# OSH_2018.net
KiCad netlist of a schematic drawn in EAGLE
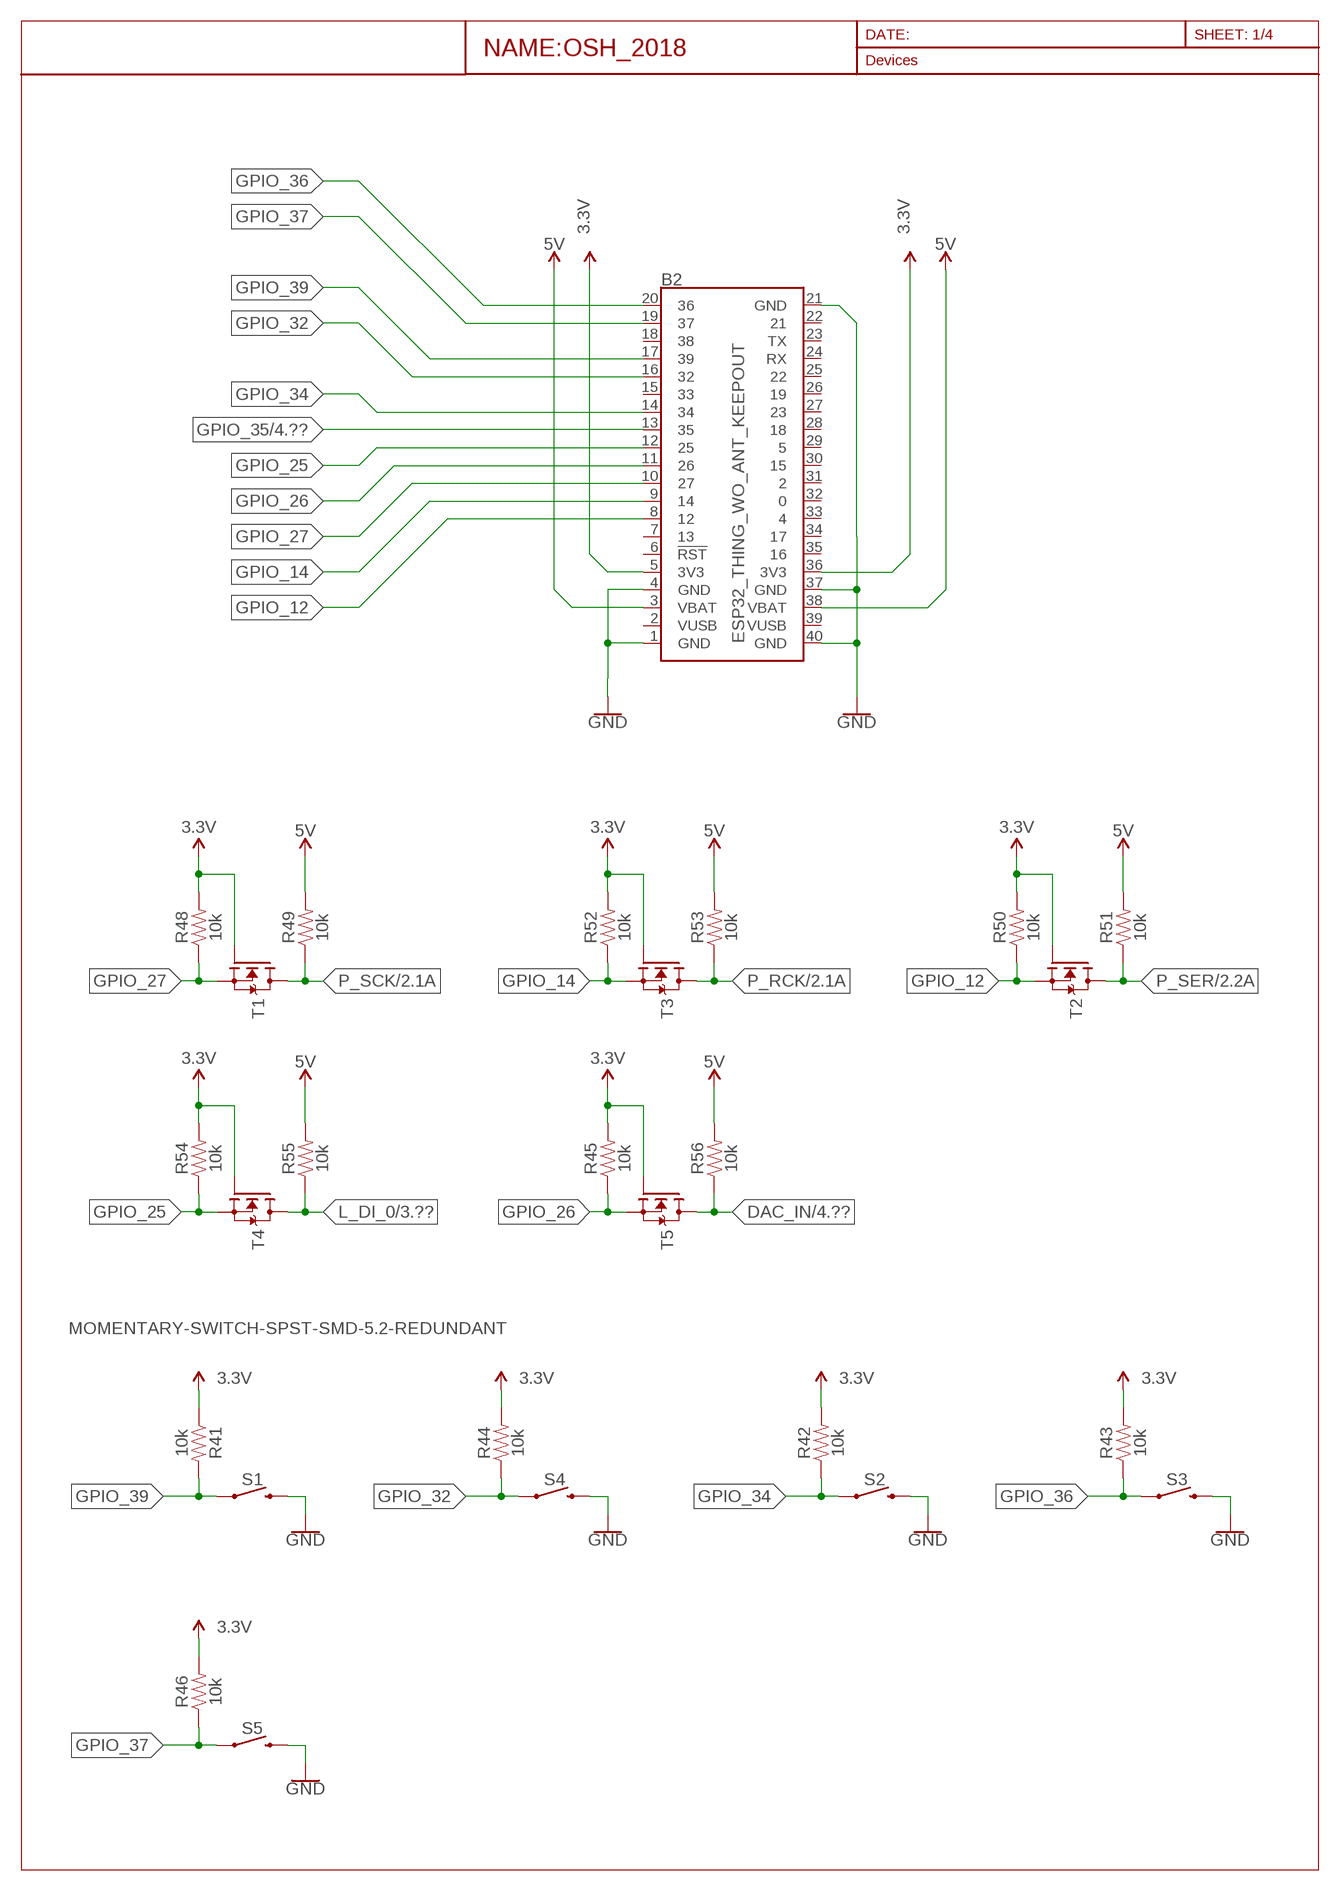
[diagram p0: schematic, sheet 1]
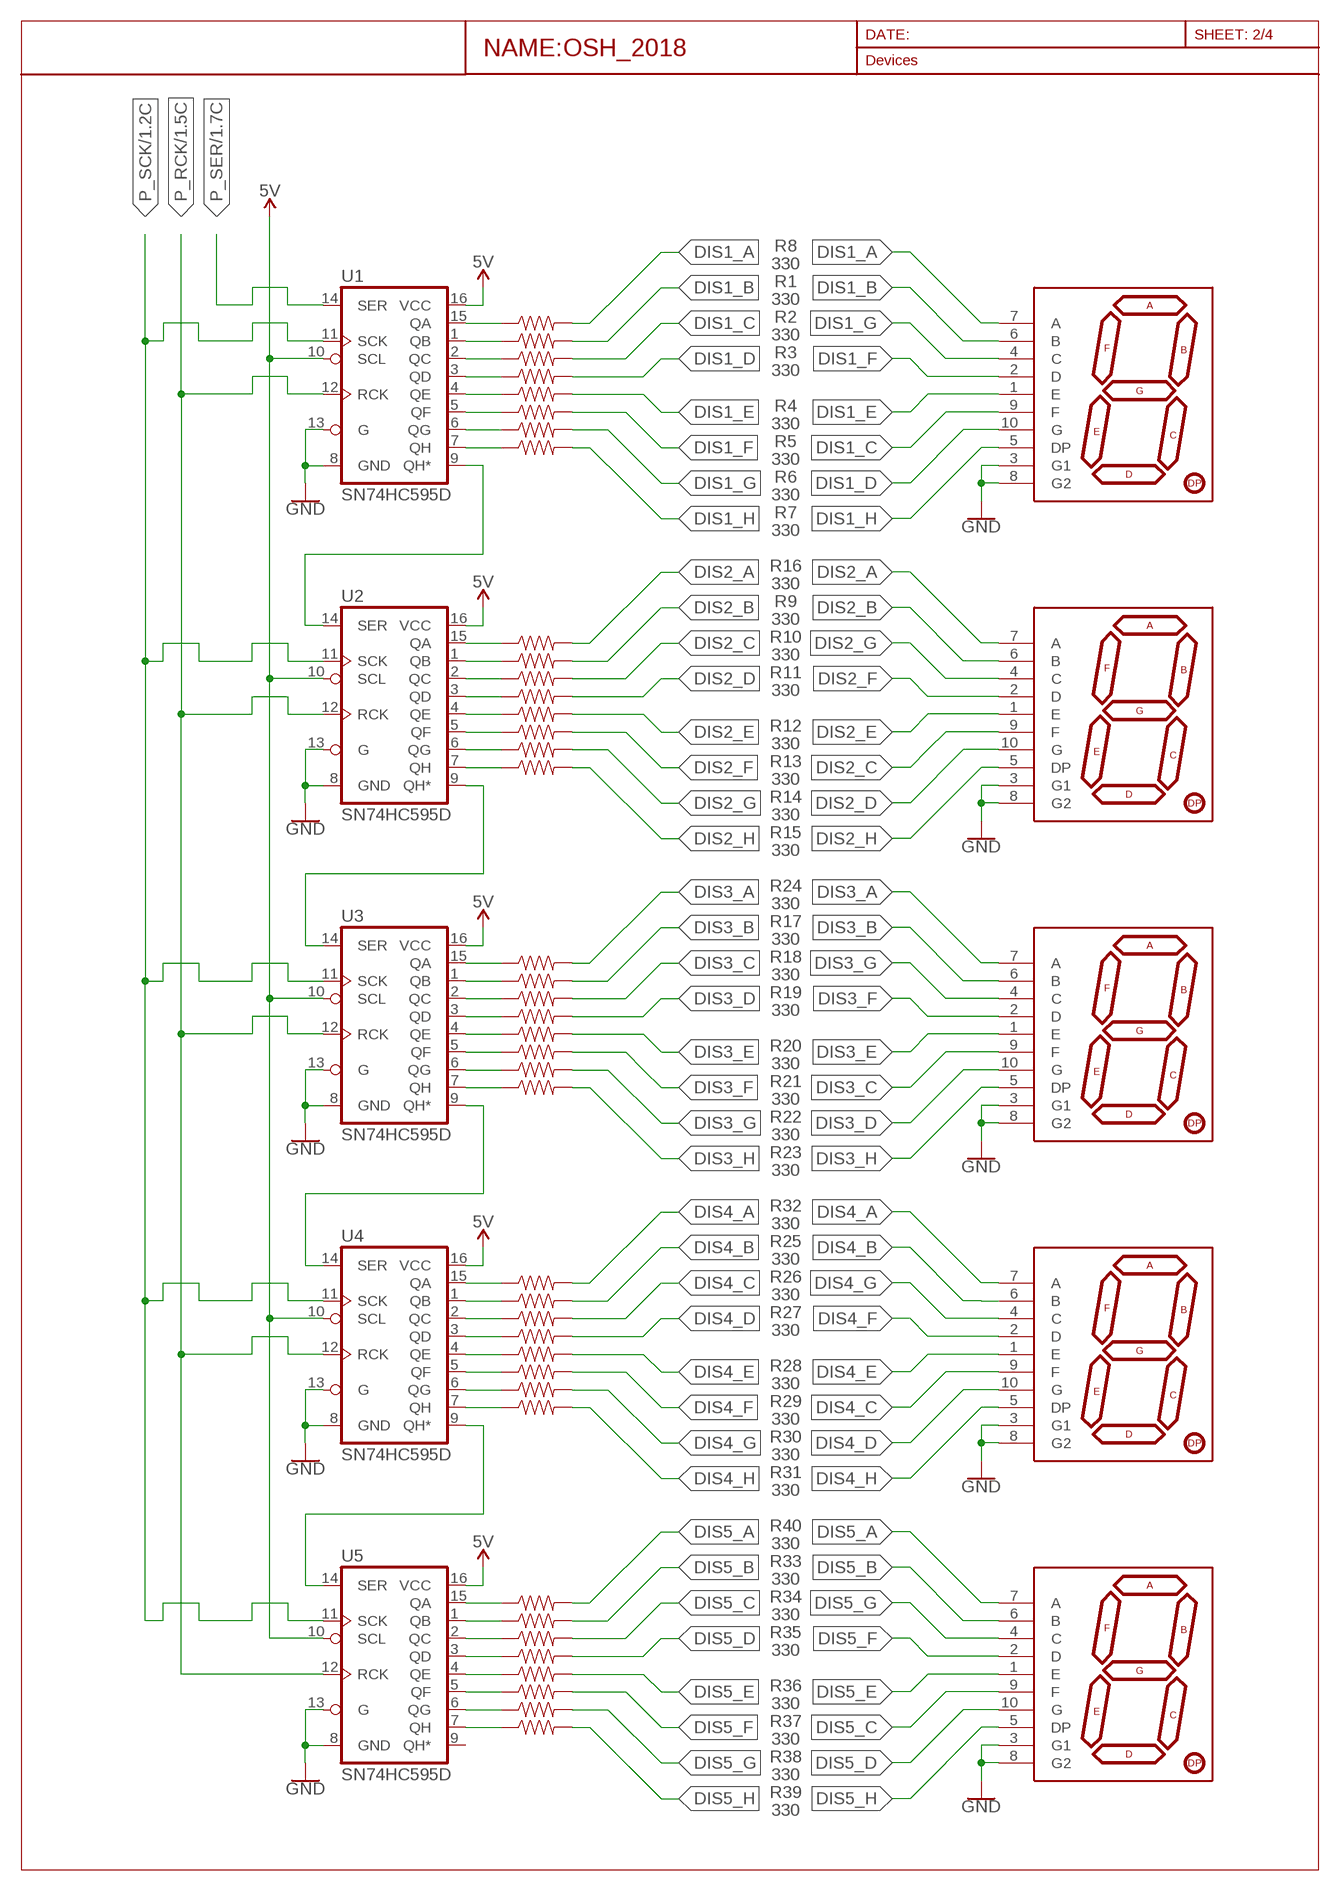
[diagram p1: schematic, sheet 2]
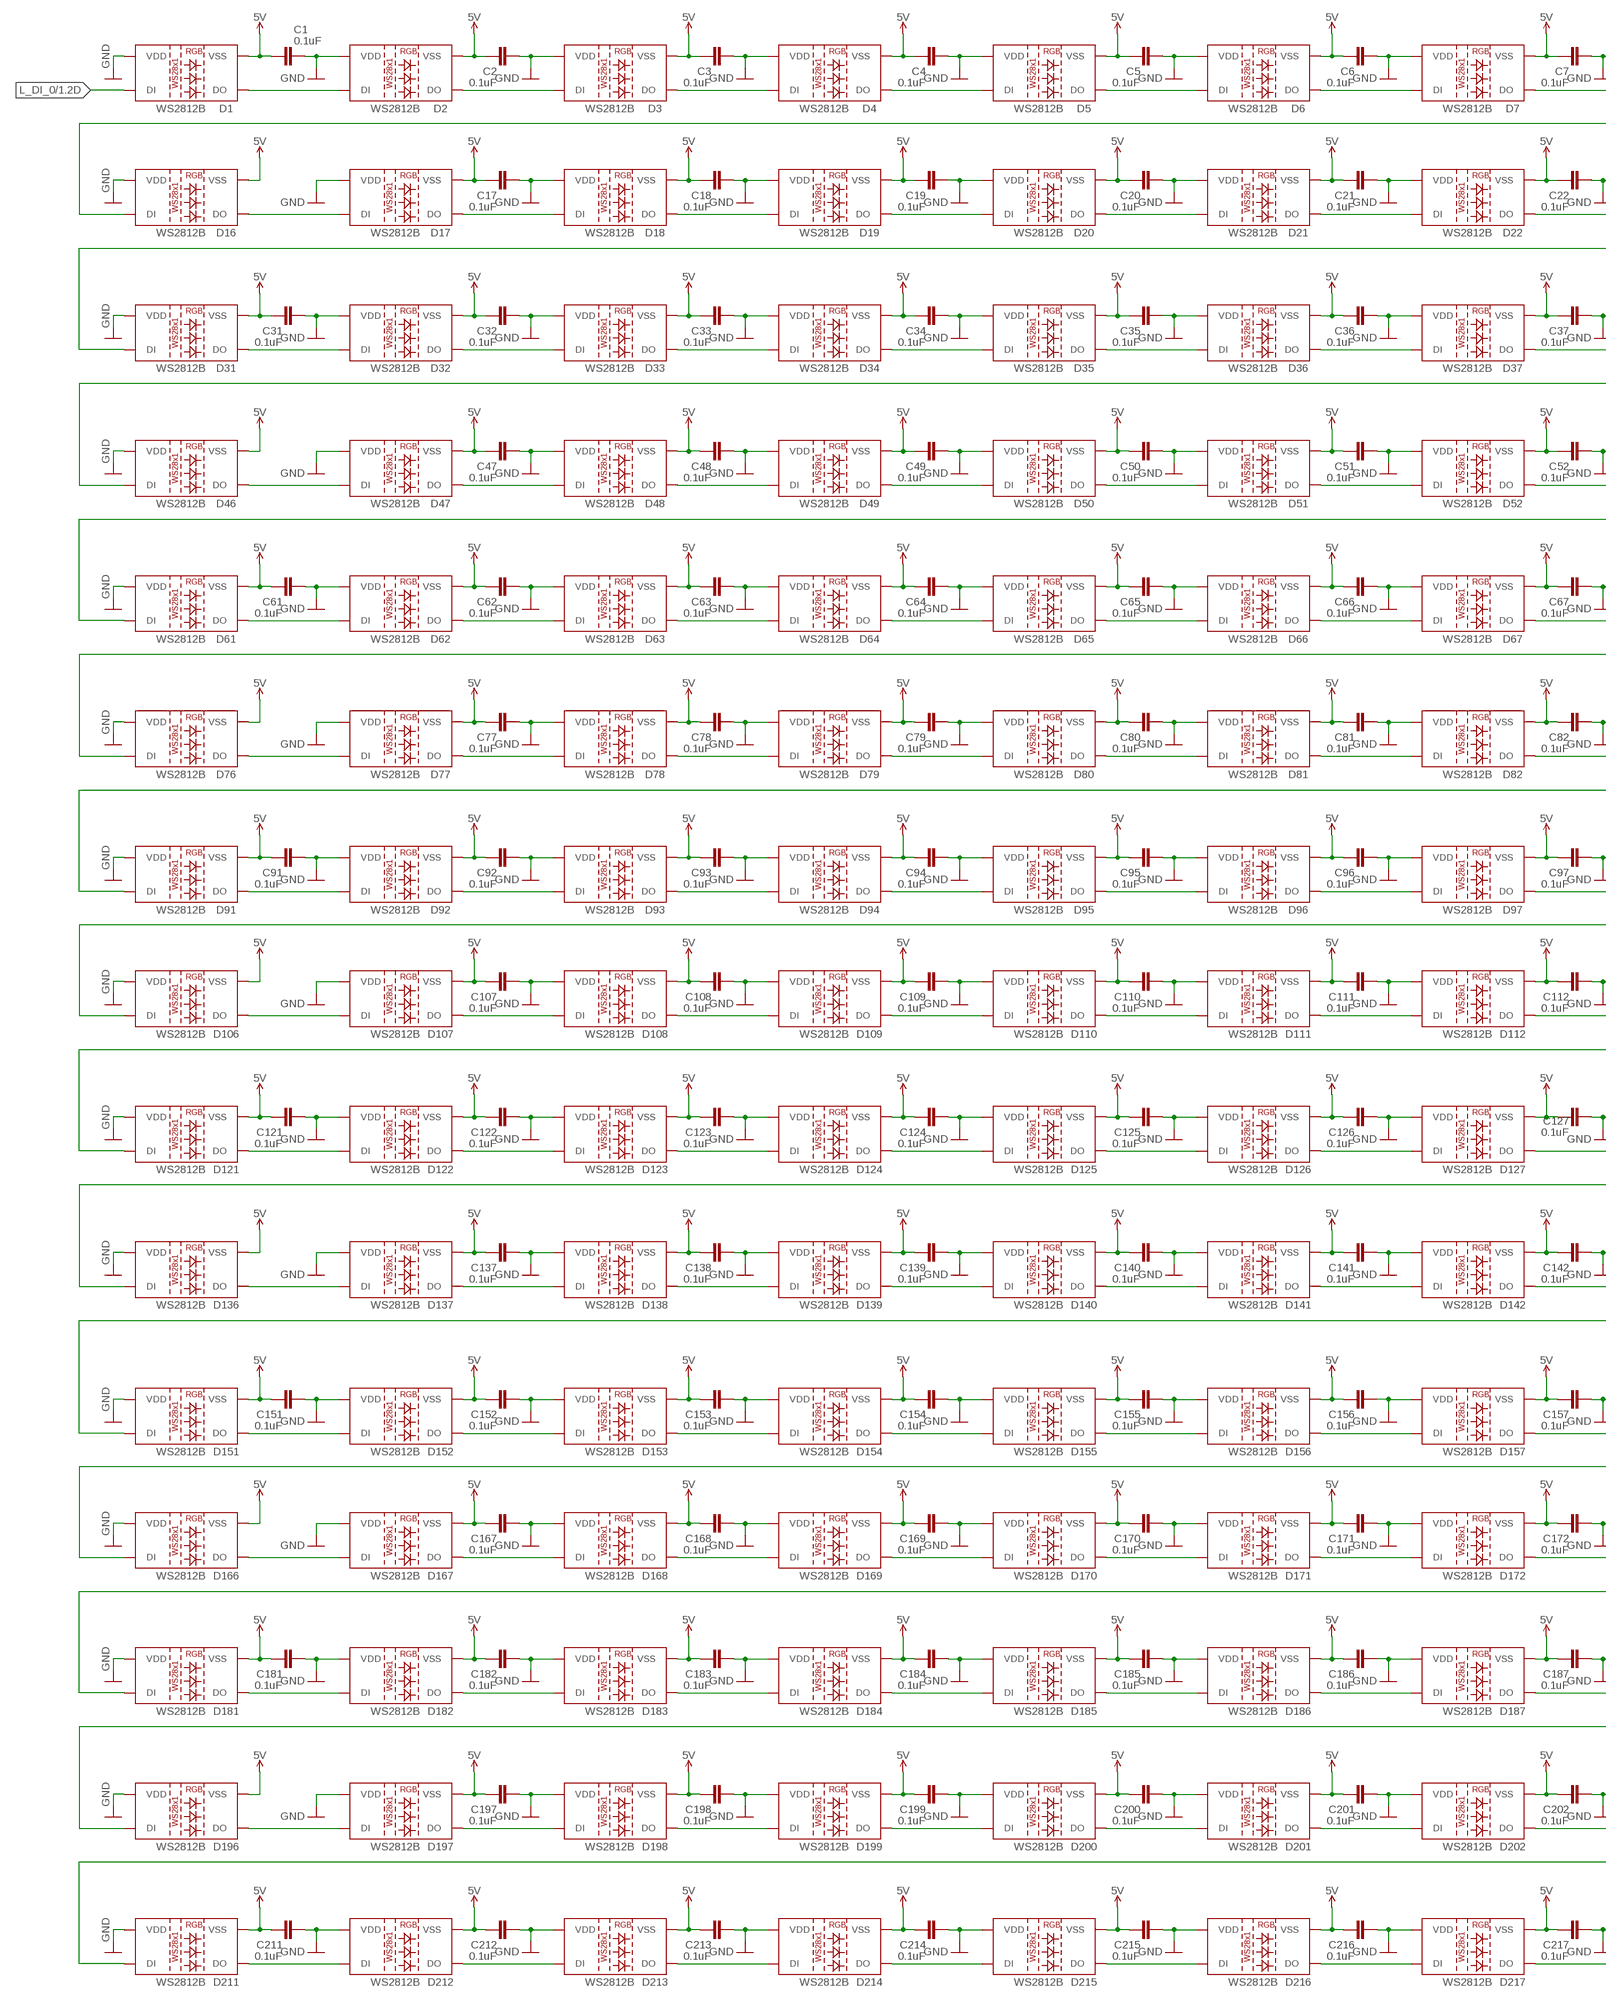
[diagram p2: schematic, sheet 3, part 1 of 2]
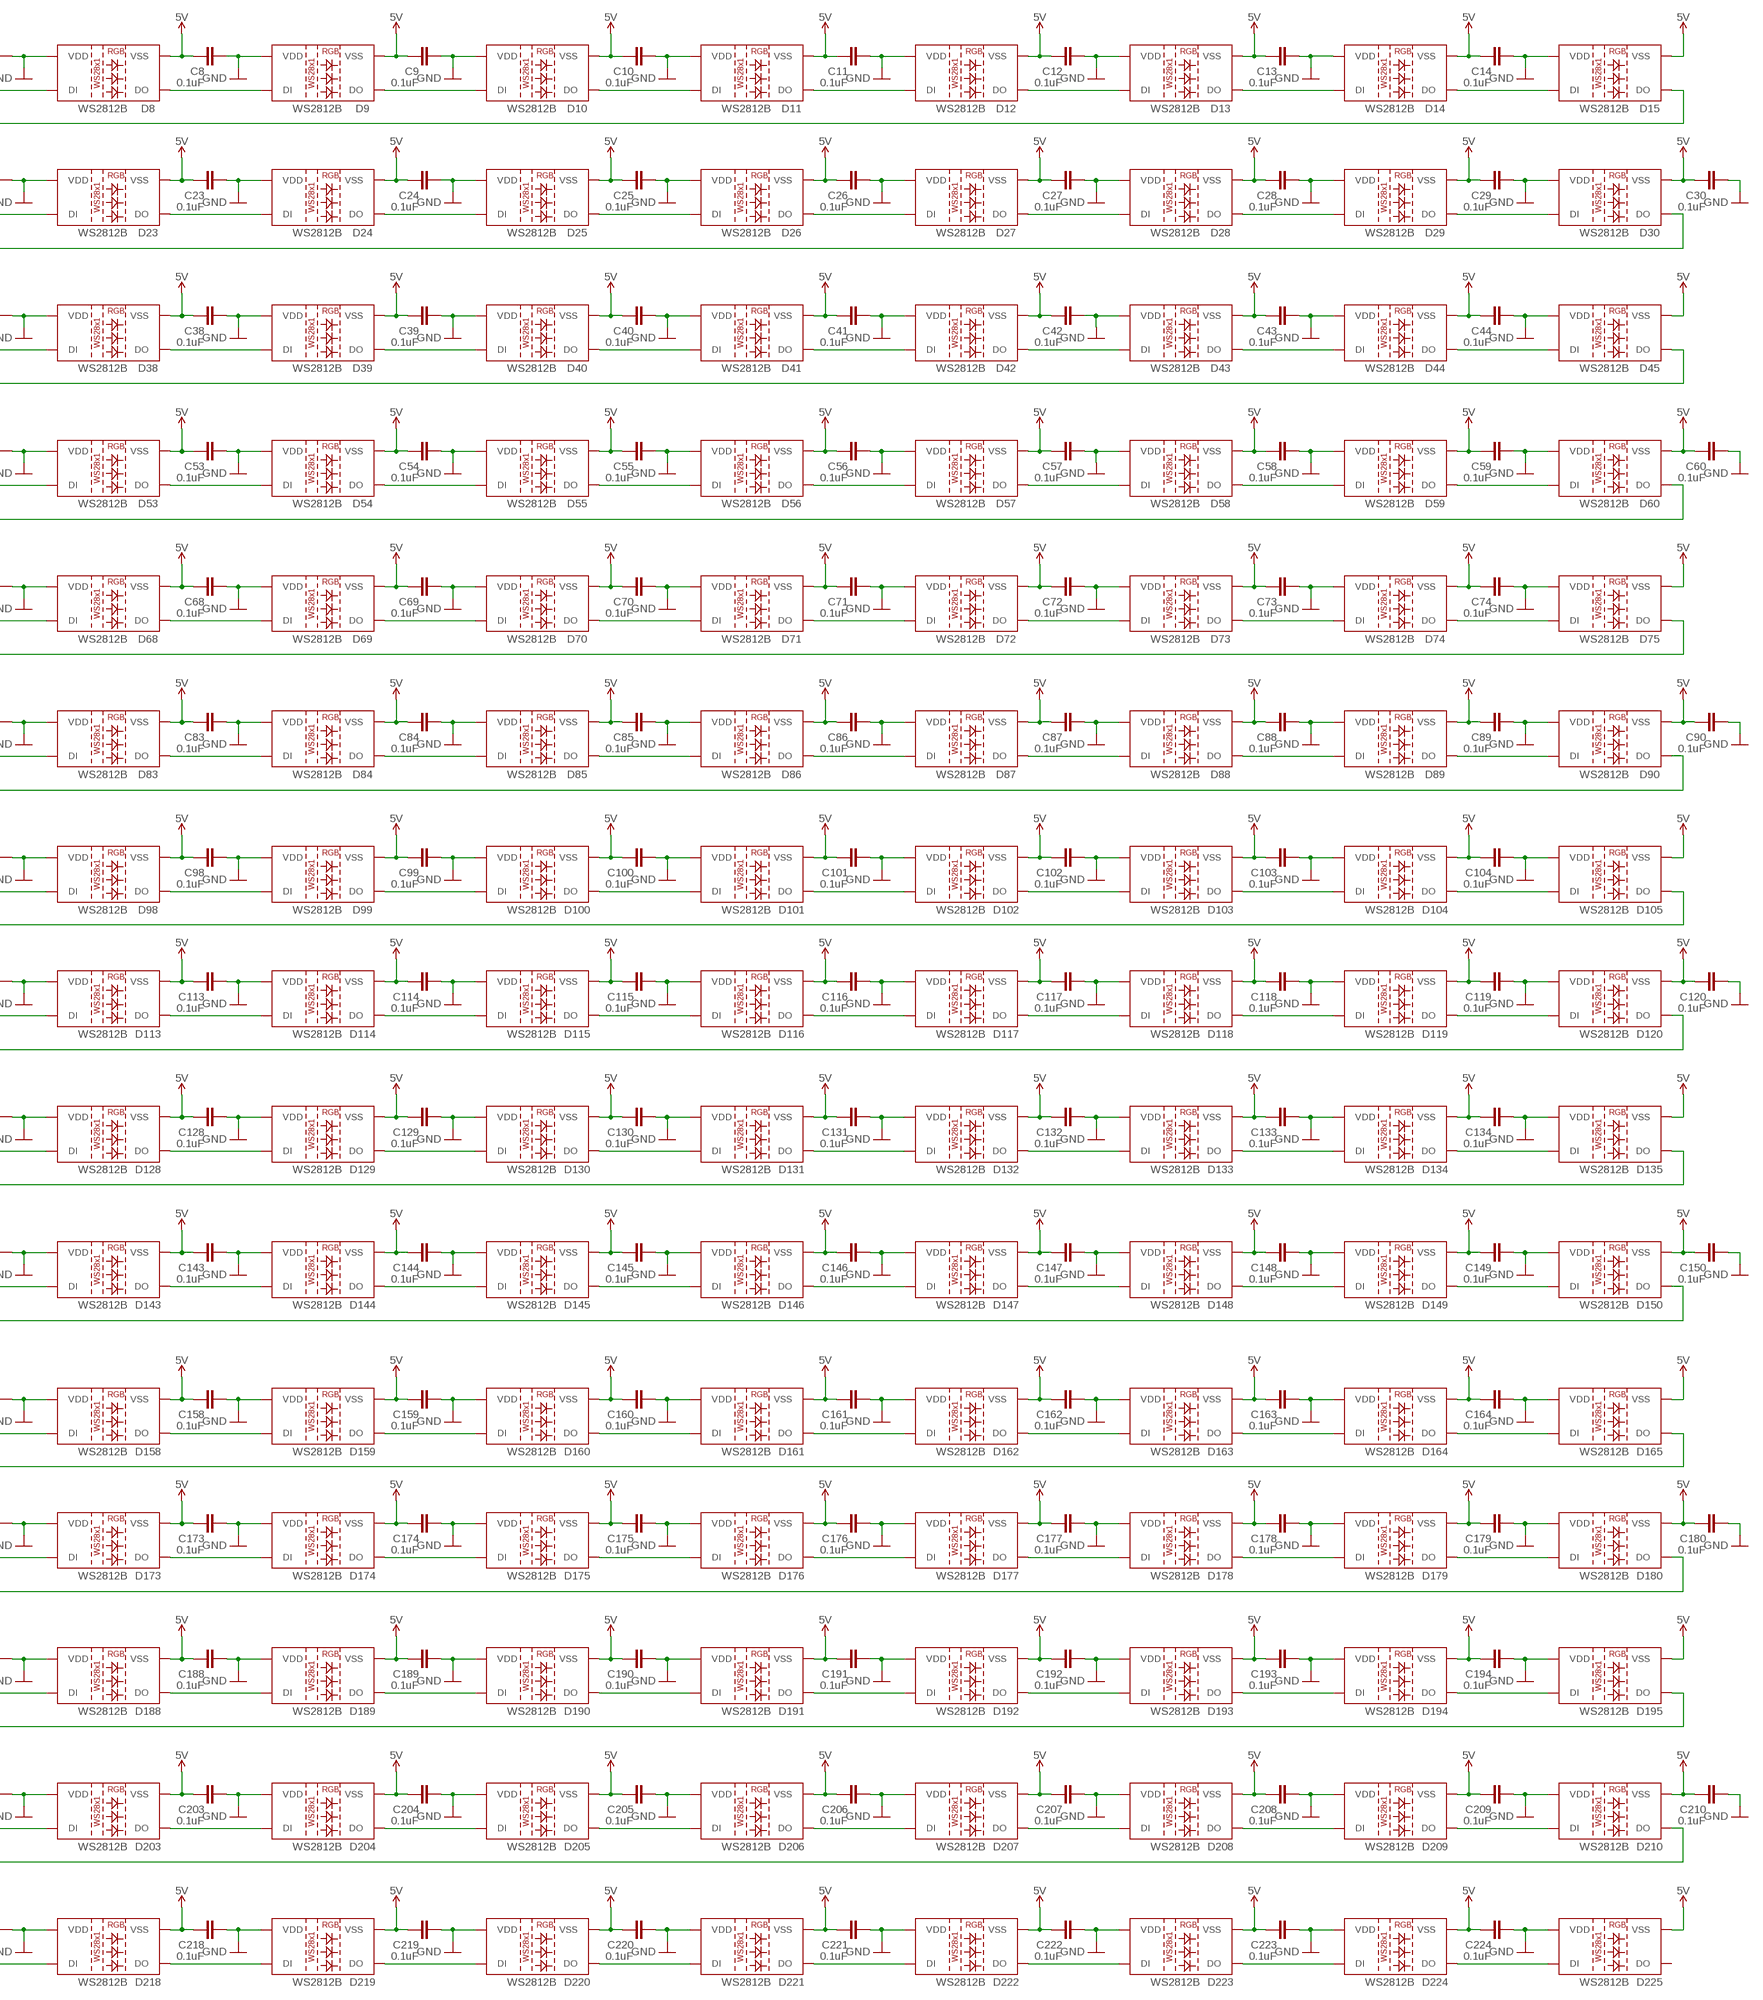
[diagram p3: schematic, sheet 3, part 2 of 2]
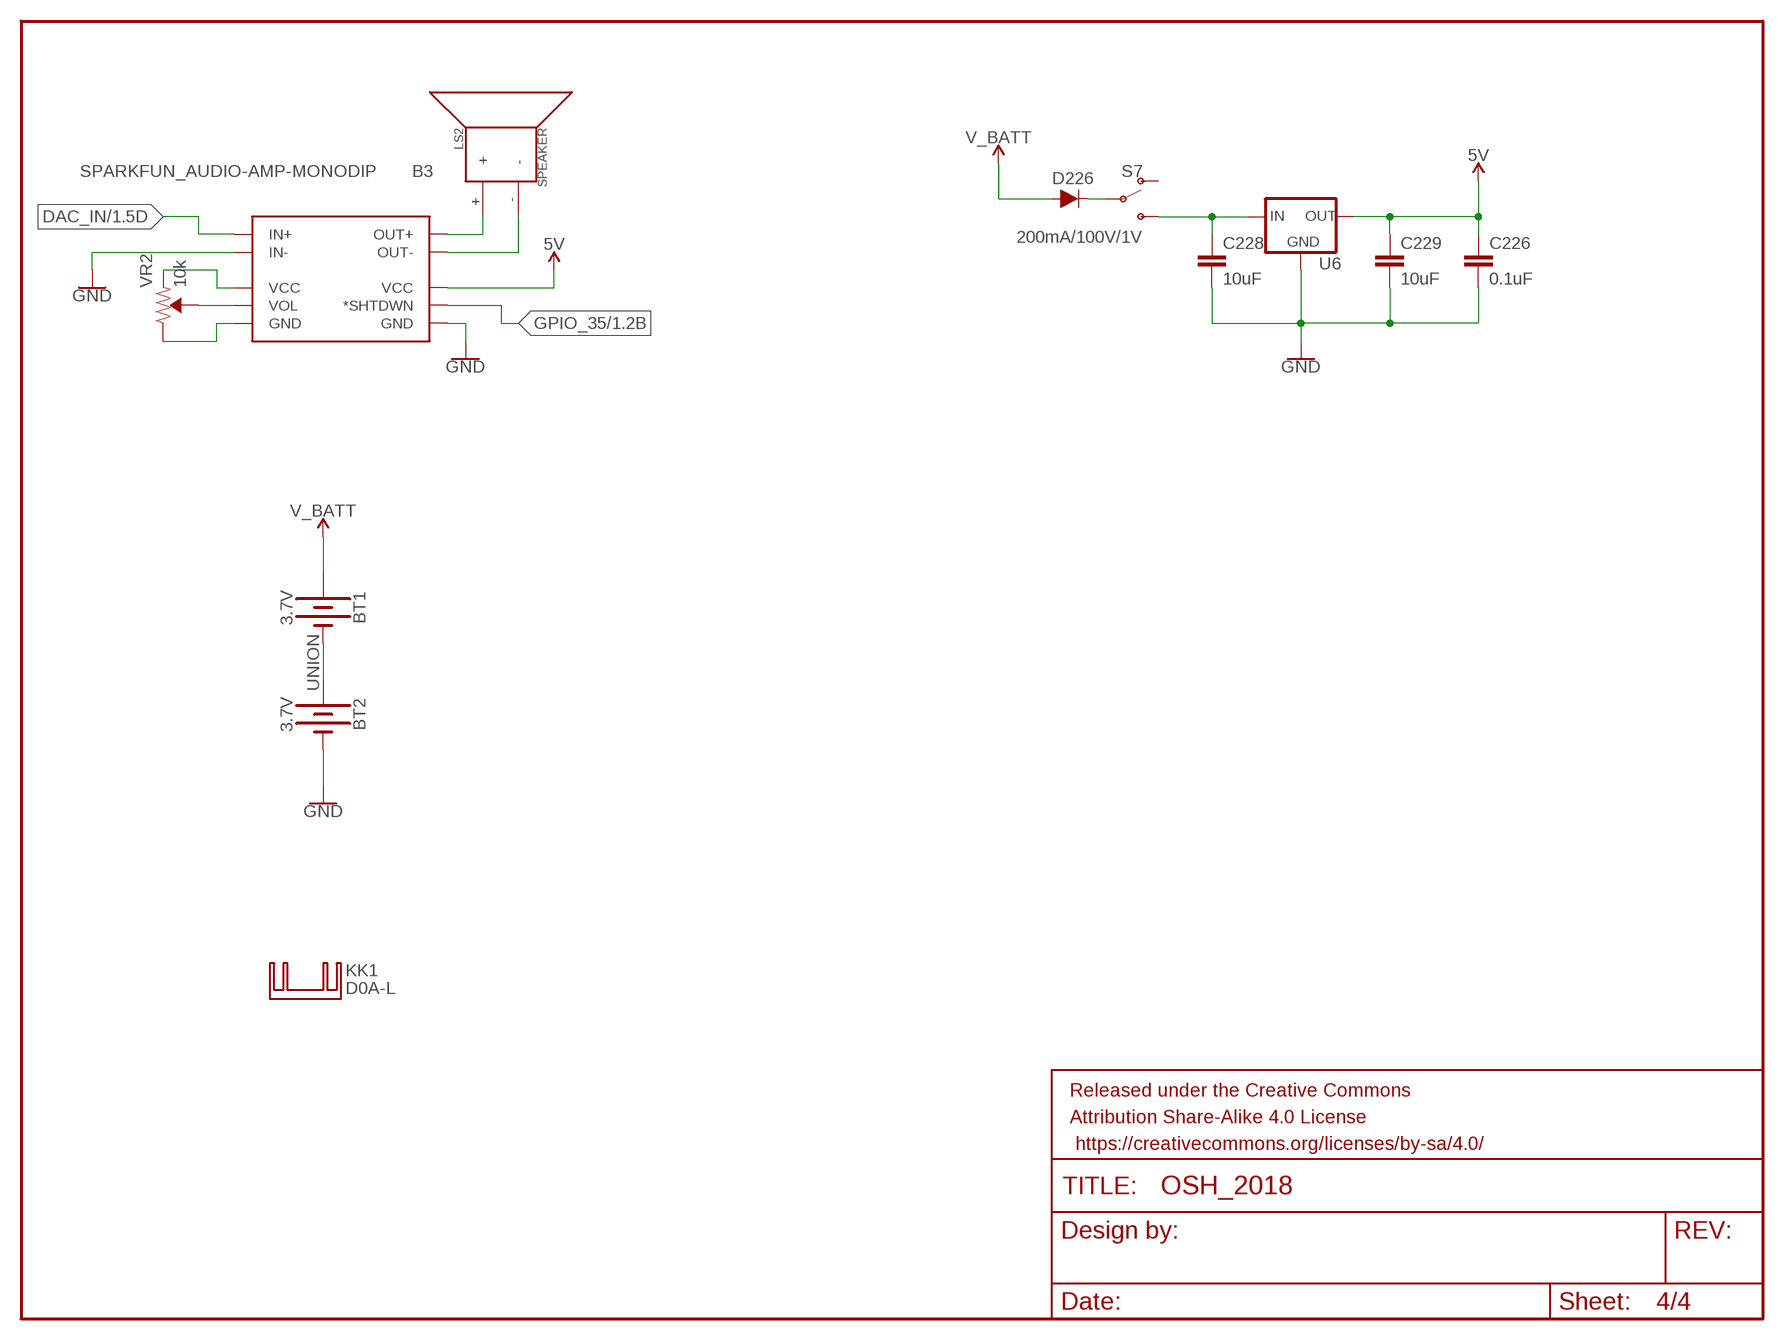
[diagram p4: schematic, sheet 4]

(export (version "E")
  (design (tool "Eeschema 10.0.6"))
  (components
    (comp (ref "B3")
      (value "SPARKFUN_AUDIO-AMP-MONODIP")
      (footprint "eagle-import:AUDIO-AMP-MONO")
      (libsource (lib "eagle-import") (part "SPARKFUN_AUDIO-AMP-MONODIP"))
    )
    (comp (ref "BT1")
      (value "3.7V")
      (footprint "eagle-import:BATTERY_18650-HOLDER")
      (libsource (lib "eagle-import") (part "BATTERY-18650"))
    )
    (comp (ref "BT2")
      (value "3.7V")
      (footprint "eagle-import:BATTERY_18650-HOLDER")
      (libsource (lib "eagle-import") (part "BATTERY-18650"))
    )
    (comp (ref "C226")
      (value "0.1uF")
      (footprint "eagle-import:0603")
      (libsource (lib "eagle-import") (part "SparkFun-Capacitors_510_0.1UF-0603-25V-(+80/-20%)"))
    )
    (comp (ref "C228")
      (value "10uF")
      (footprint "eagle-import:0603")
      (libsource (lib "eagle-import") (part "10UF-0603-6.3V-20%"))
    )
    (comp (ref "C229")
      (value "10uF")
      (footprint "eagle-import:0603")
      (libsource (lib "eagle-import") (part "10UF-0603-6.3V-20%"))
    )
    (comp (ref "D226")
      (value "200mA/100V/1V")
      (footprint "eagle-import:DIODE-1N4148")
      (libsource (lib "eagle-import") (part "DIODE-1N4148"))
    )
    (comp (ref "FRAME3")
      (value "FRAME-LETTERNO_PACKAGE")
      (footprint "eagle-import:DUMMY")
      (fields (field (name "DESIGNER") "Nobody"))
      (libsource (lib "eagle-import") (part "FRAME-LETTERNO_PACKAGE"))
    )
    (comp (ref "KK1")
      (value "D0A-L")
      (footprint "eagle-import:D02A-L")
      (libsource (lib "eagle-import") (part "D0A-L"))
    )
    (comp (ref "LS2")
      (value "SPEAKER")
      (footprint "eagle-import:PCB_MOUNT_SPEAKER")
      (libsource (lib "eagle-import") (part "SPEAKER"))
    )
    (comp (ref "S7")
      (value "SWITCH-SPDT-SMD-RIGHT-ANGLE")
      (footprint "eagle-import:SWITCH_SPST_SMD_A")
      (libsource (lib "eagle-import") (part "SWITCH-SPDT-SMD-RIGHT-ANGLE"))
    )
    (comp (ref "U6")
      (value "V_REG_78XX-TO-220")
      (footprint "eagle-import:TO-220-ALT")
      (libsource (lib "eagle-import") (part "V_REG_78XX-TO-220"))
    )
    (comp (ref "VR2")
      (value "10k")
      (footprint "eagle-import:TRIMPOT-PTH-3386U")
      (libsource (lib "eagle-import") (part "TRIMPOT-PTH-10MM-KNOB-1/2W-10%"))
    )
    (comp (ref "B2")
      (value "ESP32_THING_WO_ANT_KEEPOUT")
      (footprint "eagle-import:ESP32_THING_NO_ANT")
      (libsource (lib "eagle-import") (part "ESP32_THING_WO_ANT_KEEPOUT"))
    )
    (comp (ref "R41")
      (value "10k")
      (footprint "eagle-import:0603")
      (libsource (lib "eagle-import") (part "10KOHM-0603-1/10W-1%"))
    )
    (comp (ref "R42")
      (value "10k")
      (footprint "eagle-import:0603")
      (libsource (lib "eagle-import") (part "10KOHM-0603-1/10W-1%"))
    )
    (comp (ref "R43")
      (value "10k")
      (footprint "eagle-import:0603")
      (libsource (lib "eagle-import") (part "10KOHM-0603-1/10W-1%"))
    )
    (comp (ref "R44")
      (value "10k")
      (footprint "eagle-import:0603")
      (libsource (lib "eagle-import") (part "10KOHM-0603-1/10W-1%"))
    )
    (comp (ref "R45")
      (value "10k")
      (footprint "eagle-import:0603")
      (libsource (lib "eagle-import") (part "10KOHM-0603-1/10W-1%"))
    )
    (comp (ref "R46")
      (value "10k")
      (footprint "eagle-import:0603")
      (libsource (lib "eagle-import") (part "10KOHM-0603-1/10W-1%"))
    )
    (comp (ref "R48")
      (value "10k")
      (footprint "eagle-import:0603")
      (libsource (lib "eagle-import") (part "10KOHM-0603-1/10W-1%"))
    )
    (comp (ref "R49")
      (value "10k")
      (footprint "eagle-import:0603")
      (libsource (lib "eagle-import") (part "10KOHM-0603-1/10W-1%"))
    )
    (comp (ref "R50")
      (value "10k")
      (footprint "eagle-import:0603")
      (libsource (lib "eagle-import") (part "10KOHM-0603-1/10W-1%"))
    )
    (comp (ref "R51")
      (value "10k")
      (footprint "eagle-import:0603")
      (libsource (lib "eagle-import") (part "10KOHM-0603-1/10W-1%"))
    )
    (comp (ref "R52")
      (value "10k")
      (footprint "eagle-import:0603")
      (libsource (lib "eagle-import") (part "10KOHM-0603-1/10W-1%"))
    )
    (comp (ref "R53")
      (value "10k")
      (footprint "eagle-import:0603")
      (libsource (lib "eagle-import") (part "10KOHM-0603-1/10W-1%"))
    )
    (comp (ref "R54")
      (value "10k")
      (footprint "eagle-import:0603")
      (libsource (lib "eagle-import") (part "10KOHM-0603-1/10W-1%"))
    )
    (comp (ref "R55")
      (value "10k")
      (footprint "eagle-import:0603")
      (libsource (lib "eagle-import") (part "10KOHM-0603-1/10W-1%"))
    )
    (comp (ref "R56")
      (value "10k")
      (footprint "eagle-import:0603")
      (libsource (lib "eagle-import") (part "10KOHM-0603-1/10W-1%"))
    )
    (comp (ref "S1")
      (value "MOMENTARY-SWITCH-SPST-SMD-5.2-REDUNDANT")
      (footprint "eagle-import:TACTILE_SWITCH_SMD_5.2MM")
      (libsource (lib "eagle-import") (part "MOMENTARY-SWITCH-SPST-SMD-5.2-REDUNDANT"))
    )
    (comp (ref "S2")
      (value "MOMENTARY-SWITCH-SPST-SMD-5.2-REDUNDANT")
      (footprint "eagle-import:TACTILE_SWITCH_SMD_5.2MM")
      (libsource (lib "eagle-import") (part "MOMENTARY-SWITCH-SPST-SMD-5.2-REDUNDANT"))
    )
    (comp (ref "S3")
      (value "MOMENTARY-SWITCH-SPST-SMD-5.2-REDUNDANT")
      (footprint "eagle-import:TACTILE_SWITCH_SMD_5.2MM")
      (libsource (lib "eagle-import") (part "MOMENTARY-SWITCH-SPST-SMD-5.2-REDUNDANT"))
    )
    (comp (ref "S4")
      (value "MOMENTARY-SWITCH-SPST-SMD-5.2-REDUNDANT")
      (footprint "eagle-import:TACTILE_SWITCH_SMD_5.2MM")
      (libsource (lib "eagle-import") (part "MOMENTARY-SWITCH-SPST-SMD-5.2-REDUNDANT"))
    )
    (comp (ref "S5")
      (value "MOMENTARY-SWITCH-SPST-SMD-5.2-REDUNDANT")
      (footprint "eagle-import:TACTILE_SWITCH_SMD_5.2MM")
      (libsource (lib "eagle-import") (part "MOMENTARY-SWITCH-SPST-SMD-5.2-REDUNDANT"))
    )
    (comp (ref "T1")
      (value "MOSFET-N-SOT23")
      (footprint "eagle-import:SOT23")
      (libsource (lib "eagle-import") (part "MOSFET-N-SOT23"))
    )
    (comp (ref "T2")
      (value "MOSFET-N-SOT23")
      (footprint "eagle-import:SOT23")
      (libsource (lib "eagle-import") (part "MOSFET-N-SOT23"))
    )
    (comp (ref "T3")
      (value "MOSFET-N-SOT23")
      (footprint "eagle-import:SOT23")
      (libsource (lib "eagle-import") (part "MOSFET-N-SOT23"))
    )
    (comp (ref "T4")
      (value "MOSFET-N-SOT23")
      (footprint "eagle-import:SOT23")
      (libsource (lib "eagle-import") (part "MOSFET-N-SOT23"))
    )
    (comp (ref "T5")
      (value "MOSFET-N-SOT23")
      (footprint "eagle-import:SOT23")
      (libsource (lib "eagle-import") (part "MOSFET-N-SOT23"))
    )
    (comp (ref "DISPLAY_1")
      (value "YSD-160AB3C-8")
      (footprint "eagle-import:7-SEGMENT-1_PTH")
      (libsource (lib "eagle-import") (part "7-SEGMENT-1DIGIT-1INCH-BLUE"))
    )
    (comp (ref "DISPLAY_2")
      (value "YSD-160AB3C-8")
      (footprint "eagle-import:7-SEGMENT-1_PTH")
      (libsource (lib "eagle-import") (part "7-SEGMENT-1DIGIT-1INCH-BLUE"))
    )
    (comp (ref "DISPLAY_3")
      (value "YSD-160AB3C-8")
      (footprint "eagle-import:7-SEGMENT-1_PTH")
      (libsource (lib "eagle-import") (part "7-SEGMENT-1DIGIT-1INCH-BLUE"))
    )
    (comp (ref "DISPLAY_4")
      (value "YSD-160AB3C-8")
      (footprint "eagle-import:7-SEGMENT-1_PTH")
      (libsource (lib "eagle-import") (part "7-SEGMENT-1DIGIT-1INCH-BLUE"))
    )
    (comp (ref "DISPLAY_5")
      (value "YSD-160AB3C-8")
      (footprint "eagle-import:7-SEGMENT-1_PTH")
      (libsource (lib "eagle-import") (part "7-SEGMENT-1DIGIT-1INCH-BLUE"))
    )
    (comp (ref "R1")
      (value "330")
      (footprint "eagle-import:0603")
      (libsource (lib "eagle-import") (part "330OHM-0603-1/10W-1%"))
    )
    (comp (ref "R2")
      (value "330")
      (footprint "eagle-import:0603")
      (libsource (lib "eagle-import") (part "330OHM-0603-1/10W-1%"))
    )
    (comp (ref "R3")
      (value "330")
      (footprint "eagle-import:0603")
      (libsource (lib "eagle-import") (part "330OHM-0603-1/10W-1%"))
    )
    (comp (ref "R4")
      (value "330")
      (footprint "eagle-import:0603")
      (libsource (lib "eagle-import") (part "330OHM-0603-1/10W-1%"))
    )
    (comp (ref "R5")
      (value "330")
      (footprint "eagle-import:0603")
      (libsource (lib "eagle-import") (part "330OHM-0603-1/10W-1%"))
    )
    (comp (ref "R6")
      (value "330")
      (footprint "eagle-import:0603")
      (libsource (lib "eagle-import") (part "330OHM-0603-1/10W-1%"))
    )
    (comp (ref "R7")
      (value "330")
      (footprint "eagle-import:0603")
      (libsource (lib "eagle-import") (part "330OHM-0603-1/10W-1%"))
    )
    (comp (ref "R8")
      (value "330")
      (footprint "eagle-import:0603")
      (libsource (lib "eagle-import") (part "330OHM-0603-1/10W-1%"))
    )
    (comp (ref "R9")
      (value "330")
      (footprint "eagle-import:0603")
      (libsource (lib "eagle-import") (part "330OHM-0603-1/10W-1%"))
    )
    (comp (ref "R10")
      (value "330")
      (footprint "eagle-import:0603")
      (libsource (lib "eagle-import") (part "330OHM-0603-1/10W-1%"))
    )
    (comp (ref "R11")
      (value "330")
      (footprint "eagle-import:0603")
      (libsource (lib "eagle-import") (part "330OHM-0603-1/10W-1%"))
    )
    (comp (ref "R12")
      (value "330")
      (footprint "eagle-import:0603")
      (libsource (lib "eagle-import") (part "330OHM-0603-1/10W-1%"))
    )
    (comp (ref "R13")
      (value "330")
      (footprint "eagle-import:0603")
      (libsource (lib "eagle-import") (part "330OHM-0603-1/10W-1%"))
    )
    (comp (ref "R14")
      (value "330")
      (footprint "eagle-import:0603")
      (libsource (lib "eagle-import") (part "330OHM-0603-1/10W-1%"))
    )
    (comp (ref "R15")
      (value "330")
      (footprint "eagle-import:0603")
      (libsource (lib "eagle-import") (part "330OHM-0603-1/10W-1%"))
    )
    (comp (ref "R16")
      (value "330")
      (footprint "eagle-import:0603")
      (libsource (lib "eagle-import") (part "330OHM-0603-1/10W-1%"))
    )
    (comp (ref "R17")
      (value "330")
      (footprint "eagle-import:0603")
      (libsource (lib "eagle-import") (part "330OHM-0603-1/10W-1%"))
    )
    (comp (ref "R18")
      (value "330")
      (footprint "eagle-import:0603")
      (libsource (lib "eagle-import") (part "330OHM-0603-1/10W-1%"))
    )
    (comp (ref "R19")
      (value "330")
      (footprint "eagle-import:0603")
      (libsource (lib "eagle-import") (part "330OHM-0603-1/10W-1%"))
    )
    (comp (ref "R20")
      (value "330")
      (footprint "eagle-import:0603")
      (libsource (lib "eagle-import") (part "330OHM-0603-1/10W-1%"))
    )
    (comp (ref "R21")
      (value "330")
      (footprint "eagle-import:0603")
      (libsource (lib "eagle-import") (part "330OHM-0603-1/10W-1%"))
    )
    (comp (ref "R22")
      (value "330")
      (footprint "eagle-import:0603")
      (libsource (lib "eagle-import") (part "330OHM-0603-1/10W-1%"))
    )
    (comp (ref "R23")
      (value "330")
      (footprint "eagle-import:0603")
      (libsource (lib "eagle-import") (part "330OHM-0603-1/10W-1%"))
    )
    (comp (ref "R24")
      (value "330")
      (footprint "eagle-import:0603")
      (libsource (lib "eagle-import") (part "330OHM-0603-1/10W-1%"))
    )
    (comp (ref "R25")
      (value "330")
      (footprint "eagle-import:0603")
      (libsource (lib "eagle-import") (part "330OHM-0603-1/10W-1%"))
    )
    (comp (ref "R26")
      (value "330")
      (footprint "eagle-import:0603")
      (libsource (lib "eagle-import") (part "330OHM-0603-1/10W-1%"))
    )
    (comp (ref "R27")
      (value "330")
      (footprint "eagle-import:0603")
      (libsource (lib "eagle-import") (part "330OHM-0603-1/10W-1%"))
    )
    (comp (ref "R28")
      (value "330")
      (footprint "eagle-import:0603")
      (libsource (lib "eagle-import") (part "330OHM-0603-1/10W-1%"))
    )
    (comp (ref "R29")
      (value "330")
      (footprint "eagle-import:0603")
      (libsource (lib "eagle-import") (part "330OHM-0603-1/10W-1%"))
    )
    (comp (ref "R30")
      (value "330")
      (footprint "eagle-import:0603")
      (libsource (lib "eagle-import") (part "330OHM-0603-1/10W-1%"))
    )
    (comp (ref "R31")
      (value "330")
      (footprint "eagle-import:0603")
      (libsource (lib "eagle-import") (part "330OHM-0603-1/10W-1%"))
    )
    (comp (ref "R32")
      (value "330")
      (footprint "eagle-import:0603")
      (libsource (lib "eagle-import") (part "330OHM-0603-1/10W-1%"))
    )
    (comp (ref "R33")
      (value "330")
      (footprint "eagle-import:0603")
      (libsource (lib "eagle-import") (part "330OHM-0603-1/10W-1%"))
    )
    (comp (ref "R34")
      (value "330")
      (footprint "eagle-import:0603")
      (libsource (lib "eagle-import") (part "330OHM-0603-1/10W-1%"))
    )
    (comp (ref "R35")
      (value "330")
      (footprint "eagle-import:0603")
      (libsource (lib "eagle-import") (part "330OHM-0603-1/10W-1%"))
    )
    (comp (ref "R36")
      (value "330")
      (footprint "eagle-import:0603")
      (libsource (lib "eagle-import") (part "330OHM-0603-1/10W-1%"))
    )
    (comp (ref "R37")
      (value "330")
      (footprint "eagle-import:0603")
      (libsource (lib "eagle-import") (part "330OHM-0603-1/10W-1%"))
    )
    (comp (ref "R38")
      (value "330")
      (footprint "eagle-import:0603")
      (libsource (lib "eagle-import") (part "330OHM-0603-1/10W-1%"))
    )
    (comp (ref "R39")
      (value "330")
      (footprint "eagle-import:0603")
      (libsource (lib "eagle-import") (part "330OHM-0603-1/10W-1%"))
    )
    (comp (ref "R40")
      (value "330")
      (footprint "eagle-import:0603")
      (libsource (lib "eagle-import") (part "330OHM-0603-1/10W-1%"))
    )
    (comp (ref "U1")
      (value "SN74HC595D")
      (footprint "eagle-import:SO16")
      (libsource (lib "eagle-import") (part "74595DHC"))
    )
    (comp (ref "U2")
      (value "SN74HC595D")
      (footprint "eagle-import:SO16")
      (libsource (lib "eagle-import") (part "74595DHC"))
    )
    (comp (ref "U3")
      (value "SN74HC595D")
      (footprint "eagle-import:SO16")
      (libsource (lib "eagle-import") (part "74595DHC"))
    )
    (comp (ref "U4")
      (value "SN74HC595D")
      (footprint "eagle-import:SO16")
      (libsource (lib "eagle-import") (part "74595DHC"))
    )
    (comp (ref "U5")
      (value "SN74HC595D")
      (footprint "eagle-import:SO16")
      (libsource (lib "eagle-import") (part "74595DHC"))
    )
    (comp (ref "C1")
      (value "0.1uF")
      (footprint "eagle-import:0603")
      (libsource (lib "eagle-import") (part "0.1UF-0603-25V-5%"))
    )
    (comp (ref "C2")
      (value "0.1uF")
      (footprint "eagle-import:0603")
      (libsource (lib "eagle-import") (part "0.1UF-0603-25V-5%"))
    )
    (comp (ref "C3")
      (value "0.1uF")
      (footprint "eagle-import:0603")
      (libsource (lib "eagle-import") (part "0.1UF-0603-25V-5%"))
    )
    (comp (ref "C4")
      (value "0.1uF")
      (footprint "eagle-import:0603")
      (libsource (lib "eagle-import") (part "0.1UF-0603-25V-5%"))
    )
    (comp (ref "C5")
      (value "0.1uF")
      (footprint "eagle-import:0603")
      (libsource (lib "eagle-import") (part "0.1UF-0603-25V-5%"))
    )
    (comp (ref "C6")
      (value "0.1uF")
      (footprint "eagle-import:0603")
      (libsource (lib "eagle-import") (part "0.1UF-0603-25V-5%"))
    )
    (comp (ref "C7")
      (value "0.1uF")
      (footprint "eagle-import:0603")
      (libsource (lib "eagle-import") (part "0.1UF-0603-25V-5%"))
    )
    (comp (ref "C8")
      (value "0.1uF")
      (footprint "eagle-import:0603")
      (libsource (lib "eagle-import") (part "0.1UF-0603-25V-5%"))
    )
    (comp (ref "C9")
      (value "0.1uF")
      (footprint "eagle-import:0603")
      (libsource (lib "eagle-import") (part "0.1UF-0603-25V-5%"))
    )
    (comp (ref "C10")
      (value "0.1uF")
      (footprint "eagle-import:0603")
      (libsource (lib "eagle-import") (part "0.1UF-0603-25V-5%"))
    )
    (comp (ref "C11")
      (value "0.1uF")
      (footprint "eagle-import:0603")
      (libsource (lib "eagle-import") (part "0.1UF-0603-25V-5%"))
    )
    (comp (ref "C12")
      (value "0.1uF")
      (footprint "eagle-import:0603")
      (libsource (lib "eagle-import") (part "0.1UF-0603-25V-5%"))
    )
    (comp (ref "C13")
      (value "0.1uF")
      (footprint "eagle-import:0603")
      (libsource (lib "eagle-import") (part "0.1UF-0603-25V-5%"))
    )
    (comp (ref "C14")
      (value "0.1uF")
      (footprint "eagle-import:0603")
      (libsource (lib "eagle-import") (part "0.1UF-0603-25V-5%"))
    )
    (comp (ref "C17")
      (value "0.1uF")
      (footprint "eagle-import:0603")
      (libsource (lib "eagle-import") (part "0.1UF-0603-25V-5%"))
    )
    (comp (ref "C18")
      (value "0.1uF")
      (footprint "eagle-import:0603")
      (libsource (lib "eagle-import") (part "0.1UF-0603-25V-5%"))
    )
    (comp (ref "C19")
      (value "0.1uF")
      (footprint "eagle-import:0603")
      (libsource (lib "eagle-import") (part "0.1UF-0603-25V-5%"))
    )
    (comp (ref "C20")
      (value "0.1uF")
      (footprint "eagle-import:0603")
      (libsource (lib "eagle-import") (part "0.1UF-0603-25V-5%"))
    )
    (comp (ref "C21")
      (value "0.1uF")
      (footprint "eagle-import:0603")
      (libsource (lib "eagle-import") (part "0.1UF-0603-25V-5%"))
    )
    (comp (ref "C22")
      (value "0.1uF")
      (footprint "eagle-import:0603")
      (libsource (lib "eagle-import") (part "0.1UF-0603-25V-5%"))
    )
    (comp (ref "C23")
      (value "0.1uF")
      (footprint "eagle-import:0603")
      (libsource (lib "eagle-import") (part "0.1UF-0603-25V-5%"))
    )
    (comp (ref "C24")
      (value "0.1uF")
      (footprint "eagle-import:0603")
      (libsource (lib "eagle-import") (part "0.1UF-0603-25V-5%"))
    )
    (comp (ref "C25")
      (value "0.1uF")
      (footprint "eagle-import:0603")
      (libsource (lib "eagle-import") (part "0.1UF-0603-25V-5%"))
    )
    (comp (ref "C26")
      (value "0.1uF")
      (footprint "eagle-import:0603")
      (libsource (lib "eagle-import") (part "0.1UF-0603-25V-5%"))
    )
    (comp (ref "C27")
      (value "0.1uF")
      (footprint "eagle-import:0603")
      (libsource (lib "eagle-import") (part "0.1UF-0603-25V-5%"))
    )
    (comp (ref "C28")
      (value "0.1uF")
      (footprint "eagle-import:0603")
      (libsource (lib "eagle-import") (part "0.1UF-0603-25V-5%"))
    )
    (comp (ref "C29")
      (value "0.1uF")
      (footprint "eagle-import:0603")
      (libsource (lib "eagle-import") (part "0.1UF-0603-25V-5%"))
    )
    (comp (ref "C30")
      (value "0.1uF")
      (footprint "eagle-import:0603")
      (libsource (lib "eagle-import") (part "0.1UF-0603-25V-5%"))
    )
    (comp (ref "C31")
      (value "0.1uF")
      (footprint "eagle-import:0603")
      (libsource (lib "eagle-import") (part "0.1UF-0603-25V-5%"))
    )
    (comp (ref "C32")
      (value "0.1uF")
      (footprint "eagle-import:0603")
      (libsource (lib "eagle-import") (part "0.1UF-0603-25V-5%"))
    )
    (comp (ref "C33")
      (value "0.1uF")
      (footprint "eagle-import:0603")
      (libsource (lib "eagle-import") (part "0.1UF-0603-25V-5%"))
    )
    (comp (ref "C34")
      (value "0.1uF")
      (footprint "eagle-import:0603")
      (libsource (lib "eagle-import") (part "0.1UF-0603-25V-5%"))
    )
    (comp (ref "C35")
      (value "0.1uF")
      (footprint "eagle-import:0603")
      (libsource (lib "eagle-import") (part "0.1UF-0603-25V-5%"))
    )
    (comp (ref "C36")
      (value "0.1uF")
      (footprint "eagle-import:0603")
      (libsource (lib "eagle-import") (part "0.1UF-0603-25V-5%"))
    )
    (comp (ref "C37")
      (value "0.1uF")
      (footprint "eagle-import:0603")
      (libsource (lib "eagle-import") (part "0.1UF-0603-25V-5%"))
    )
    (comp (ref "C38")
      (value "0.1uF")
      (footprint "eagle-import:0603")
      (libsource (lib "eagle-import") (part "0.1UF-0603-25V-5%"))
    )
    (comp (ref "C39")
      (value "0.1uF")
      (footprint "eagle-import:0603")
      (libsource (lib "eagle-import") (part "0.1UF-0603-25V-5%"))
    )
    (comp (ref "C40")
      (value "0.1uF")
      (footprint "eagle-import:0603")
      (libsource (lib "eagle-import") (part "0.1UF-0603-25V-5%"))
    )
    (comp (ref "C41")
      (value "0.1uF")
      (footprint "eagle-import:0603")
      (libsource (lib "eagle-import") (part "0.1UF-0603-25V-5%"))
    )
    (comp (ref "C42")
      (value "0.1uF")
      (footprint "eagle-import:0603")
      (libsource (lib "eagle-import") (part "0.1UF-0603-25V-5%"))
    )
    (comp (ref "C43")
      (value "0.1uF")
      (footprint "eagle-import:0603")
      (libsource (lib "eagle-import") (part "0.1UF-0603-25V-5%"))
    )
    (comp (ref "C44")
      (value "0.1uF")
      (footprint "eagle-import:0603")
      (libsource (lib "eagle-import") (part "0.1UF-0603-25V-5%"))
    )
    (comp (ref "C47")
      (value "0.1uF")
      (footprint "eagle-import:0603")
      (libsource (lib "eagle-import") (part "0.1UF-0603-25V-5%"))
    )
    (comp (ref "C48")
      (value "0.1uF")
      (footprint "eagle-import:0603")
      (libsource (lib "eagle-import") (part "0.1UF-0603-25V-5%"))
    )
    (comp (ref "C49")
      (value "0.1uF")
      (footprint "eagle-import:0603")
      (libsource (lib "eagle-import") (part "0.1UF-0603-25V-5%"))
    )
    (comp (ref "C50")
      (value "0.1uF")
      (footprint "eagle-import:0603")
      (libsource (lib "eagle-import") (part "0.1UF-0603-25V-5%"))
    )
    (comp (ref "C51")
      (value "0.1uF")
      (footprint "eagle-import:0603")
      (libsource (lib "eagle-import") (part "0.1UF-0603-25V-5%"))
    )
    (comp (ref "C52")
      (value "0.1uF")
      (footprint "eagle-import:0603")
      (libsource (lib "eagle-import") (part "0.1UF-0603-25V-5%"))
    )
    (comp (ref "C53")
      (value "0.1uF")
      (footprint "eagle-import:0603")
      (libsource (lib "eagle-import") (part "0.1UF-0603-25V-5%"))
    )
    (comp (ref "C54")
      (value "0.1uF")
      (footprint "eagle-import:0603")
      (libsource (lib "eagle-import") (part "0.1UF-0603-25V-5%"))
    )
    (comp (ref "C55")
      (value "0.1uF")
      (footprint "eagle-import:0603")
      (libsource (lib "eagle-import") (part "0.1UF-0603-25V-5%"))
    )
    (comp (ref "C56")
      (value "0.1uF")
      (footprint "eagle-import:0603")
      (libsource (lib "eagle-import") (part "0.1UF-0603-25V-5%"))
    )
    (comp (ref "C57")
      (value "0.1uF")
      (footprint "eagle-import:0603")
      (libsource (lib "eagle-import") (part "0.1UF-0603-25V-5%"))
    )
    (comp (ref "C58")
      (value "0.1uF")
      (footprint "eagle-import:0603")
      (libsource (lib "eagle-import") (part "0.1UF-0603-25V-5%"))
    )
    (comp (ref "C59")
      (value "0.1uF")
      (footprint "eagle-import:0603")
      (libsource (lib "eagle-import") (part "0.1UF-0603-25V-5%"))
    )
    (comp (ref "C60")
      (value "0.1uF")
      (footprint "eagle-import:0603")
      (libsource (lib "eagle-import") (part "0.1UF-0603-25V-5%"))
    )
    (comp (ref "C61")
      (value "0.1uF")
      (footprint "eagle-import:0603")
      (libsource (lib "eagle-import") (part "0.1UF-0603-25V-5%"))
    )
    (comp (ref "C62")
      (value "0.1uF")
      (footprint "eagle-import:0603")
      (libsource (lib "eagle-import") (part "0.1UF-0603-25V-5%"))
    )
    (comp (ref "C63")
      (value "0.1uF")
      (footprint "eagle-import:0603")
      (libsource (lib "eagle-import") (part "0.1UF-0603-25V-5%"))
    )
    (comp (ref "C64")
      (value "0.1uF")
      (footprint "eagle-import:0603")
      (libsource (lib "eagle-import") (part "0.1UF-0603-25V-5%"))
    )
    (comp (ref "C65")
      (value "0.1uF")
      (footprint "eagle-import:0603")
      (libsource (lib "eagle-import") (part "0.1UF-0603-25V-5%"))
    )
    (comp (ref "C66")
      (value "0.1uF")
      (footprint "eagle-import:0603")
      (libsource (lib "eagle-import") (part "0.1UF-0603-25V-5%"))
    )
    (comp (ref "C67")
      (value "0.1uF")
      (footprint "eagle-import:0603")
      (libsource (lib "eagle-import") (part "0.1UF-0603-25V-5%"))
    )
    (comp (ref "C68")
      (value "0.1uF")
      (footprint "eagle-import:0603")
      (libsource (lib "eagle-import") (part "0.1UF-0603-25V-5%"))
    )
    (comp (ref "C69")
      (value "0.1uF")
      (footprint "eagle-import:0603")
      (libsource (lib "eagle-import") (part "0.1UF-0603-25V-5%"))
    )
    (comp (ref "C70")
      (value "0.1uF")
      (footprint "eagle-import:0603")
      (libsource (lib "eagle-import") (part "0.1UF-0603-25V-5%"))
    )
    (comp (ref "C71")
      (value "0.1uF")
      (footprint "eagle-import:0603")
      (libsource (lib "eagle-import") (part "0.1UF-0603-25V-5%"))
    )
    (comp (ref "C72")
      (value "0.1uF")
      (footprint "eagle-import:0603")
      (libsource (lib "eagle-import") (part "0.1UF-0603-25V-5%"))
    )
    (comp (ref "C73")
      (value "0.1uF")
      (footprint "eagle-import:0603")
      (libsource (lib "eagle-import") (part "0.1UF-0603-25V-5%"))
    )
    (comp (ref "C74")
      (value "0.1uF")
      (footprint "eagle-import:0603")
      (libsource (lib "eagle-import") (part "0.1UF-0603-25V-5%"))
    )
    (comp (ref "C77")
      (value "0.1uF")
      (footprint "eagle-import:0603")
      (libsource (lib "eagle-import") (part "0.1UF-0603-25V-5%"))
    )
    (comp (ref "C78")
      (value "0.1uF")
      (footprint "eagle-import:0603")
      (libsource (lib "eagle-import") (part "0.1UF-0603-25V-5%"))
    )
    (comp (ref "C79")
      (value "0.1uF")
      (footprint "eagle-import:0603")
      (libsource (lib "eagle-import") (part "0.1UF-0603-25V-5%"))
    )
    (comp (ref "C80")
      (value "0.1uF")
      (footprint "eagle-import:0603")
      (libsource (lib "eagle-import") (part "0.1UF-0603-25V-5%"))
    )
    (comp (ref "C81")
      (value "0.1uF")
      (footprint "eagle-import:0603")
      (libsource (lib "eagle-import") (part "0.1UF-0603-25V-5%"))
    )
    (comp (ref "C82")
      (value "0.1uF")
      (footprint "eagle-import:0603")
      (libsource (lib "eagle-import") (part "0.1UF-0603-25V-5%"))
    )
    (comp (ref "C83")
      (value "0.1uF")
      (footprint "eagle-import:0603")
      (libsource (lib "eagle-import") (part "0.1UF-0603-25V-5%"))
    )
    (comp (ref "C84")
      (value "0.1uF")
      (footprint "eagle-import:0603")
      (libsource (lib "eagle-import") (part "0.1UF-0603-25V-5%"))
    )
    (comp (ref "C85")
      (value "0.1uF")
      (footprint "eagle-import:0603")
      (libsource (lib "eagle-import") (part "0.1UF-0603-25V-5%"))
    )
    (comp (ref "C86")
      (value "0.1uF")
      (footprint "eagle-import:0603")
      (libsource (lib "eagle-import") (part "0.1UF-0603-25V-5%"))
    )
    (comp (ref "C87")
      (value "0.1uF")
      (footprint "eagle-import:0603")
      (libsource (lib "eagle-import") (part "0.1UF-0603-25V-5%"))
    )
    (comp (ref "C88")
      (value "0.1uF")
      (footprint "eagle-import:0603")
      (libsource (lib "eagle-import") (part "0.1UF-0603-25V-5%"))
    )
    (comp (ref "C89")
      (value "0.1uF")
      (footprint "eagle-import:0603")
      (libsource (lib "eagle-import") (part "0.1UF-0603-25V-5%"))
    )
    (comp (ref "C90")
      (value "0.1uF")
      (footprint "eagle-import:0603")
      (libsource (lib "eagle-import") (part "0.1UF-0603-25V-5%"))
    )
    (comp (ref "C91")
      (value "0.1uF")
      (footprint "eagle-import:0603")
      (libsource (lib "eagle-import") (part "0.1UF-0603-25V-5%"))
    )
    (comp (ref "C92")
      (value "0.1uF")
      (footprint "eagle-import:0603")
      (libsource (lib "eagle-import") (part "0.1UF-0603-25V-5%"))
    )
    (comp (ref "C93")
      (value "0.1uF")
      (footprint "eagle-import:0603")
      (libsource (lib "eagle-import") (part "0.1UF-0603-25V-5%"))
    )
    (comp (ref "C94")
      (value "0.1uF")
      (footprint "eagle-import:0603")
      (libsource (lib "eagle-import") (part "0.1UF-0603-25V-5%"))
    )
    (comp (ref "C95")
      (value "0.1uF")
      (footprint "eagle-import:0603")
      (libsource (lib "eagle-import") (part "0.1UF-0603-25V-5%"))
    )
    (comp (ref "C96")
      (value "0.1uF")
      (footprint "eagle-import:0603")
      (libsource (lib "eagle-import") (part "0.1UF-0603-25V-5%"))
    )
    (comp (ref "C97")
      (value "0.1uF")
      (footprint "eagle-import:0603")
      (libsource (lib "eagle-import") (part "0.1UF-0603-25V-5%"))
    )
    (comp (ref "C98")
      (value "0.1uF")
      (footprint "eagle-import:0603")
      (libsource (lib "eagle-import") (part "0.1UF-0603-25V-5%"))
    )
    (comp (ref "C99")
      (value "0.1uF")
      (footprint "eagle-import:0603")
      (libsource (lib "eagle-import") (part "0.1UF-0603-25V-5%"))
    )
    (comp (ref "C100")
      (value "0.1uF")
      (footprint "eagle-import:0603")
      (libsource (lib "eagle-import") (part "0.1UF-0603-25V-5%"))
    )
    (comp (ref "C101")
      (value "0.1uF")
      (footprint "eagle-import:0603")
      (libsource (lib "eagle-import") (part "0.1UF-0603-25V-5%"))
    )
    (comp (ref "C102")
      (value "0.1uF")
      (footprint "eagle-import:0603")
      (libsource (lib "eagle-import") (part "0.1UF-0603-25V-5%"))
    )
    (comp (ref "C103")
      (value "0.1uF")
      (footprint "eagle-import:0603")
      (libsource (lib "eagle-import") (part "0.1UF-0603-25V-5%"))
    )
    (comp (ref "C104")
      (value "0.1uF")
      (footprint "eagle-import:0603")
      (libsource (lib "eagle-import") (part "0.1UF-0603-25V-5%"))
    )
    (comp (ref "C107")
      (value "0.1uF")
      (footprint "eagle-import:0603")
      (libsource (lib "eagle-import") (part "0.1UF-0603-25V-5%"))
    )
    (comp (ref "C108")
      (value "0.1uF")
      (footprint "eagle-import:0603")
      (libsource (lib "eagle-import") (part "0.1UF-0603-25V-5%"))
    )
    (comp (ref "C109")
      (value "0.1uF")
      (footprint "eagle-import:0603")
      (libsource (lib "eagle-import") (part "0.1UF-0603-25V-5%"))
    )
    (comp (ref "C110")
      (value "0.1uF")
      (footprint "eagle-import:0603")
      (libsource (lib "eagle-import") (part "0.1UF-0603-25V-5%"))
    )
    (comp (ref "C111")
      (value "0.1uF")
      (footprint "eagle-import:0603")
      (libsource (lib "eagle-import") (part "0.1UF-0603-25V-5%"))
    )
    (comp (ref "C112")
      (value "0.1uF")
      (footprint "eagle-import:0603")
      (libsource (lib "eagle-import") (part "0.1UF-0603-25V-5%"))
    )
    (comp (ref "C113")
      (value "0.1uF")
      (footprint "eagle-import:0603")
      (libsource (lib "eagle-import") (part "0.1UF-0603-25V-5%"))
    )
    (comp (ref "C114")
      (value "0.1uF")
      (footprint "eagle-import:0603")
      (libsource (lib "eagle-import") (part "0.1UF-0603-25V-5%"))
    )
    (comp (ref "C115")
      (value "0.1uF")
      (footprint "eagle-import:0603")
      (libsource (lib "eagle-import") (part "0.1UF-0603-25V-5%"))
    )
    (comp (ref "C116")
      (value "0.1uF")
      (footprint "eagle-import:0603")
      (libsource (lib "eagle-import") (part "0.1UF-0603-25V-5%"))
    )
    (comp (ref "C117")
      (value "0.1uF")
      (footprint "eagle-import:0603")
      (libsource (lib "eagle-import") (part "0.1UF-0603-25V-5%"))
    )
    (comp (ref "C118")
      (value "0.1uF")
      (footprint "eagle-import:0603")
      (libsource (lib "eagle-import") (part "0.1UF-0603-25V-5%"))
    )
    (comp (ref "C119")
      (value "0.1uF")
      (footprint "eagle-import:0603")
      (libsource (lib "eagle-import") (part "0.1UF-0603-25V-5%"))
    )
    (comp (ref "C120")
      (value "0.1uF")
      (footprint "eagle-import:0603")
      (libsource (lib "eagle-import") (part "0.1UF-0603-25V-5%"))
    )
    (comp (ref "C121")
      (value "0.1uF")
      (footprint "eagle-import:0603")
      (libsource (lib "eagle-import") (part "0.1UF-0603-25V-5%"))
    )
    (comp (ref "C122")
      (value "0.1uF")
      (footprint "eagle-import:0603")
      (libsource (lib "eagle-import") (part "0.1UF-0603-25V-5%"))
    )
    (comp (ref "C123")
      (value "0.1uF")
      (footprint "eagle-import:0603")
      (libsource (lib "eagle-import") (part "0.1UF-0603-25V-5%"))
    )
    (comp (ref "C124")
      (value "0.1uF")
      (footprint "eagle-import:0603")
      (libsource (lib "eagle-import") (part "0.1UF-0603-25V-5%"))
    )
    (comp (ref "C125")
      (value "0.1uF")
      (footprint "eagle-import:0603")
      (libsource (lib "eagle-import") (part "0.1UF-0603-25V-5%"))
    )
    (comp (ref "C126")
      (value "0.1uF")
      (footprint "eagle-import:0603")
      (libsource (lib "eagle-import") (part "0.1UF-0603-25V-5%"))
    )
    (comp (ref "C127")
      (value "0.1uF")
      (footprint "eagle-import:0603")
      (libsource (lib "eagle-import") (part "0.1UF-0603-25V-5%"))
    )
    (comp (ref "C128")
      (value "0.1uF")
      (footprint "eagle-import:0603")
      (libsource (lib "eagle-import") (part "0.1UF-0603-25V-5%"))
    )
    (comp (ref "C129")
      (value "0.1uF")
      (footprint "eagle-import:0603")
      (libsource (lib "eagle-import") (part "0.1UF-0603-25V-5%"))
    )
    (comp (ref "C130")
      (value "0.1uF")
      (footprint "eagle-import:0603")
      (libsource (lib "eagle-import") (part "0.1UF-0603-25V-5%"))
    )
    (comp (ref "C131")
      (value "0.1uF")
      (footprint "eagle-import:0603")
      (libsource (lib "eagle-import") (part "0.1UF-0603-25V-5%"))
    )
    (comp (ref "C132")
      (value "0.1uF")
      (footprint "eagle-import:0603")
      (libsource (lib "eagle-import") (part "0.1UF-0603-25V-5%"))
    )
    (comp (ref "C133")
      (value "0.1uF")
      (footprint "eagle-import:0603")
      (libsource (lib "eagle-import") (part "0.1UF-0603-25V-5%"))
    )
    (comp (ref "C134")
      (value "0.1uF")
      (footprint "eagle-import:0603")
      (libsource (lib "eagle-import") (part "0.1UF-0603-25V-5%"))
    )
    (comp (ref "C137")
      (value "0.1uF")
      (footprint "eagle-import:0603")
      (libsource (lib "eagle-import") (part "0.1UF-0603-25V-5%"))
    )
    (comp (ref "C138")
      (value "0.1uF")
      (footprint "eagle-import:0603")
      (libsource (lib "eagle-import") (part "0.1UF-0603-25V-5%"))
    )
    (comp (ref "C139")
      (value "0.1uF")
      (footprint "eagle-import:0603")
      (libsource (lib "eagle-import") (part "0.1UF-0603-25V-5%"))
    )
    (comp (ref "C140")
      (value "0.1uF")
      (footprint "eagle-import:0603")
      (libsource (lib "eagle-import") (part "0.1UF-0603-25V-5%"))
    )
    (comp (ref "C141")
      (value "0.1uF")
      (footprint "eagle-import:0603")
      (libsource (lib "eagle-import") (part "0.1UF-0603-25V-5%"))
    )
    (comp (ref "C142")
      (value "0.1uF")
      (footprint "eagle-import:0603")
      (libsource (lib "eagle-import") (part "0.1UF-0603-25V-5%"))
    )
    (comp (ref "C143")
      (value "0.1uF")
      (footprint "eagle-import:0603")
      (libsource (lib "eagle-import") (part "0.1UF-0603-25V-5%"))
    )
    (comp (ref "C144")
      (value "0.1uF")
      (footprint "eagle-import:0603")
      (libsource (lib "eagle-import") (part "0.1UF-0603-25V-5%"))
    )
    (comp (ref "C145")
      (value "0.1uF")
      (footprint "eagle-import:0603")
      (libsource (lib "eagle-import") (part "0.1UF-0603-25V-5%"))
    )
    (comp (ref "C146")
      (value "0.1uF")
      (footprint "eagle-import:0603")
      (libsource (lib "eagle-import") (part "0.1UF-0603-25V-5%"))
    )
    (comp (ref "C147")
      (value "0.1uF")
      (footprint "eagle-import:0603")
      (libsource (lib "eagle-import") (part "0.1UF-0603-25V-5%"))
    )
    (comp (ref "C148")
      (value "0.1uF")
      (footprint "eagle-import:0603")
      (libsource (lib "eagle-import") (part "0.1UF-0603-25V-5%"))
    )
    (comp (ref "C149")
      (value "0.1uF")
      (footprint "eagle-import:0603")
      (libsource (lib "eagle-import") (part "0.1UF-0603-25V-5%"))
    )
    (comp (ref "C150")
      (value "0.1uF")
      (footprint "eagle-import:0603")
      (libsource (lib "eagle-import") (part "0.1UF-0603-25V-5%"))
    )
    (comp (ref "C151")
      (value "0.1uF")
      (footprint "eagle-import:0603")
      (libsource (lib "eagle-import") (part "0.1UF-0603-25V-5%"))
    )
    (comp (ref "C152")
      (value "0.1uF")
      (footprint "eagle-import:0603")
      (libsource (lib "eagle-import") (part "0.1UF-0603-25V-5%"))
    )
    (comp (ref "C153")
      (value "0.1uF")
      (footprint "eagle-import:0603")
      (libsource (lib "eagle-import") (part "0.1UF-0603-25V-5%"))
    )
    (comp (ref "C154")
      (value "0.1uF")
      (footprint "eagle-import:0603")
      (libsource (lib "eagle-import") (part "0.1UF-0603-25V-5%"))
    )
    (comp (ref "C155")
      (value "0.1uF")
      (footprint "eagle-import:0603")
      (libsource (lib "eagle-import") (part "0.1UF-0603-25V-5%"))
    )
    (comp (ref "C156")
      (value "0.1uF")
      (footprint "eagle-import:0603")
      (libsource (lib "eagle-import") (part "0.1UF-0603-25V-5%"))
    )
    (comp (ref "C157")
      (value "0.1uF")
      (footprint "eagle-import:0603")
      (libsource (lib "eagle-import") (part "0.1UF-0603-25V-5%"))
    )
    (comp (ref "C158")
      (value "0.1uF")
      (footprint "eagle-import:0603")
      (libsource (lib "eagle-import") (part "0.1UF-0603-25V-5%"))
    )
    (comp (ref "C159")
      (value "0.1uF")
      (footprint "eagle-import:0603")
      (libsource (lib "eagle-import") (part "0.1UF-0603-25V-5%"))
    )
    (comp (ref "C160")
      (value "0.1uF")
      (footprint "eagle-import:0603")
      (libsource (lib "eagle-import") (part "0.1UF-0603-25V-5%"))
    )
    (comp (ref "C161")
      (value "0.1uF")
      (footprint "eagle-import:0603")
      (libsource (lib "eagle-import") (part "0.1UF-0603-25V-5%"))
    )
    (comp (ref "C162")
      (value "0.1uF")
      (footprint "eagle-import:0603")
      (libsource (lib "eagle-import") (part "0.1UF-0603-25V-5%"))
    )
    (comp (ref "C163")
      (value "0.1uF")
      (footprint "eagle-import:0603")
      (libsource (lib "eagle-import") (part "0.1UF-0603-25V-5%"))
    )
    (comp (ref "C164")
      (value "0.1uF")
      (footprint "eagle-import:0603")
      (libsource (lib "eagle-import") (part "0.1UF-0603-25V-5%"))
    )
    (comp (ref "C167")
      (value "0.1uF")
      (footprint "eagle-import:0603")
      (libsource (lib "eagle-import") (part "0.1UF-0603-25V-5%"))
    )
    (comp (ref "C168")
      (value "0.1uF")
      (footprint "eagle-import:0603")
      (libsource (lib "eagle-import") (part "0.1UF-0603-25V-5%"))
    )
    (comp (ref "C169")
      (value "0.1uF")
      (footprint "eagle-import:0603")
      (libsource (lib "eagle-import") (part "0.1UF-0603-25V-5%"))
    )
    (comp (ref "C170")
      (value "0.1uF")
      (footprint "eagle-import:0603")
      (libsource (lib "eagle-import") (part "0.1UF-0603-25V-5%"))
    )
    (comp (ref "C171")
      (value "0.1uF")
      (footprint "eagle-import:0603")
      (libsource (lib "eagle-import") (part "0.1UF-0603-25V-5%"))
    )
    (comp (ref "C172")
      (value "0.1uF")
      (footprint "eagle-import:0603")
      (libsource (lib "eagle-import") (part "0.1UF-0603-25V-5%"))
    )
    (comp (ref "C173")
      (value "0.1uF")
      (footprint "eagle-import:0603")
      (libsource (lib "eagle-import") (part "0.1UF-0603-25V-5%"))
    )
    (comp (ref "C174")
      (value "0.1uF")
      (footprint "eagle-import:0603")
      (libsource (lib "eagle-import") (part "0.1UF-0603-25V-5%"))
    )
    (comp (ref "C175")
      (value "0.1uF")
      (footprint "eagle-import:0603")
      (libsource (lib "eagle-import") (part "0.1UF-0603-25V-5%"))
    )
    (comp (ref "C176")
      (value "0.1uF")
      (footprint "eagle-import:0603")
      (libsource (lib "eagle-import") (part "0.1UF-0603-25V-5%"))
    )
    (comp (ref "C177")
      (value "0.1uF")
      (footprint "eagle-import:0603")
      (libsource (lib "eagle-import") (part "0.1UF-0603-25V-5%"))
    )
    (comp (ref "C178")
      (value "0.1uF")
      (footprint "eagle-import:0603")
      (libsource (lib "eagle-import") (part "0.1UF-0603-25V-5%"))
    )
    (comp (ref "C179")
      (value "0.1uF")
      (footprint "eagle-import:0603")
      (libsource (lib "eagle-import") (part "0.1UF-0603-25V-5%"))
    )
    (comp (ref "C180")
      (value "0.1uF")
      (footprint "eagle-import:0603")
      (libsource (lib "eagle-import") (part "0.1UF-0603-25V-5%"))
    )
    (comp (ref "C181")
      (value "0.1uF")
      (footprint "eagle-import:0603")
      (libsource (lib "eagle-import") (part "0.1UF-0603-25V-5%"))
    )
    (comp (ref "C182")
      (value "0.1uF")
      (footprint "eagle-import:0603")
      (libsource (lib "eagle-import") (part "0.1UF-0603-100V-10%"))
    )
    (comp (ref "C183")
      (value "0.1uF")
      (footprint "eagle-import:0603")
      (libsource (lib "eagle-import") (part "0.1UF-0603-25V-5%"))
    )
    (comp (ref "C184")
      (value "0.1uF")
      (footprint "eagle-import:0603")
      (libsource (lib "eagle-import") (part "0.1UF-0603-25V-5%"))
    )
    (comp (ref "C185")
      (value "0.1uF")
      (footprint "eagle-import:0603")
      (libsource (lib "eagle-import") (part "0.1UF-0603-25V-5%"))
    )
    (comp (ref "C186")
      (value "0.1uF")
      (footprint "eagle-import:0603")
      (libsource (lib "eagle-import") (part "0.1UF-0603-25V-5%"))
    )
    (comp (ref "C187")
      (value "0.1uF")
      (footprint "eagle-import:0603")
      (libsource (lib "eagle-import") (part "0.1UF-0603-25V-5%"))
    )
    (comp (ref "C188")
      (value "0.1uF")
      (footprint "eagle-import:0603")
      (libsource (lib "eagle-import") (part "0.1UF-0603-25V-5%"))
    )
    (comp (ref "C189")
      (value "0.1uF")
      (footprint "eagle-import:0603")
      (libsource (lib "eagle-import") (part "0.1UF-0603-25V-5%"))
    )
    (comp (ref "C190")
      (value "0.1uF")
      (footprint "eagle-import:0603")
      (libsource (lib "eagle-import") (part "0.1UF-0603-25V-5%"))
    )
    (comp (ref "C191")
      (value "0.1uF")
      (footprint "eagle-import:0603")
      (libsource (lib "eagle-import") (part "0.1UF-0603-25V-5%"))
    )
    (comp (ref "C192")
      (value "0.1uF")
      (footprint "eagle-import:0603")
      (libsource (lib "eagle-import") (part "0.1UF-0603-25V-5%"))
    )
    (comp (ref "C193")
      (value "0.1uF")
      (footprint "eagle-import:0603")
      (libsource (lib "eagle-import") (part "0.1UF-0603-25V-5%"))
    )
    (comp (ref "C194")
      (value "0.1uF")
      (footprint "eagle-import:0603")
      (libsource (lib "eagle-import") (part "0.1UF-0603-25V-5%"))
    )
    (comp (ref "C197")
      (value "0.1uF")
      (footprint "eagle-import:0603")
      (libsource (lib "eagle-import") (part "0.1UF-0603-25V-5%"))
    )
    (comp (ref "C198")
      (value "0.1uF")
      (footprint "eagle-import:0603")
      (libsource (lib "eagle-import") (part "0.1UF-0603-25V-5%"))
    )
    (comp (ref "C199")
      (value "0.1uF")
      (footprint "eagle-import:0603")
      (libsource (lib "eagle-import") (part "0.1UF-0603-25V-5%"))
    )
    (comp (ref "C200")
      (value "0.1uF")
      (footprint "eagle-import:0603")
      (libsource (lib "eagle-import") (part "0.1UF-0603-25V-5%"))
    )
    (comp (ref "C201")
      (value "0.1uF")
      (footprint "eagle-import:0603")
      (libsource (lib "eagle-import") (part "0.1UF-0603-25V-5%"))
    )
    (comp (ref "C202")
      (value "0.1uF")
      (footprint "eagle-import:0603")
      (libsource (lib "eagle-import") (part "0.1UF-0603-25V-5%"))
    )
    (comp (ref "C203")
      (value "0.1uF")
      (footprint "eagle-import:0603")
      (libsource (lib "eagle-import") (part "0.1UF-0603-25V-5%"))
    )
    (comp (ref "C204")
      (value "0.1uF")
      (footprint "eagle-import:0603")
      (libsource (lib "eagle-import") (part "0.1UF-0603-25V-5%"))
    )
    (comp (ref "C205")
      (value "0.1uF")
      (footprint "eagle-import:0603")
      (libsource (lib "eagle-import") (part "0.1UF-0603-25V-5%"))
    )
    (comp (ref "C206")
      (value "0.1uF")
      (footprint "eagle-import:0603")
      (libsource (lib "eagle-import") (part "0.1UF-0603-25V-5%"))
    )
    (comp (ref "C207")
      (value "0.1uF")
      (footprint "eagle-import:0603")
      (libsource (lib "eagle-import") (part "0.1UF-0603-25V-5%"))
    )
    (comp (ref "C208")
      (value "0.1uF")
      (footprint "eagle-import:0603")
      (libsource (lib "eagle-import") (part "0.1UF-0603-25V-5%"))
    )
    (comp (ref "C209")
      (value "0.1uF")
      (footprint "eagle-import:0603")
      (libsource (lib "eagle-import") (part "0.1UF-0603-25V-5%"))
    )
    (comp (ref "C210")
      (value "0.1uF")
      (footprint "eagle-import:0603")
      (libsource (lib "eagle-import") (part "0.1UF-0603-25V-5%"))
    )
    (comp (ref "C211")
      (value "0.1uF")
      (footprint "eagle-import:0603")
      (libsource (lib "eagle-import") (part "0.1UF-0603-25V-5%"))
    )
    (comp (ref "C212")
      (value "0.1uF")
      (footprint "eagle-import:0603")
      (libsource (lib "eagle-import") (part "0.1UF-0603-25V-5%"))
    )
    (comp (ref "C213")
      (value "0.1uF")
      (footprint "eagle-import:0603")
      (libsource (lib "eagle-import") (part "0.1UF-0603-25V-5%"))
    )
    (comp (ref "C214")
      (value "0.1uF")
      (footprint "eagle-import:0603")
      (libsource (lib "eagle-import") (part "0.1UF-0603-25V-5%"))
    )
    (comp (ref "C215")
      (value "0.1uF")
      (footprint "eagle-import:0603")
      (libsource (lib "eagle-import") (part "0.1UF-0603-25V-5%"))
    )
    (comp (ref "C216")
      (value "0.1uF")
      (footprint "eagle-import:0603")
      (libsource (lib "eagle-import") (part "0.1UF-0603-25V-5%"))
    )
    (comp (ref "C217")
      (value "0.1uF")
      (footprint "eagle-import:0603")
      (libsource (lib "eagle-import") (part "0.1UF-0603-25V-5%"))
    )
    (comp (ref "C218")
      (value "0.1uF")
      (footprint "eagle-import:0603")
      (libsource (lib "eagle-import") (part "0.1UF-0603-25V-5%"))
    )
    (comp (ref "C219")
      (value "0.1uF")
      (footprint "eagle-import:0603")
      (libsource (lib "eagle-import") (part "0.1UF-0603-25V-5%"))
    )
    (comp (ref "C220")
      (value "0.1uF")
      (footprint "eagle-import:0603")
      (libsource (lib "eagle-import") (part "0.1UF-0603-25V-5%"))
    )
    (comp (ref "C221")
      (value "0.1uF")
      (footprint "eagle-import:0603")
      (libsource (lib "eagle-import") (part "0.1UF-0603-25V-5%"))
    )
    (comp (ref "C222")
      (value "0.1uF")
      (footprint "eagle-import:0603")
      (libsource (lib "eagle-import") (part "0.1UF-0603-25V-5%"))
    )
    (comp (ref "C223")
      (value "0.1uF")
      (footprint "eagle-import:0603")
      (libsource (lib "eagle-import") (part "0.1UF-0603-25V-5%"))
    )
    (comp (ref "C224")
      (value "0.1uF")
      (footprint "eagle-import:0603")
      (libsource (lib "eagle-import") (part "0.1UF-0603-25V-5%"))
    )
    (comp (ref "D1")
      (value "WS2812B")
      (footprint "eagle-import:WS2812B")
      (libsource (lib "eagle-import") (part "WS2812B"))
    )
    (comp (ref "D2")
      (value "WS2812B")
      (footprint "eagle-import:WS2812B")
      (libsource (lib "eagle-import") (part "WS2812B"))
    )
    (comp (ref "D3")
      (value "WS2812B")
      (footprint "eagle-import:WS2812B")
      (libsource (lib "eagle-import") (part "WS2812B"))
    )
    (comp (ref "D4")
      (value "WS2812B")
      (footprint "eagle-import:WS2812B")
      (libsource (lib "eagle-import") (part "WS2812B"))
    )
    (comp (ref "D5")
      (value "WS2812B")
      (footprint "eagle-import:WS2812B")
      (libsource (lib "eagle-import") (part "WS2812B"))
    )
    (comp (ref "D6")
      (value "WS2812B")
      (footprint "eagle-import:WS2812B")
      (libsource (lib "eagle-import") (part "WS2812B"))
    )
    (comp (ref "D7")
      (value "WS2812B")
      (footprint "eagle-import:WS2812B")
      (libsource (lib "eagle-import") (part "WS2812B"))
    )
    (comp (ref "D8")
      (value "WS2812B")
      (footprint "eagle-import:WS2812B")
      (libsource (lib "eagle-import") (part "WS2812B"))
    )
    (comp (ref "D9")
      (value "WS2812B")
      (footprint "eagle-import:WS2812B")
      (libsource (lib "eagle-import") (part "WS2812B"))
    )
    (comp (ref "D10")
      (value "WS2812B")
      (footprint "eagle-import:WS2812B")
      (libsource (lib "eagle-import") (part "WS2812B"))
    )
    (comp (ref "D11")
      (value "WS2812B")
      (footprint "eagle-import:WS2812B")
      (libsource (lib "eagle-import") (part "WS2812B"))
    )
    (comp (ref "D12")
      (value "WS2812B")
      (footprint "eagle-import:WS2812B")
      (libsource (lib "eagle-import") (part "WS2812B"))
    )
    (comp (ref "D13")
      (value "WS2812B")
      (footprint "eagle-import:WS2812B")
      (libsource (lib "eagle-import") (part "WS2812B"))
    )
    (comp (ref "D14")
      (value "WS2812B")
      (footprint "eagle-import:WS2812B")
      (libsource (lib "eagle-import") (part "WS2812B"))
    )
    (comp (ref "D15")
      (value "WS2812B")
      (footprint "eagle-import:WS2812B")
      (libsource (lib "eagle-import") (part "WS2812B"))
    )
    (comp (ref "D16")
      (value "WS2812B")
      (footprint "eagle-import:WS2812B")
      (libsource (lib "eagle-import") (part "WS2812B"))
    )
    (comp (ref "D17")
      (value "WS2812B")
      (footprint "eagle-import:WS2812B")
      (libsource (lib "eagle-import") (part "WS2812B"))
    )
    (comp (ref "D18")
      (value "WS2812B")
      (footprint "eagle-import:WS2812B")
      (libsource (lib "eagle-import") (part "WS2812B"))
    )
    (comp (ref "D19")
      (value "WS2812B")
      (footprint "eagle-import:WS2812B")
      (libsource (lib "eagle-import") (part "WS2812B"))
    )
    (comp (ref "D20")
      (value "WS2812B")
      (footprint "eagle-import:WS2812B")
      (libsource (lib "eagle-import") (part "WS2812B"))
    )
    (comp (ref "D21")
      (value "WS2812B")
      (footprint "eagle-import:WS2812B")
      (libsource (lib "eagle-import") (part "WS2812B"))
    )
    (comp (ref "D22")
      (value "WS2812B")
      (footprint "eagle-import:WS2812B")
      (libsource (lib "eagle-import") (part "WS2812B"))
    )
    (comp (ref "D23")
      (value "WS2812B")
      (footprint "eagle-import:WS2812B")
      (libsource (lib "eagle-import") (part "WS2812B"))
    )
    (comp (ref "D24")
      (value "WS2812B")
      (footprint "eagle-import:WS2812B")
      (libsource (lib "eagle-import") (part "WS2812B"))
    )
    (comp (ref "D25")
      (value "WS2812B")
      (footprint "eagle-import:WS2812B")
      (libsource (lib "eagle-import") (part "WS2812B"))
    )
    (comp (ref "D26")
      (value "WS2812B")
      (footprint "eagle-import:WS2812B")
      (libsource (lib "eagle-import") (part "WS2812B"))
    )
    (comp (ref "D27")
      (value "WS2812B")
      (footprint "eagle-import:WS2812B")
      (libsource (lib "eagle-import") (part "WS2812B"))
    )
    (comp (ref "D28")
      (value "WS2812B")
      (footprint "eagle-import:WS2812B")
      (libsource (lib "eagle-import") (part "WS2812B"))
    )
    (comp (ref "D29")
      (value "WS2812B")
      (footprint "eagle-import:WS2812B")
      (libsource (lib "eagle-import") (part "WS2812B"))
    )
    (comp (ref "D30")
      (value "WS2812B")
      (footprint "eagle-import:WS2812B")
      (libsource (lib "eagle-import") (part "WS2812B"))
    )
    (comp (ref "D31")
      (value "WS2812B")
      (footprint "eagle-import:WS2812B")
      (libsource (lib "eagle-import") (part "WS2812B"))
    )
    (comp (ref "D32")
      (value "WS2812B")
      (footprint "eagle-import:WS2812B")
      (libsource (lib "eagle-import") (part "WS2812B"))
    )
    (comp (ref "D33")
      (value "WS2812B")
      (footprint "eagle-import:WS2812B")
      (libsource (lib "eagle-import") (part "WS2812B"))
    )
    (comp (ref "D34")
      (value "WS2812B")
      (footprint "eagle-import:WS2812B")
      (libsource (lib "eagle-import") (part "WS2812B"))
    )
    (comp (ref "D35")
      (value "WS2812B")
      (footprint "eagle-import:WS2812B")
      (libsource (lib "eagle-import") (part "WS2812B"))
    )
    (comp (ref "D36")
      (value "WS2812B")
      (footprint "eagle-import:WS2812B")
      (libsource (lib "eagle-import") (part "WS2812B"))
    )
    (comp (ref "D37")
      (value "WS2812B")
      (footprint "eagle-import:WS2812B")
      (libsource (lib "eagle-import") (part "WS2812B"))
    )
    (comp (ref "D38")
      (value "WS2812B")
      (footprint "eagle-import:WS2812B")
      (libsource (lib "eagle-import") (part "WS2812B"))
    )
    (comp (ref "D39")
      (value "WS2812B")
      (footprint "eagle-import:WS2812B")
      (libsource (lib "eagle-import") (part "WS2812B"))
    )
    (comp (ref "D40")
      (value "WS2812B")
      (footprint "eagle-import:WS2812B")
      (libsource (lib "eagle-import") (part "WS2812B"))
    )
    (comp (ref "D41")
      (value "WS2812B")
      (footprint "eagle-import:WS2812B")
      (libsource (lib "eagle-import") (part "WS2812B"))
    )
    (comp (ref "D42")
      (value "WS2812B")
      (footprint "eagle-import:WS2812B")
      (libsource (lib "eagle-import") (part "WS2812B"))
    )
    (comp (ref "D43")
      (value "WS2812B")
      (footprint "eagle-import:WS2812B")
      (libsource (lib "eagle-import") (part "WS2812B"))
    )
    (comp (ref "D44")
      (value "WS2812B")
      (footprint "eagle-import:WS2812B")
      (libsource (lib "eagle-import") (part "WS2812B"))
    )
    (comp (ref "D45")
      (value "WS2812B")
      (footprint "eagle-import:WS2812B")
      (libsource (lib "eagle-import") (part "WS2812B"))
    )
    (comp (ref "D46")
      (value "WS2812B")
      (footprint "eagle-import:WS2812B")
      (libsource (lib "eagle-import") (part "WS2812B"))
    )
    (comp (ref "D47")
      (value "WS2812B")
      (footprint "eagle-import:WS2812B")
      (libsource (lib "eagle-import") (part "WS2812B"))
    )
    (comp (ref "D48")
      (value "WS2812B")
      (footprint "eagle-import:WS2812B")
      (libsource (lib "eagle-import") (part "WS2812B"))
    )
    (comp (ref "D49")
      (value "WS2812B")
      (footprint "eagle-import:WS2812B")
      (libsource (lib "eagle-import") (part "WS2812B"))
    )
    (comp (ref "D50")
      (value "WS2812B")
      (footprint "eagle-import:WS2812B")
      (libsource (lib "eagle-import") (part "WS2812B"))
    )
    (comp (ref "D51")
      (value "WS2812B")
      (footprint "eagle-import:WS2812B")
      (libsource (lib "eagle-import") (part "WS2812B"))
    )
    (comp (ref "D52")
      (value "WS2812B")
      (footprint "eagle-import:WS2812B")
      (libsource (lib "eagle-import") (part "WS2812B"))
    )
    (comp (ref "D53")
      (value "WS2812B")
      (footprint "eagle-import:WS2812B")
      (libsource (lib "eagle-import") (part "WS2812B"))
    )
    (comp (ref "D54")
      (value "WS2812B")
      (footprint "eagle-import:WS2812B")
      (libsource (lib "eagle-import") (part "WS2812B"))
    )
    (comp (ref "D55")
      (value "WS2812B")
      (footprint "eagle-import:WS2812B")
      (libsource (lib "eagle-import") (part "WS2812B"))
    )
    (comp (ref "D56")
      (value "WS2812B")
      (footprint "eagle-import:WS2812B")
      (libsource (lib "eagle-import") (part "WS2812B"))
    )
    (comp (ref "D57")
      (value "WS2812B")
      (footprint "eagle-import:WS2812B")
      (libsource (lib "eagle-import") (part "WS2812B"))
    )
    (comp (ref "D58")
      (value "WS2812B")
      (footprint "eagle-import:WS2812B")
      (libsource (lib "eagle-import") (part "WS2812B"))
    )
    (comp (ref "D59")
      (value "WS2812B")
      (footprint "eagle-import:WS2812B")
      (libsource (lib "eagle-import") (part "WS2812B"))
    )
    (comp (ref "D60")
      (value "WS2812B")
      (footprint "eagle-import:WS2812B")
      (libsource (lib "eagle-import") (part "WS2812B"))
    )
    (comp (ref "D61")
      (value "WS2812B")
      (footprint "eagle-import:WS2812B")
      (libsource (lib "eagle-import") (part "WS2812B"))
    )
    (comp (ref "D62")
      (value "WS2812B")
      (footprint "eagle-import:WS2812B")
      (libsource (lib "eagle-import") (part "WS2812B"))
    )
    (comp (ref "D63")
      (value "WS2812B")
      (footprint "eagle-import:WS2812B")
      (libsource (lib "eagle-import") (part "WS2812B"))
    )
    (comp (ref "D64")
      (value "WS2812B")
      (footprint "eagle-import:WS2812B")
      (libsource (lib "eagle-import") (part "WS2812B"))
    )
    (comp (ref "D65")
      (value "WS2812B")
      (footprint "eagle-import:WS2812B")
      (libsource (lib "eagle-import") (part "WS2812B"))
    )
    (comp (ref "D66")
      (value "WS2812B")
      (footprint "eagle-import:WS2812B")
      (libsource (lib "eagle-import") (part "WS2812B"))
    )
    (comp (ref "D67")
      (value "WS2812B")
      (footprint "eagle-import:WS2812B")
      (libsource (lib "eagle-import") (part "WS2812B"))
    )
    (comp (ref "D68")
      (value "WS2812B")
      (footprint "eagle-import:WS2812B")
      (libsource (lib "eagle-import") (part "WS2812B"))
    )
    (comp (ref "D69")
      (value "WS2812B")
      (footprint "eagle-import:WS2812B")
      (libsource (lib "eagle-import") (part "WS2812B"))
    )
    (comp (ref "D70")
      (value "WS2812B")
      (footprint "eagle-import:WS2812B")
      (libsource (lib "eagle-import") (part "WS2812B"))
    )
    (comp (ref "D71")
      (value "WS2812B")
      (footprint "eagle-import:WS2812B")
      (libsource (lib "eagle-import") (part "WS2812B"))
    )
    (comp (ref "D72")
      (value "WS2812B")
      (footprint "eagle-import:WS2812B")
      (libsource (lib "eagle-import") (part "WS2812B"))
    )
    (comp (ref "D73")
      (value "WS2812B")
      (footprint "eagle-import:WS2812B")
      (libsource (lib "eagle-import") (part "WS2812B"))
    )
    (comp (ref "D74")
      (value "WS2812B")
      (footprint "eagle-import:WS2812B")
      (libsource (lib "eagle-import") (part "WS2812B"))
    )
    (comp (ref "D75")
      (value "WS2812B")
      (footprint "eagle-import:WS2812B")
      (libsource (lib "eagle-import") (part "WS2812B"))
    )
    (comp (ref "D76")
      (value "WS2812B")
      (footprint "eagle-import:WS2812B")
      (libsource (lib "eagle-import") (part "WS2812B"))
    )
    (comp (ref "D77")
      (value "WS2812B")
      (footprint "eagle-import:WS2812B")
      (libsource (lib "eagle-import") (part "WS2812B"))
    )
    (comp (ref "D78")
      (value "WS2812B")
      (footprint "eagle-import:WS2812B")
      (libsource (lib "eagle-import") (part "WS2812B"))
    )
    (comp (ref "D79")
      (value "WS2812B")
      (footprint "eagle-import:WS2812B")
      (libsource (lib "eagle-import") (part "WS2812B"))
    )
    (comp (ref "D80")
      (value "WS2812B")
      (footprint "eagle-import:WS2812B")
      (libsource (lib "eagle-import") (part "WS2812B"))
    )
    (comp (ref "D81")
      (value "WS2812B")
      (footprint "eagle-import:WS2812B")
      (libsource (lib "eagle-import") (part "WS2812B"))
    )
    (comp (ref "D82")
      (value "WS2812B")
      (footprint "eagle-import:WS2812B")
      (libsource (lib "eagle-import") (part "WS2812B"))
    )
    (comp (ref "D83")
      (value "WS2812B")
      (footprint "eagle-import:WS2812B")
      (libsource (lib "eagle-import") (part "WS2812B"))
    )
    (comp (ref "D84")
      (value "WS2812B")
      (footprint "eagle-import:WS2812B")
      (libsource (lib "eagle-import") (part "WS2812B"))
    )
    (comp (ref "D85")
      (value "WS2812B")
      (footprint "eagle-import:WS2812B")
      (libsource (lib "eagle-import") (part "WS2812B"))
    )
    (comp (ref "D86")
      (value "WS2812B")
      (footprint "eagle-import:WS2812B")
      (libsource (lib "eagle-import") (part "WS2812B"))
    )
    (comp (ref "D87")
      (value "WS2812B")
      (footprint "eagle-import:WS2812B")
      (libsource (lib "eagle-import") (part "WS2812B"))
    )
    (comp (ref "D88")
      (value "WS2812B")
      (footprint "eagle-import:WS2812B")
      (libsource (lib "eagle-import") (part "WS2812B"))
    )
    (comp (ref "D89")
      (value "WS2812B")
      (footprint "eagle-import:WS2812B")
      (libsource (lib "eagle-import") (part "WS2812B"))
    )
    (comp (ref "D90")
      (value "WS2812B")
      (footprint "eagle-import:WS2812B")
      (libsource (lib "eagle-import") (part "WS2812B"))
    )
    (comp (ref "D91")
      (value "WS2812B")
      (footprint "eagle-import:WS2812B")
      (libsource (lib "eagle-import") (part "WS2812B"))
    )
    (comp (ref "D92")
      (value "WS2812B")
      (footprint "eagle-import:WS2812B")
      (libsource (lib "eagle-import") (part "WS2812B"))
    )
    (comp (ref "D93")
      (value "WS2812B")
      (footprint "eagle-import:WS2812B")
      (libsource (lib "eagle-import") (part "WS2812B"))
    )
    (comp (ref "D94")
      (value "WS2812B")
      (footprint "eagle-import:WS2812B")
      (libsource (lib "eagle-import") (part "WS2812B"))
    )
    (comp (ref "D95")
      (value "WS2812B")
      (footprint "eagle-import:WS2812B")
      (libsource (lib "eagle-import") (part "WS2812B"))
    )
    (comp (ref "D96")
      (value "WS2812B")
      (footprint "eagle-import:WS2812B")
      (libsource (lib "eagle-import") (part "WS2812B"))
    )
    (comp (ref "D97")
      (value "WS2812B")
      (footprint "eagle-import:WS2812B")
      (libsource (lib "eagle-import") (part "WS2812B"))
    )
    (comp (ref "D98")
      (value "WS2812B")
      (footprint "eagle-import:WS2812B")
      (libsource (lib "eagle-import") (part "WS2812B"))
    )
    (comp (ref "D99")
      (value "WS2812B")
      (footprint "eagle-import:WS2812B")
      (libsource (lib "eagle-import") (part "WS2812B"))
    )
    (comp (ref "D100")
      (value "WS2812B")
      (footprint "eagle-import:WS2812B")
      (libsource (lib "eagle-import") (part "WS2812B"))
    )
    (comp (ref "D101")
      (value "WS2812B")
      (footprint "eagle-import:WS2812B")
      (libsource (lib "eagle-import") (part "WS2812B"))
    )
    (comp (ref "D102")
      (value "WS2812B")
      (footprint "eagle-import:WS2812B")
      (libsource (lib "eagle-import") (part "WS2812B"))
    )
    (comp (ref "D103")
      (value "WS2812B")
      (footprint "eagle-import:WS2812B")
      (libsource (lib "eagle-import") (part "WS2812B"))
    )
    (comp (ref "D104")
      (value "WS2812B")
      (footprint "eagle-import:WS2812B")
      (libsource (lib "eagle-import") (part "WS2812B"))
    )
    (comp (ref "D105")
      (value "WS2812B")
      (footprint "eagle-import:WS2812B")
      (libsource (lib "eagle-import") (part "WS2812B"))
    )
    (comp (ref "D106")
      (value "WS2812B")
      (footprint "eagle-import:WS2812B")
      (libsource (lib "eagle-import") (part "WS2812B"))
    )
    (comp (ref "D107")
      (value "WS2812B")
      (footprint "eagle-import:WS2812B")
      (libsource (lib "eagle-import") (part "WS2812B"))
    )
    (comp (ref "D108")
      (value "WS2812B")
      (footprint "eagle-import:WS2812B")
      (libsource (lib "eagle-import") (part "WS2812B"))
    )
    (comp (ref "D109")
      (value "WS2812B")
      (footprint "eagle-import:WS2812B")
      (libsource (lib "eagle-import") (part "WS2812B"))
    )
    (comp (ref "D110")
      (value "WS2812B")
      (footprint "eagle-import:WS2812B")
      (libsource (lib "eagle-import") (part "WS2812B"))
    )
    (comp (ref "D111")
      (value "WS2812B")
      (footprint "eagle-import:WS2812B")
      (libsource (lib "eagle-import") (part "WS2812B"))
    )
    (comp (ref "D112")
      (value "WS2812B")
      (footprint "eagle-import:WS2812B")
      (libsource (lib "eagle-import") (part "WS2812B"))
    )
    (comp (ref "D113")
      (value "WS2812B")
      (footprint "eagle-import:WS2812B")
      (libsource (lib "eagle-import") (part "WS2812B"))
    )
    (comp (ref "D114")
      (value "WS2812B")
      (footprint "eagle-import:WS2812B")
      (libsource (lib "eagle-import") (part "WS2812B"))
    )
    (comp (ref "D115")
      (value "WS2812B")
      (footprint "eagle-import:WS2812B")
      (libsource (lib "eagle-import") (part "WS2812B"))
    )
    (comp (ref "D116")
      (value "WS2812B")
      (footprint "eagle-import:WS2812B")
      (libsource (lib "eagle-import") (part "WS2812B"))
    )
    (comp (ref "D117")
      (value "WS2812B")
      (footprint "eagle-import:WS2812B")
      (libsource (lib "eagle-import") (part "WS2812B"))
    )
    (comp (ref "D118")
      (value "WS2812B")
      (footprint "eagle-import:WS2812B")
      (libsource (lib "eagle-import") (part "WS2812B"))
    )
    (comp (ref "D119")
      (value "WS2812B")
      (footprint "eagle-import:WS2812B")
      (libsource (lib "eagle-import") (part "WS2812B"))
    )
    (comp (ref "D120")
      (value "WS2812B")
      (footprint "eagle-import:WS2812B")
      (libsource (lib "eagle-import") (part "WS2812B"))
    )
    (comp (ref "D121")
      (value "WS2812B")
      (footprint "eagle-import:WS2812B")
      (libsource (lib "eagle-import") (part "WS2812B"))
    )
    (comp (ref "D122")
      (value "WS2812B")
      (footprint "eagle-import:WS2812B")
      (libsource (lib "eagle-import") (part "WS2812B"))
    )
    (comp (ref "D123")
      (value "WS2812B")
      (footprint "eagle-import:WS2812B")
      (libsource (lib "eagle-import") (part "WS2812B"))
    )
    (comp (ref "D124")
      (value "WS2812B")
      (footprint "eagle-import:WS2812B")
      (libsource (lib "eagle-import") (part "WS2812B"))
    )
    (comp (ref "D125")
      (value "WS2812B")
      (footprint "eagle-import:WS2812B")
      (libsource (lib "eagle-import") (part "WS2812B"))
    )
    (comp (ref "D126")
      (value "WS2812B")
      (footprint "eagle-import:WS2812B")
      (libsource (lib "eagle-import") (part "WS2812B"))
    )
    (comp (ref "D127")
      (value "WS2812B")
      (footprint "eagle-import:WS2812B")
      (libsource (lib "eagle-import") (part "WS2812B"))
    )
    (comp (ref "D128")
      (value "WS2812B")
      (footprint "eagle-import:WS2812B")
      (libsource (lib "eagle-import") (part "WS2812B"))
    )
    (comp (ref "D129")
      (value "WS2812B")
      (footprint "eagle-import:WS2812B")
      (libsource (lib "eagle-import") (part "WS2812B"))
    )
    (comp (ref "D130")
      (value "WS2812B")
      (footprint "eagle-import:WS2812B")
      (libsource (lib "eagle-import") (part "WS2812B"))
    )
    (comp (ref "D131")
      (value "WS2812B")
      (footprint "eagle-import:WS2812B")
      (libsource (lib "eagle-import") (part "WS2812B"))
    )
    (comp (ref "D132")
      (value "WS2812B")
      (footprint "eagle-import:WS2812B")
      (libsource (lib "eagle-import") (part "WS2812B"))
    )
    (comp (ref "D133")
      (value "WS2812B")
      (footprint "eagle-import:WS2812B")
      (libsource (lib "eagle-import") (part "WS2812B"))
    )
    (comp (ref "D134")
      (value "WS2812B")
      (footprint "eagle-import:WS2812B")
      (libsource (lib "eagle-import") (part "WS2812B"))
    )
    (comp (ref "D135")
      (value "WS2812B")
      (footprint "eagle-import:WS2812B")
      (libsource (lib "eagle-import") (part "WS2812B"))
    )
    (comp (ref "D136")
      (value "WS2812B")
      (footprint "eagle-import:WS2812B")
      (libsource (lib "eagle-import") (part "WS2812B"))
    )
    (comp (ref "D137")
      (value "WS2812B")
      (footprint "eagle-import:WS2812B")
      (libsource (lib "eagle-import") (part "WS2812B"))
    )
    (comp (ref "D138")
      (value "WS2812B")
      (footprint "eagle-import:WS2812B")
      (libsource (lib "eagle-import") (part "WS2812B"))
    )
    (comp (ref "D139")
      (value "WS2812B")
      (footprint "eagle-import:WS2812B")
      (libsource (lib "eagle-import") (part "WS2812B"))
    )
    (comp (ref "D140")
      (value "WS2812B")
      (footprint "eagle-import:WS2812B")
      (libsource (lib "eagle-import") (part "WS2812B"))
    )
    (comp (ref "D141")
      (value "WS2812B")
      (footprint "eagle-import:WS2812B")
      (libsource (lib "eagle-import") (part "WS2812B"))
    )
    (comp (ref "D142")
      (value "WS2812B")
      (footprint "eagle-import:WS2812B")
      (libsource (lib "eagle-import") (part "WS2812B"))
    )
    (comp (ref "D143")
      (value "WS2812B")
      (footprint "eagle-import:WS2812B")
      (libsource (lib "eagle-import") (part "WS2812B"))
    )
    (comp (ref "D144")
      (value "WS2812B")
      (footprint "eagle-import:WS2812B")
      (libsource (lib "eagle-import") (part "WS2812B"))
    )
    (comp (ref "D145")
      (value "WS2812B")
      (footprint "eagle-import:WS2812B")
      (libsource (lib "eagle-import") (part "WS2812B"))
    )
    (comp (ref "D146")
      (value "WS2812B")
      (footprint "eagle-import:WS2812B")
      (libsource (lib "eagle-import") (part "WS2812B"))
    )
    (comp (ref "D147")
      (value "WS2812B")
      (footprint "eagle-import:WS2812B")
      (libsource (lib "eagle-import") (part "WS2812B"))
    )
    (comp (ref "D148")
      (value "WS2812B")
      (footprint "eagle-import:WS2812B")
      (libsource (lib "eagle-import") (part "WS2812B"))
    )
    (comp (ref "D149")
      (value "WS2812B")
      (footprint "eagle-import:WS2812B")
      (libsource (lib "eagle-import") (part "WS2812B"))
    )
    (comp (ref "D150")
      (value "WS2812B")
      (footprint "eagle-import:WS2812B")
      (libsource (lib "eagle-import") (part "WS2812B"))
    )
    (comp (ref "D151")
      (value "WS2812B")
      (footprint "eagle-import:WS2812B")
      (libsource (lib "eagle-import") (part "WS2812B"))
    )
    (comp (ref "D152")
      (value "WS2812B")
      (footprint "eagle-import:WS2812B")
      (libsource (lib "eagle-import") (part "WS2812B"))
    )
    (comp (ref "D153")
      (value "WS2812B")
      (footprint "eagle-import:WS2812B")
      (libsource (lib "eagle-import") (part "WS2812B"))
    )
    (comp (ref "D154")
      (value "WS2812B")
      (footprint "eagle-import:WS2812B")
      (libsource (lib "eagle-import") (part "WS2812B"))
    )
    (comp (ref "D155")
      (value "WS2812B")
      (footprint "eagle-import:WS2812B")
      (libsource (lib "eagle-import") (part "WS2812B"))
    )
    (comp (ref "D156")
      (value "WS2812B")
      (footprint "eagle-import:WS2812B")
      (libsource (lib "eagle-import") (part "WS2812B"))
    )
    (comp (ref "D157")
      (value "WS2812B")
      (footprint "eagle-import:WS2812B")
      (libsource (lib "eagle-import") (part "WS2812B"))
    )
    (comp (ref "D158")
      (value "WS2812B")
      (footprint "eagle-import:WS2812B")
      (libsource (lib "eagle-import") (part "WS2812B"))
    )
    (comp (ref "D159")
      (value "WS2812B")
      (footprint "eagle-import:WS2812B")
      (libsource (lib "eagle-import") (part "WS2812B"))
    )
    (comp (ref "D160")
      (value "WS2812B")
      (footprint "eagle-import:WS2812B")
      (libsource (lib "eagle-import") (part "WS2812B"))
    )
    (comp (ref "D161")
      (value "WS2812B")
      (footprint "eagle-import:WS2812B")
      (libsource (lib "eagle-import") (part "WS2812B"))
    )
    (comp (ref "D162")
      (value "WS2812B")
      (footprint "eagle-import:WS2812B")
      (libsource (lib "eagle-import") (part "WS2812B"))
    )
    (comp (ref "D163")
      (value "WS2812B")
      (footprint "eagle-import:WS2812B")
      (libsource (lib "eagle-import") (part "WS2812B"))
    )
    (comp (ref "D164")
      (value "WS2812B")
      (footprint "eagle-import:WS2812B")
      (libsource (lib "eagle-import") (part "WS2812B"))
    )
    (comp (ref "D165")
      (value "WS2812B")
      (footprint "eagle-import:WS2812B")
      (libsource (lib "eagle-import") (part "WS2812B"))
    )
    (comp (ref "D166")
      (value "WS2812B")
      (footprint "eagle-import:WS2812B")
      (libsource (lib "eagle-import") (part "WS2812B"))
    )
    (comp (ref "D167")
      (value "WS2812B")
      (footprint "eagle-import:WS2812B")
      (libsource (lib "eagle-import") (part "WS2812B"))
    )
    (comp (ref "D168")
      (value "WS2812B")
      (footprint "eagle-import:WS2812B")
      (libsource (lib "eagle-import") (part "WS2812B"))
    )
    (comp (ref "D169")
      (value "WS2812B")
      (footprint "eagle-import:WS2812B")
      (libsource (lib "eagle-import") (part "WS2812B"))
    )
    (comp (ref "D170")
      (value "WS2812B")
      (footprint "eagle-import:WS2812B")
      (libsource (lib "eagle-import") (part "WS2812B"))
    )
    (comp (ref "D171")
      (value "WS2812B")
      (footprint "eagle-import:WS2812B")
      (libsource (lib "eagle-import") (part "WS2812B"))
    )
    (comp (ref "D172")
      (value "WS2812B")
      (footprint "eagle-import:WS2812B")
      (libsource (lib "eagle-import") (part "WS2812B"))
    )
    (comp (ref "D173")
      (value "WS2812B")
      (footprint "eagle-import:WS2812B")
      (libsource (lib "eagle-import") (part "WS2812B"))
    )
    (comp (ref "D174")
      (value "WS2812B")
      (footprint "eagle-import:WS2812B")
      (libsource (lib "eagle-import") (part "WS2812B"))
    )
    (comp (ref "D175")
      (value "WS2812B")
      (footprint "eagle-import:WS2812B")
      (libsource (lib "eagle-import") (part "WS2812B"))
    )
    (comp (ref "D176")
      (value "WS2812B")
      (footprint "eagle-import:WS2812B")
      (libsource (lib "eagle-import") (part "WS2812B"))
    )
    (comp (ref "D177")
      (value "WS2812B")
      (footprint "eagle-import:WS2812B")
      (libsource (lib "eagle-import") (part "WS2812B"))
    )
    (comp (ref "D178")
      (value "WS2812B")
      (footprint "eagle-import:WS2812B")
      (libsource (lib "eagle-import") (part "WS2812B"))
    )
    (comp (ref "D179")
      (value "WS2812B")
      (footprint "eagle-import:WS2812B")
      (libsource (lib "eagle-import") (part "WS2812B"))
    )
    (comp (ref "D180")
      (value "WS2812B")
      (footprint "eagle-import:WS2812B")
      (libsource (lib "eagle-import") (part "WS2812B"))
    )
    (comp (ref "D181")
      (value "WS2812B")
      (footprint "eagle-import:WS2812B")
      (libsource (lib "eagle-import") (part "WS2812B"))
    )
    (comp (ref "D182")
      (value "WS2812B")
      (footprint "eagle-import:WS2812B")
      (libsource (lib "eagle-import") (part "WS2812B"))
    )
    (comp (ref "D183")
      (value "WS2812B")
      (footprint "eagle-import:WS2812B")
      (libsource (lib "eagle-import") (part "WS2812B"))
    )
    (comp (ref "D184")
      (value "WS2812B")
      (footprint "eagle-import:WS2812B")
      (libsource (lib "eagle-import") (part "WS2812B"))
    )
    (comp (ref "D185")
      (value "WS2812B")
      (footprint "eagle-import:WS2812B")
      (libsource (lib "eagle-import") (part "WS2812B"))
    )
    (comp (ref "D186")
      (value "WS2812B")
      (footprint "eagle-import:WS2812B")
      (libsource (lib "eagle-import") (part "WS2812B"))
    )
    (comp (ref "D187")
      (value "WS2812B")
      (footprint "eagle-import:WS2812B")
      (libsource (lib "eagle-import") (part "WS2812B"))
    )
    (comp (ref "D188")
      (value "WS2812B")
      (footprint "eagle-import:WS2812B")
      (libsource (lib "eagle-import") (part "WS2812B"))
    )
    (comp (ref "D189")
      (value "WS2812B")
      (footprint "eagle-import:WS2812B")
      (libsource (lib "eagle-import") (part "WS2812B"))
    )
    (comp (ref "D190")
      (value "WS2812B")
      (footprint "eagle-import:WS2812B")
      (libsource (lib "eagle-import") (part "WS2812B"))
    )
    (comp (ref "D191")
      (value "WS2812B")
      (footprint "eagle-import:WS2812B")
      (libsource (lib "eagle-import") (part "WS2812B"))
    )
    (comp (ref "D192")
      (value "WS2812B")
      (footprint "eagle-import:WS2812B")
      (libsource (lib "eagle-import") (part "WS2812B"))
    )
    (comp (ref "D193")
      (value "WS2812B")
      (footprint "eagle-import:WS2812B")
      (libsource (lib "eagle-import") (part "WS2812B"))
    )
    (comp (ref "D194")
      (value "WS2812B")
      (footprint "eagle-import:WS2812B")
      (libsource (lib "eagle-import") (part "WS2812B"))
    )
    (comp (ref "D195")
      (value "WS2812B")
      (footprint "eagle-import:WS2812B")
      (libsource (lib "eagle-import") (part "WS2812B"))
    )
    (comp (ref "D196")
      (value "WS2812B")
      (footprint "eagle-import:WS2812B")
      (libsource (lib "eagle-import") (part "WS2812B"))
    )
    (comp (ref "D197")
      (value "WS2812B")
      (footprint "eagle-import:WS2812B")
      (libsource (lib "eagle-import") (part "WS2812B"))
    )
    (comp (ref "D198")
      (value "WS2812B")
      (footprint "eagle-import:WS2812B")
      (libsource (lib "eagle-import") (part "WS2812B"))
    )
    (comp (ref "D199")
      (value "WS2812B")
      (footprint "eagle-import:WS2812B")
      (libsource (lib "eagle-import") (part "WS2812B"))
    )
    (comp (ref "D200")
      (value "WS2812B")
      (footprint "eagle-import:WS2812B")
      (libsource (lib "eagle-import") (part "WS2812B"))
    )
    (comp (ref "D201")
      (value "WS2812B")
      (footprint "eagle-import:WS2812B")
      (libsource (lib "eagle-import") (part "WS2812B"))
    )
    (comp (ref "D202")
      (value "WS2812B")
      (footprint "eagle-import:WS2812B")
      (libsource (lib "eagle-import") (part "WS2812B"))
    )
    (comp (ref "D203")
      (value "WS2812B")
      (footprint "eagle-import:WS2812B")
      (libsource (lib "eagle-import") (part "WS2812B"))
    )
    (comp (ref "D204")
      (value "WS2812B")
      (footprint "eagle-import:WS2812B")
      (libsource (lib "eagle-import") (part "WS2812B"))
    )
    (comp (ref "D205")
      (value "WS2812B")
      (footprint "eagle-import:WS2812B")
      (libsource (lib "eagle-import") (part "WS2812B"))
    )
    (comp (ref "D206")
      (value "WS2812B")
      (footprint "eagle-import:WS2812B")
      (libsource (lib "eagle-import") (part "WS2812B"))
    )
    (comp (ref "D207")
      (value "WS2812B")
      (footprint "eagle-import:WS2812B")
      (libsource (lib "eagle-import") (part "WS2812B"))
    )
    (comp (ref "D208")
      (value "WS2812B")
      (footprint "eagle-import:WS2812B")
      (libsource (lib "eagle-import") (part "WS2812B"))
    )
    (comp (ref "D209")
      (value "WS2812B")
      (footprint "eagle-import:WS2812B")
      (libsource (lib "eagle-import") (part "WS2812B"))
    )
    (comp (ref "D210")
      (value "WS2812B")
      (footprint "eagle-import:WS2812B")
      (libsource (lib "eagle-import") (part "WS2812B"))
    )
    (comp (ref "D211")
      (value "WS2812B")
      (footprint "eagle-import:WS2812B")
      (libsource (lib "eagle-import") (part "WS2812B"))
    )
    (comp (ref "D212")
      (value "WS2812B")
      (footprint "eagle-import:WS2812B")
      (libsource (lib "eagle-import") (part "WS2812B"))
    )
    (comp (ref "D213")
      (value "WS2812B")
      (footprint "eagle-import:WS2812B")
      (libsource (lib "eagle-import") (part "WS2812B"))
    )
    (comp (ref "D214")
      (value "WS2812B")
      (footprint "eagle-import:WS2812B")
      (libsource (lib "eagle-import") (part "WS2812B"))
    )
    (comp (ref "D215")
      (value "WS2812B")
      (footprint "eagle-import:WS2812B")
      (libsource (lib "eagle-import") (part "WS2812B"))
    )
    (comp (ref "D216")
      (value "WS2812B")
      (footprint "eagle-import:WS2812B")
      (libsource (lib "eagle-import") (part "WS2812B"))
    )
    (comp (ref "D217")
      (value "WS2812B")
      (footprint "eagle-import:WS2812B")
      (libsource (lib "eagle-import") (part "WS2812B"))
    )
    (comp (ref "D218")
      (value "WS2812B")
      (footprint "eagle-import:WS2812B")
      (libsource (lib "eagle-import") (part "WS2812B"))
    )
    (comp (ref "D219")
      (value "WS2812B")
      (footprint "eagle-import:WS2812B")
      (libsource (lib "eagle-import") (part "WS2812B"))
    )
    (comp (ref "D220")
      (value "WS2812B")
      (footprint "eagle-import:WS2812B")
      (libsource (lib "eagle-import") (part "WS2812B"))
    )
    (comp (ref "D221")
      (value "WS2812B")
      (footprint "eagle-import:WS2812B")
      (libsource (lib "eagle-import") (part "WS2812B"))
    )
    (comp (ref "D222")
      (value "WS2812B")
      (footprint "eagle-import:WS2812B")
      (libsource (lib "eagle-import") (part "WS2812B"))
    )
    (comp (ref "D223")
      (value "WS2812B")
      (footprint "eagle-import:WS2812B")
      (libsource (lib "eagle-import") (part "WS2812B"))
    )
    (comp (ref "D224")
      (value "WS2812B")
      (footprint "eagle-import:WS2812B")
      (libsource (lib "eagle-import") (part "WS2812B"))
    )
    (comp (ref "D225")
      (value "WS2812B")
      (footprint "eagle-import:WS2812B")
      (libsource (lib "eagle-import") (part "WS2812B"))
    )
  )
  (nets
    (net (code "1") (name "3.3V") (class "Default")
      (node (ref "B2") (pin "36") (pinfunction "3V3_36") (pintype "bidirectional"))
      (node (ref "B2") (pin "5") (pinfunction "3V3_5") (pintype "bidirectional"))
      (node (ref "R41") (pin "1") (pinfunction "1_1") (pintype "passive"))
      (node (ref "R42") (pin "2") (pinfunction "2_2") (pintype "passive"))
      (node (ref "R43") (pin "2") (pinfunction "2_2") (pintype "passive"))
      (node (ref "R44") (pin "2") (pinfunction "2_2") (pintype "passive"))
      (node (ref "R45") (pin "2") (pinfunction "2_2") (pintype "passive"))
      (node (ref "R46") (pin "2") (pinfunction "2_2") (pintype "passive"))
      (node (ref "R48") (pin "2") (pinfunction "2_2") (pintype "passive"))
      (node (ref "R50") (pin "2") (pinfunction "2_2") (pintype "passive"))
      (node (ref "R52") (pin "2") (pinfunction "2_2") (pintype "passive"))
      (node (ref "R54") (pin "2") (pinfunction "2_2") (pintype "passive"))
      (node (ref "T1") (pin "1") (pinfunction "G_1") (pintype "passive"))
      (node (ref "T2") (pin "1") (pinfunction "G_1") (pintype "passive"))
      (node (ref "T3") (pin "1") (pinfunction "G_1") (pintype "passive"))
      (node (ref "T4") (pin "1") (pinfunction "G_1") (pintype "passive"))
      (node (ref "T5") (pin "1") (pinfunction "G_1") (pintype "passive"))
    )
    (net (code "2") (name "5V") (class "Default")
      (node (ref "B2") (pin "3") (pinfunction "VBAT_3") (pintype "bidirectional"))
      (node (ref "B2") (pin "38") (pinfunction "VBAT_38") (pintype "bidirectional"))
      (node (ref "B3") (pin "PWR+") (pinfunction "VCC_PWR+") (pintype "bidirectional"))
      (node (ref "C1") (pin "1") (pinfunction "1_1") (pintype "passive"))
      (node (ref "C10") (pin "1") (pinfunction "1_1") (pintype "passive"))
      (node (ref "C100") (pin "1") (pinfunction "1_1") (pintype "passive"))
      (node (ref "C101") (pin "1") (pinfunction "1_1") (pintype "passive"))
      (node (ref "C102") (pin "1") (pinfunction "1_1") (pintype "passive"))
      (node (ref "C103") (pin "1") (pinfunction "1_1") (pintype "passive"))
      (node (ref "C104") (pin "1") (pinfunction "1_1") (pintype "passive"))
      (node (ref "C107") (pin "1") (pinfunction "1_1") (pintype "passive"))
      (node (ref "C108") (pin "1") (pinfunction "1_1") (pintype "passive"))
      (node (ref "C109") (pin "1") (pinfunction "1_1") (pintype "passive"))
      (node (ref "C11") (pin "1") (pinfunction "1_1") (pintype "passive"))
      (node (ref "C110") (pin "1") (pinfunction "1_1") (pintype "passive"))
      (node (ref "C111") (pin "1") (pinfunction "1_1") (pintype "passive"))
      (node (ref "C112") (pin "1") (pinfunction "1_1") (pintype "passive"))
      (node (ref "C113") (pin "1") (pinfunction "1_1") (pintype "passive"))
      (node (ref "C114") (pin "1") (pinfunction "1_1") (pintype "passive"))
      (node (ref "C115") (pin "1") (pinfunction "1_1") (pintype "passive"))
      (node (ref "C116") (pin "1") (pinfunction "1_1") (pintype "passive"))
      (node (ref "C117") (pin "1") (pinfunction "1_1") (pintype "passive"))
      (node (ref "C118") (pin "1") (pinfunction "1_1") (pintype "passive"))
      (node (ref "C119") (pin "1") (pinfunction "1_1") (pintype "passive"))
      (node (ref "C12") (pin "1") (pinfunction "1_1") (pintype "passive"))
      (node (ref "C120") (pin "1") (pinfunction "1_1") (pintype "passive"))
      (node (ref "C121") (pin "1") (pinfunction "1_1") (pintype "passive"))
      (node (ref "C122") (pin "1") (pinfunction "1_1") (pintype "passive"))
      (node (ref "C123") (pin "1") (pinfunction "1_1") (pintype "passive"))
      (node (ref "C124") (pin "1") (pinfunction "1_1") (pintype "passive"))
      (node (ref "C125") (pin "1") (pinfunction "1_1") (pintype "passive"))
      (node (ref "C126") (pin "1") (pinfunction "1_1") (pintype "passive"))
      (node (ref "C127") (pin "1") (pinfunction "1_1") (pintype "passive"))
      (node (ref "C128") (pin "1") (pinfunction "1_1") (pintype "passive"))
      (node (ref "C129") (pin "1") (pinfunction "1_1") (pintype "passive"))
      (node (ref "C13") (pin "1") (pinfunction "1_1") (pintype "passive"))
      (node (ref "C130") (pin "1") (pinfunction "1_1") (pintype "passive"))
      (node (ref "C131") (pin "1") (pinfunction "1_1") (pintype "passive"))
      (node (ref "C132") (pin "1") (pinfunction "1_1") (pintype "passive"))
      (node (ref "C133") (pin "1") (pinfunction "1_1") (pintype "passive"))
      (node (ref "C134") (pin "1") (pinfunction "1_1") (pintype "passive"))
      (node (ref "C137") (pin "1") (pinfunction "1_1") (pintype "passive"))
      (node (ref "C138") (pin "1") (pinfunction "1_1") (pintype "passive"))
      (node (ref "C139") (pin "1") (pinfunction "1_1") (pintype "passive"))
      (node (ref "C14") (pin "1") (pinfunction "1_1") (pintype "passive"))
      (node (ref "C140") (pin "1") (pinfunction "1_1") (pintype "passive"))
      (node (ref "C141") (pin "1") (pinfunction "1_1") (pintype "passive"))
      (node (ref "C142") (pin "1") (pinfunction "1_1") (pintype "passive"))
      (node (ref "C143") (pin "1") (pinfunction "1_1") (pintype "passive"))
      (node (ref "C144") (pin "1") (pinfunction "1_1") (pintype "passive"))
      (node (ref "C145") (pin "1") (pinfunction "1_1") (pintype "passive"))
      (node (ref "C146") (pin "1") (pinfunction "1_1") (pintype "passive"))
      (node (ref "C147") (pin "1") (pinfunction "1_1") (pintype "passive"))
      (node (ref "C148") (pin "1") (pinfunction "1_1") (pintype "passive"))
      (node (ref "C149") (pin "1") (pinfunction "1_1") (pintype "passive"))
      (node (ref "C150") (pin "1") (pinfunction "1_1") (pintype "passive"))
      (node (ref "C151") (pin "1") (pinfunction "1_1") (pintype "passive"))
      (node (ref "C152") (pin "1") (pinfunction "1_1") (pintype "passive"))
      (node (ref "C153") (pin "1") (pinfunction "1_1") (pintype "passive"))
      (node (ref "C154") (pin "1") (pinfunction "1_1") (pintype "passive"))
      (node (ref "C155") (pin "1") (pinfunction "1_1") (pintype "passive"))
      (node (ref "C156") (pin "1") (pinfunction "1_1") (pintype "passive"))
      (node (ref "C157") (pin "1") (pinfunction "1_1") (pintype "passive"))
      (node (ref "C158") (pin "1") (pinfunction "1_1") (pintype "passive"))
      (node (ref "C159") (pin "1") (pinfunction "1_1") (pintype "passive"))
      (node (ref "C160") (pin "1") (pinfunction "1_1") (pintype "passive"))
      (node (ref "C161") (pin "1") (pinfunction "1_1") (pintype "passive"))
      (node (ref "C162") (pin "1") (pinfunction "1_1") (pintype "passive"))
      (node (ref "C163") (pin "1") (pinfunction "1_1") (pintype "passive"))
      (node (ref "C164") (pin "1") (pinfunction "1_1") (pintype "passive"))
      (node (ref "C167") (pin "1") (pinfunction "1_1") (pintype "passive"))
      (node (ref "C168") (pin "1") (pinfunction "1_1") (pintype "passive"))
      (node (ref "C169") (pin "1") (pinfunction "1_1") (pintype "passive"))
      (node (ref "C17") (pin "1") (pinfunction "1_1") (pintype "passive"))
      (node (ref "C170") (pin "1") (pinfunction "1_1") (pintype "passive"))
      (node (ref "C171") (pin "1") (pinfunction "1_1") (pintype "passive"))
      (node (ref "C172") (pin "1") (pinfunction "1_1") (pintype "passive"))
      (node (ref "C173") (pin "1") (pinfunction "1_1") (pintype "passive"))
      (node (ref "C174") (pin "1") (pinfunction "1_1") (pintype "passive"))
      (node (ref "C175") (pin "1") (pinfunction "1_1") (pintype "passive"))
      (node (ref "C176") (pin "1") (pinfunction "1_1") (pintype "passive"))
      (node (ref "C177") (pin "1") (pinfunction "1_1") (pintype "passive"))
      (node (ref "C178") (pin "1") (pinfunction "1_1") (pintype "passive"))
      (node (ref "C179") (pin "1") (pinfunction "1_1") (pintype "passive"))
      (node (ref "C18") (pin "1") (pinfunction "1_1") (pintype "passive"))
      (node (ref "C180") (pin "1") (pinfunction "1_1") (pintype "passive"))
      (node (ref "C181") (pin "1") (pinfunction "1_1") (pintype "passive"))
      (node (ref "C182") (pin "1") (pinfunction "1_1") (pintype "passive"))
      (node (ref "C183") (pin "1") (pinfunction "1_1") (pintype "passive"))
      (node (ref "C184") (pin "1") (pinfunction "1_1") (pintype "passive"))
      (node (ref "C185") (pin "1") (pinfunction "1_1") (pintype "passive"))
      (node (ref "C186") (pin "1") (pinfunction "1_1") (pintype "passive"))
      (node (ref "C187") (pin "1") (pinfunction "1_1") (pintype "passive"))
      (node (ref "C188") (pin "1") (pinfunction "1_1") (pintype "passive"))
      (node (ref "C189") (pin "1") (pinfunction "1_1") (pintype "passive"))
      (node (ref "C19") (pin "1") (pinfunction "1_1") (pintype "passive"))
      (node (ref "C190") (pin "1") (pinfunction "1_1") (pintype "passive"))
      (node (ref "C191") (pin "1") (pinfunction "1_1") (pintype "passive"))
      (node (ref "C192") (pin "1") (pinfunction "1_1") (pintype "passive"))
      (node (ref "C193") (pin "1") (pinfunction "1_1") (pintype "passive"))
      (node (ref "C194") (pin "1") (pinfunction "1_1") (pintype "passive"))
      (node (ref "C197") (pin "1") (pinfunction "1_1") (pintype "passive"))
      (node (ref "C198") (pin "1") (pinfunction "1_1") (pintype "passive"))
      (node (ref "C199") (pin "1") (pinfunction "1_1") (pintype "passive"))
      (node (ref "C2") (pin "1") (pinfunction "1_1") (pintype "passive"))
      (node (ref "C20") (pin "1") (pinfunction "1_1") (pintype "passive"))
      (node (ref "C200") (pin "1") (pinfunction "1_1") (pintype "passive"))
      (node (ref "C201") (pin "1") (pinfunction "1_1") (pintype "passive"))
      (node (ref "C202") (pin "1") (pinfunction "1_1") (pintype "passive"))
      (node (ref "C203") (pin "1") (pinfunction "1_1") (pintype "passive"))
      (node (ref "C204") (pin "1") (pinfunction "1_1") (pintype "passive"))
      (node (ref "C205") (pin "1") (pinfunction "1_1") (pintype "passive"))
      (node (ref "C206") (pin "1") (pinfunction "1_1") (pintype "passive"))
      (node (ref "C207") (pin "1") (pinfunction "1_1") (pintype "passive"))
      (node (ref "C208") (pin "1") (pinfunction "1_1") (pintype "passive"))
      (node (ref "C209") (pin "1") (pinfunction "1_1") (pintype "passive"))
      (node (ref "C21") (pin "1") (pinfunction "1_1") (pintype "passive"))
      (node (ref "C210") (pin "1") (pinfunction "1_1") (pintype "passive"))
      (node (ref "C211") (pin "1") (pinfunction "1_1") (pintype "passive"))
      (node (ref "C212") (pin "1") (pinfunction "1_1") (pintype "passive"))
      (node (ref "C213") (pin "1") (pinfunction "1_1") (pintype "passive"))
      (node (ref "C214") (pin "1") (pinfunction "1_1") (pintype "passive"))
      (node (ref "C215") (pin "1") (pinfunction "1_1") (pintype "passive"))
      (node (ref "C216") (pin "1") (pinfunction "1_1") (pintype "passive"))
      (node (ref "C217") (pin "1") (pinfunction "1_1") (pintype "passive"))
      (node (ref "C218") (pin "1") (pinfunction "1_1") (pintype "passive"))
      (node (ref "C219") (pin "1") (pinfunction "1_1") (pintype "passive"))
      (node (ref "C22") (pin "1") (pinfunction "1_1") (pintype "passive"))
      (node (ref "C220") (pin "1") (pinfunction "1_1") (pintype "passive"))
      (node (ref "C221") (pin "1") (pinfunction "1_1") (pintype "passive"))
      (node (ref "C222") (pin "1") (pinfunction "1_1") (pintype "passive"))
      (node (ref "C223") (pin "1") (pinfunction "1_1") (pintype "passive"))
      (node (ref "C224") (pin "1") (pinfunction "1_1") (pintype "passive"))
      (node (ref "C226") (pin "1") (pinfunction "1_1") (pintype "passive"))
      (node (ref "C229") (pin "1") (pinfunction "1_1") (pintype "passive"))
      (node (ref "C23") (pin "1") (pinfunction "1_1") (pintype "passive"))
      (node (ref "C24") (pin "1") (pinfunction "1_1") (pintype "passive"))
      (node (ref "C25") (pin "1") (pinfunction "1_1") (pintype "passive"))
      (node (ref "C26") (pin "1") (pinfunction "1_1") (pintype "passive"))
      (node (ref "C27") (pin "1") (pinfunction "1_1") (pintype "passive"))
      (node (ref "C28") (pin "1") (pinfunction "1_1") (pintype "passive"))
      (node (ref "C29") (pin "1") (pinfunction "1_1") (pintype "passive"))
      (node (ref "C3") (pin "1") (pinfunction "1_1") (pintype "passive"))
      (node (ref "C30") (pin "1") (pinfunction "1_1") (pintype "passive"))
      (node (ref "C31") (pin "1") (pinfunction "1_1") (pintype "passive"))
      (node (ref "C32") (pin "1") (pinfunction "1_1") (pintype "passive"))
      (node (ref "C33") (pin "1") (pinfunction "1_1") (pintype "passive"))
      (node (ref "C34") (pin "1") (pinfunction "1_1") (pintype "passive"))
      (node (ref "C35") (pin "1") (pinfunction "1_1") (pintype "passive"))
      (node (ref "C36") (pin "1") (pinfunction "1_1") (pintype "passive"))
      (node (ref "C37") (pin "1") (pinfunction "1_1") (pintype "passive"))
      (node (ref "C38") (pin "1") (pinfunction "1_1") (pintype "passive"))
      (node (ref "C39") (pin "1") (pinfunction "1_1") (pintype "passive"))
      (node (ref "C4") (pin "1") (pinfunction "1_1") (pintype "passive"))
      (node (ref "C40") (pin "1") (pinfunction "1_1") (pintype "passive"))
      (node (ref "C41") (pin "1") (pinfunction "1_1") (pintype "passive"))
      (node (ref "C42") (pin "1") (pinfunction "1_1") (pintype "passive"))
      (node (ref "C43") (pin "1") (pinfunction "1_1") (pintype "passive"))
      (node (ref "C44") (pin "1") (pinfunction "1_1") (pintype "passive"))
      (node (ref "C47") (pin "1") (pinfunction "1_1") (pintype "passive"))
      (node (ref "C48") (pin "1") (pinfunction "1_1") (pintype "passive"))
      (node (ref "C49") (pin "1") (pinfunction "1_1") (pintype "passive"))
      (node (ref "C5") (pin "1") (pinfunction "1_1") (pintype "passive"))
      (node (ref "C50") (pin "1") (pinfunction "1_1") (pintype "passive"))
      (node (ref "C51") (pin "1") (pinfunction "1_1") (pintype "passive"))
      (node (ref "C52") (pin "1") (pinfunction "1_1") (pintype "passive"))
      (node (ref "C53") (pin "1") (pinfunction "1_1") (pintype "passive"))
      (node (ref "C54") (pin "1") (pinfunction "1_1") (pintype "passive"))
      (node (ref "C55") (pin "1") (pinfunction "1_1") (pintype "passive"))
      (node (ref "C56") (pin "1") (pinfunction "1_1") (pintype "passive"))
      (node (ref "C57") (pin "1") (pinfunction "1_1") (pintype "passive"))
      (node (ref "C58") (pin "1") (pinfunction "1_1") (pintype "passive"))
      (node (ref "C59") (pin "1") (pinfunction "1_1") (pintype "passive"))
      (node (ref "C6") (pin "1") (pinfunction "1_1") (pintype "passive"))
      (node (ref "C60") (pin "1") (pinfunction "1_1") (pintype "passive"))
      (node (ref "C61") (pin "1") (pinfunction "1_1") (pintype "passive"))
      (node (ref "C62") (pin "1") (pinfunction "1_1") (pintype "passive"))
      (node (ref "C63") (pin "1") (pinfunction "1_1") (pintype "passive"))
      (node (ref "C64") (pin "1") (pinfunction "1_1") (pintype "passive"))
      (node (ref "C65") (pin "1") (pinfunction "1_1") (pintype "passive"))
      (node (ref "C66") (pin "1") (pinfunction "1_1") (pintype "passive"))
      (node (ref "C67") (pin "1") (pinfunction "1_1") (pintype "passive"))
      (node (ref "C68") (pin "1") (pinfunction "1_1") (pintype "passive"))
      (node (ref "C69") (pin "1") (pinfunction "1_1") (pintype "passive"))
      (node (ref "C7") (pin "1") (pinfunction "1_1") (pintype "passive"))
      (node (ref "C70") (pin "1") (pinfunction "1_1") (pintype "passive"))
      (node (ref "C71") (pin "1") (pinfunction "1_1") (pintype "passive"))
      (node (ref "C72") (pin "1") (pinfunction "1_1") (pintype "passive"))
      (node (ref "C73") (pin "1") (pinfunction "1_1") (pintype "passive"))
      (node (ref "C74") (pin "1") (pinfunction "1_1") (pintype "passive"))
      (node (ref "C77") (pin "1") (pinfunction "1_1") (pintype "passive"))
      (node (ref "C78") (pin "1") (pinfunction "1_1") (pintype "passive"))
      (node (ref "C79") (pin "1") (pinfunction "1_1") (pintype "passive"))
      (node (ref "C8") (pin "1") (pinfunction "1_1") (pintype "passive"))
      (node (ref "C80") (pin "1") (pinfunction "1_1") (pintype "passive"))
      (node (ref "C81") (pin "1") (pinfunction "1_1") (pintype "passive"))
      (node (ref "C82") (pin "1") (pinfunction "1_1") (pintype "passive"))
      (node (ref "C83") (pin "1") (pinfunction "1_1") (pintype "passive"))
      (node (ref "C84") (pin "1") (pinfunction "1_1") (pintype "passive"))
      (node (ref "C85") (pin "1") (pinfunction "1_1") (pintype "passive"))
      (node (ref "C86") (pin "1") (pinfunction "1_1") (pintype "passive"))
      (node (ref "C87") (pin "1") (pinfunction "1_1") (pintype "passive"))
      (node (ref "C88") (pin "1") (pinfunction "1_1") (pintype "passive"))
      (node (ref "C89") (pin "1") (pinfunction "1_1") (pintype "passive"))
      (node (ref "C9") (pin "1") (pinfunction "1_1") (pintype "passive"))
      (node (ref "C90") (pin "1") (pinfunction "1_1") (pintype "passive"))
      (node (ref "C91") (pin "1") (pinfunction "1_1") (pintype "passive"))
      (node (ref "C92") (pin "1") (pinfunction "1_1") (pintype "passive"))
      (node (ref "C93") (pin "1") (pinfunction "1_1") (pintype "passive"))
      (node (ref "C94") (pin "1") (pinfunction "1_1") (pintype "passive"))
      (node (ref "C95") (pin "1") (pinfunction "1_1") (pintype "passive"))
      (node (ref "C96") (pin "1") (pinfunction "1_1") (pintype "passive"))
      (node (ref "C97") (pin "1") (pinfunction "1_1") (pintype "passive"))
      (node (ref "C98") (pin "1") (pinfunction "1_1") (pintype "passive"))
      (node (ref "C99") (pin "1") (pinfunction "1_1") (pintype "passive"))
      (node (ref "D1") (pin "3") (pinfunction "VSS_3") (pintype "bidirectional"))
      (node (ref "D10") (pin "3") (pinfunction "VSS_3") (pintype "bidirectional"))
      (node (ref "D100") (pin "3") (pinfunction "VSS_3") (pintype "bidirectional"))
      (node (ref "D101") (pin "3") (pinfunction "VSS_3") (pintype "bidirectional"))
      (node (ref "D102") (pin "3") (pinfunction "VSS_3") (pintype "bidirectional"))
      (node (ref "D103") (pin "3") (pinfunction "VSS_3") (pintype "bidirectional"))
      (node (ref "D104") (pin "3") (pinfunction "VSS_3") (pintype "bidirectional"))
      (node (ref "D105") (pin "3") (pinfunction "VSS_3") (pintype "bidirectional"))
      (node (ref "D106") (pin "3") (pinfunction "VSS_3") (pintype "bidirectional"))
      (node (ref "D107") (pin "3") (pinfunction "VSS_3") (pintype "bidirectional"))
      (node (ref "D108") (pin "3") (pinfunction "VSS_3") (pintype "bidirectional"))
      (node (ref "D109") (pin "3") (pinfunction "VSS_3") (pintype "bidirectional"))
      (node (ref "D11") (pin "3") (pinfunction "VSS_3") (pintype "bidirectional"))
      (node (ref "D110") (pin "3") (pinfunction "VSS_3") (pintype "bidirectional"))
      (node (ref "D111") (pin "3") (pinfunction "VSS_3") (pintype "bidirectional"))
      (node (ref "D112") (pin "3") (pinfunction "VSS_3") (pintype "bidirectional"))
      (node (ref "D113") (pin "3") (pinfunction "VSS_3") (pintype "bidirectional"))
      (node (ref "D114") (pin "3") (pinfunction "VSS_3") (pintype "bidirectional"))
      (node (ref "D115") (pin "3") (pinfunction "VSS_3") (pintype "bidirectional"))
      (node (ref "D116") (pin "3") (pinfunction "VSS_3") (pintype "bidirectional"))
      (node (ref "D117") (pin "3") (pinfunction "VSS_3") (pintype "bidirectional"))
      (node (ref "D118") (pin "3") (pinfunction "VSS_3") (pintype "bidirectional"))
      (node (ref "D119") (pin "3") (pinfunction "VSS_3") (pintype "bidirectional"))
      (node (ref "D12") (pin "3") (pinfunction "VSS_3") (pintype "bidirectional"))
      (node (ref "D120") (pin "3") (pinfunction "VSS_3") (pintype "bidirectional"))
      (node (ref "D121") (pin "3") (pinfunction "VSS_3") (pintype "bidirectional"))
      (node (ref "D122") (pin "3") (pinfunction "VSS_3") (pintype "bidirectional"))
      (node (ref "D123") (pin "3") (pinfunction "VSS_3") (pintype "bidirectional"))
      (node (ref "D124") (pin "3") (pinfunction "VSS_3") (pintype "bidirectional"))
      (node (ref "D125") (pin "3") (pinfunction "VSS_3") (pintype "bidirectional"))
      (node (ref "D126") (pin "3") (pinfunction "VSS_3") (pintype "bidirectional"))
      (node (ref "D127") (pin "3") (pinfunction "VSS_3") (pintype "bidirectional"))
      (node (ref "D128") (pin "3") (pinfunction "VSS_3") (pintype "bidirectional"))
      (node (ref "D129") (pin "3") (pinfunction "VSS_3") (pintype "bidirectional"))
      (node (ref "D13") (pin "3") (pinfunction "VSS_3") (pintype "bidirectional"))
      (node (ref "D130") (pin "3") (pinfunction "VSS_3") (pintype "bidirectional"))
      (node (ref "D131") (pin "3") (pinfunction "VSS_3") (pintype "bidirectional"))
      (node (ref "D132") (pin "3") (pinfunction "VSS_3") (pintype "bidirectional"))
      (node (ref "D133") (pin "3") (pinfunction "VSS_3") (pintype "bidirectional"))
      (node (ref "D134") (pin "3") (pinfunction "VSS_3") (pintype "bidirectional"))
      (node (ref "D135") (pin "3") (pinfunction "VSS_3") (pintype "bidirectional"))
      (node (ref "D136") (pin "3") (pinfunction "VSS_3") (pintype "bidirectional"))
      (node (ref "D137") (pin "3") (pinfunction "VSS_3") (pintype "bidirectional"))
      (node (ref "D138") (pin "3") (pinfunction "VSS_3") (pintype "bidirectional"))
      (node (ref "D139") (pin "3") (pinfunction "VSS_3") (pintype "bidirectional"))
      (node (ref "D14") (pin "3") (pinfunction "VSS_3") (pintype "bidirectional"))
      (node (ref "D140") (pin "3") (pinfunction "VSS_3") (pintype "bidirectional"))
      (node (ref "D141") (pin "3") (pinfunction "VSS_3") (pintype "bidirectional"))
      (node (ref "D142") (pin "3") (pinfunction "VSS_3") (pintype "bidirectional"))
      (node (ref "D143") (pin "3") (pinfunction "VSS_3") (pintype "bidirectional"))
      (node (ref "D144") (pin "3") (pinfunction "VSS_3") (pintype "bidirectional"))
      (node (ref "D145") (pin "3") (pinfunction "VSS_3") (pintype "bidirectional"))
      (node (ref "D146") (pin "3") (pinfunction "VSS_3") (pintype "bidirectional"))
      (node (ref "D147") (pin "3") (pinfunction "VSS_3") (pintype "bidirectional"))
      (node (ref "D148") (pin "3") (pinfunction "VSS_3") (pintype "bidirectional"))
      (node (ref "D149") (pin "3") (pinfunction "VSS_3") (pintype "bidirectional"))
      (node (ref "D15") (pin "3") (pinfunction "VSS_3") (pintype "bidirectional"))
      (node (ref "D150") (pin "3") (pinfunction "VSS_3") (pintype "bidirectional"))
      (node (ref "D151") (pin "3") (pinfunction "VSS_3") (pintype "bidirectional"))
      (node (ref "D152") (pin "3") (pinfunction "VSS_3") (pintype "bidirectional"))
      (node (ref "D153") (pin "3") (pinfunction "VSS_3") (pintype "bidirectional"))
      (node (ref "D154") (pin "3") (pinfunction "VSS_3") (pintype "bidirectional"))
      (node (ref "D155") (pin "3") (pinfunction "VSS_3") (pintype "bidirectional"))
      (node (ref "D156") (pin "3") (pinfunction "VSS_3") (pintype "bidirectional"))
      (node (ref "D157") (pin "3") (pinfunction "VSS_3") (pintype "bidirectional"))
      (node (ref "D158") (pin "3") (pinfunction "VSS_3") (pintype "bidirectional"))
      (node (ref "D159") (pin "3") (pinfunction "VSS_3") (pintype "bidirectional"))
      (node (ref "D16") (pin "3") (pinfunction "VSS_3") (pintype "bidirectional"))
      (node (ref "D160") (pin "3") (pinfunction "VSS_3") (pintype "bidirectional"))
      (node (ref "D161") (pin "3") (pinfunction "VSS_3") (pintype "bidirectional"))
      (node (ref "D162") (pin "3") (pinfunction "VSS_3") (pintype "bidirectional"))
      (node (ref "D163") (pin "3") (pinfunction "VSS_3") (pintype "bidirectional"))
      (node (ref "D164") (pin "3") (pinfunction "VSS_3") (pintype "bidirectional"))
      (node (ref "D165") (pin "3") (pinfunction "VSS_3") (pintype "bidirectional"))
      (node (ref "D166") (pin "3") (pinfunction "VSS_3") (pintype "bidirectional"))
      (node (ref "D167") (pin "3") (pinfunction "VSS_3") (pintype "bidirectional"))
      (node (ref "D168") (pin "3") (pinfunction "VSS_3") (pintype "bidirectional"))
      (node (ref "D169") (pin "3") (pinfunction "VSS_3") (pintype "bidirectional"))
      (node (ref "D17") (pin "3") (pinfunction "VSS_3") (pintype "bidirectional"))
      (node (ref "D170") (pin "3") (pinfunction "VSS_3") (pintype "bidirectional"))
      (node (ref "D171") (pin "3") (pinfunction "VSS_3") (pintype "bidirectional"))
      (node (ref "D172") (pin "3") (pinfunction "VSS_3") (pintype "bidirectional"))
      (node (ref "D173") (pin "3") (pinfunction "VSS_3") (pintype "bidirectional"))
      (node (ref "D174") (pin "3") (pinfunction "VSS_3") (pintype "bidirectional"))
      (node (ref "D175") (pin "3") (pinfunction "VSS_3") (pintype "bidirectional"))
      (node (ref "D176") (pin "3") (pinfunction "VSS_3") (pintype "bidirectional"))
      (node (ref "D177") (pin "3") (pinfunction "VSS_3") (pintype "bidirectional"))
      (node (ref "D178") (pin "3") (pinfunction "VSS_3") (pintype "bidirectional"))
      (node (ref "D179") (pin "3") (pinfunction "VSS_3") (pintype "bidirectional"))
      (node (ref "D18") (pin "3") (pinfunction "VSS_3") (pintype "bidirectional"))
      (node (ref "D180") (pin "3") (pinfunction "VSS_3") (pintype "bidirectional"))
      (node (ref "D181") (pin "3") (pinfunction "VSS_3") (pintype "bidirectional"))
      (node (ref "D182") (pin "3") (pinfunction "VSS_3") (pintype "bidirectional"))
      (node (ref "D183") (pin "3") (pinfunction "VSS_3") (pintype "bidirectional"))
      (node (ref "D184") (pin "3") (pinfunction "VSS_3") (pintype "bidirectional"))
      (node (ref "D185") (pin "3") (pinfunction "VSS_3") (pintype "bidirectional"))
      (node (ref "D186") (pin "3") (pinfunction "VSS_3") (pintype "bidirectional"))
      (node (ref "D187") (pin "3") (pinfunction "VSS_3") (pintype "bidirectional"))
      (node (ref "D188") (pin "3") (pinfunction "VSS_3") (pintype "bidirectional"))
      (node (ref "D189") (pin "3") (pinfunction "VSS_3") (pintype "bidirectional"))
      (node (ref "D19") (pin "3") (pinfunction "VSS_3") (pintype "bidirectional"))
      (node (ref "D190") (pin "3") (pinfunction "VSS_3") (pintype "bidirectional"))
      (node (ref "D191") (pin "3") (pinfunction "VSS_3") (pintype "bidirectional"))
      (node (ref "D192") (pin "3") (pinfunction "VSS_3") (pintype "bidirectional"))
      (node (ref "D193") (pin "3") (pinfunction "VSS_3") (pintype "bidirectional"))
      (node (ref "D194") (pin "3") (pinfunction "VSS_3") (pintype "bidirectional"))
      (node (ref "D195") (pin "3") (pinfunction "VSS_3") (pintype "bidirectional"))
      (node (ref "D196") (pin "3") (pinfunction "VSS_3") (pintype "bidirectional"))
      (node (ref "D197") (pin "3") (pinfunction "VSS_3") (pintype "bidirectional"))
      (node (ref "D198") (pin "3") (pinfunction "VSS_3") (pintype "bidirectional"))
      (node (ref "D199") (pin "3") (pinfunction "VSS_3") (pintype "bidirectional"))
      (node (ref "D2") (pin "3") (pinfunction "VSS_3") (pintype "bidirectional"))
      (node (ref "D20") (pin "3") (pinfunction "VSS_3") (pintype "bidirectional"))
      (node (ref "D200") (pin "3") (pinfunction "VSS_3") (pintype "bidirectional"))
      (node (ref "D201") (pin "3") (pinfunction "VSS_3") (pintype "bidirectional"))
      (node (ref "D202") (pin "3") (pinfunction "VSS_3") (pintype "bidirectional"))
      (node (ref "D203") (pin "3") (pinfunction "VSS_3") (pintype "bidirectional"))
      (node (ref "D204") (pin "3") (pinfunction "VSS_3") (pintype "bidirectional"))
      (node (ref "D205") (pin "3") (pinfunction "VSS_3") (pintype "bidirectional"))
      (node (ref "D206") (pin "3") (pinfunction "VSS_3") (pintype "bidirectional"))
      (node (ref "D207") (pin "3") (pinfunction "VSS_3") (pintype "bidirectional"))
      (node (ref "D208") (pin "3") (pinfunction "VSS_3") (pintype "bidirectional"))
      (node (ref "D209") (pin "3") (pinfunction "VSS_3") (pintype "bidirectional"))
      (node (ref "D21") (pin "3") (pinfunction "VSS_3") (pintype "bidirectional"))
      (node (ref "D210") (pin "3") (pinfunction "VSS_3") (pintype "bidirectional"))
      (node (ref "D211") (pin "3") (pinfunction "VSS_3") (pintype "bidirectional"))
      (node (ref "D212") (pin "3") (pinfunction "VSS_3") (pintype "bidirectional"))
      (node (ref "D213") (pin "3") (pinfunction "VSS_3") (pintype "bidirectional"))
      (node (ref "D214") (pin "3") (pinfunction "VSS_3") (pintype "bidirectional"))
      (node (ref "D215") (pin "3") (pinfunction "VSS_3") (pintype "bidirectional"))
      (node (ref "D216") (pin "3") (pinfunction "VSS_3") (pintype "bidirectional"))
      (node (ref "D217") (pin "3") (pinfunction "VSS_3") (pintype "bidirectional"))
      (node (ref "D218") (pin "3") (pinfunction "VSS_3") (pintype "bidirectional"))
      (node (ref "D219") (pin "3") (pinfunction "VSS_3") (pintype "bidirectional"))
      (node (ref "D22") (pin "3") (pinfunction "VSS_3") (pintype "bidirectional"))
      (node (ref "D220") (pin "3") (pinfunction "VSS_3") (pintype "bidirectional"))
      (node (ref "D221") (pin "3") (pinfunction "VSS_3") (pintype "bidirectional"))
      (node (ref "D222") (pin "3") (pinfunction "VSS_3") (pintype "bidirectional"))
      (node (ref "D223") (pin "3") (pinfunction "VSS_3") (pintype "bidirectional"))
      (node (ref "D224") (pin "3") (pinfunction "VSS_3") (pintype "bidirectional"))
      (node (ref "D225") (pin "3") (pinfunction "VSS_3") (pintype "bidirectional"))
      (node (ref "D23") (pin "3") (pinfunction "VSS_3") (pintype "bidirectional"))
      (node (ref "D24") (pin "3") (pinfunction "VSS_3") (pintype "bidirectional"))
      (node (ref "D25") (pin "3") (pinfunction "VSS_3") (pintype "bidirectional"))
      (node (ref "D26") (pin "3") (pinfunction "VSS_3") (pintype "bidirectional"))
      (node (ref "D27") (pin "3") (pinfunction "VSS_3") (pintype "bidirectional"))
      (node (ref "D28") (pin "3") (pinfunction "VSS_3") (pintype "bidirectional"))
      (node (ref "D29") (pin "3") (pinfunction "VSS_3") (pintype "bidirectional"))
      (node (ref "D3") (pin "3") (pinfunction "VSS_3") (pintype "bidirectional"))
      (node (ref "D30") (pin "3") (pinfunction "VSS_3") (pintype "bidirectional"))
      (node (ref "D31") (pin "3") (pinfunction "VSS_3") (pintype "bidirectional"))
      (node (ref "D32") (pin "3") (pinfunction "VSS_3") (pintype "bidirectional"))
      (node (ref "D33") (pin "3") (pinfunction "VSS_3") (pintype "bidirectional"))
      (node (ref "D34") (pin "3") (pinfunction "VSS_3") (pintype "bidirectional"))
      (node (ref "D35") (pin "3") (pinfunction "VSS_3") (pintype "bidirectional"))
      (node (ref "D36") (pin "3") (pinfunction "VSS_3") (pintype "bidirectional"))
      (node (ref "D37") (pin "3") (pinfunction "VSS_3") (pintype "bidirectional"))
      (node (ref "D38") (pin "3") (pinfunction "VSS_3") (pintype "bidirectional"))
      (node (ref "D39") (pin "3") (pinfunction "VSS_3") (pintype "bidirectional"))
      (node (ref "D4") (pin "3") (pinfunction "VSS_3") (pintype "bidirectional"))
      (node (ref "D40") (pin "3") (pinfunction "VSS_3") (pintype "bidirectional"))
      (node (ref "D41") (pin "3") (pinfunction "VSS_3") (pintype "bidirectional"))
      (node (ref "D42") (pin "3") (pinfunction "VSS_3") (pintype "bidirectional"))
      (node (ref "D43") (pin "3") (pinfunction "VSS_3") (pintype "bidirectional"))
      (node (ref "D44") (pin "3") (pinfunction "VSS_3") (pintype "bidirectional"))
      (node (ref "D45") (pin "3") (pinfunction "VSS_3") (pintype "bidirectional"))
      (node (ref "D46") (pin "3") (pinfunction "VSS_3") (pintype "bidirectional"))
      (node (ref "D47") (pin "3") (pinfunction "VSS_3") (pintype "bidirectional"))
      (node (ref "D48") (pin "3") (pinfunction "VSS_3") (pintype "bidirectional"))
      (node (ref "D49") (pin "3") (pinfunction "VSS_3") (pintype "bidirectional"))
      (node (ref "D5") (pin "3") (pinfunction "VSS_3") (pintype "bidirectional"))
      (node (ref "D50") (pin "3") (pinfunction "VSS_3") (pintype "bidirectional"))
      (node (ref "D51") (pin "3") (pinfunction "VSS_3") (pintype "bidirectional"))
      (node (ref "D52") (pin "3") (pinfunction "VSS_3") (pintype "bidirectional"))
      (node (ref "D53") (pin "3") (pinfunction "VSS_3") (pintype "bidirectional"))
      (node (ref "D54") (pin "3") (pinfunction "VSS_3") (pintype "bidirectional"))
      (node (ref "D55") (pin "3") (pinfunction "VSS_3") (pintype "bidirectional"))
      (node (ref "D56") (pin "3") (pinfunction "VSS_3") (pintype "bidirectional"))
      (node (ref "D57") (pin "3") (pinfunction "VSS_3") (pintype "bidirectional"))
      (node (ref "D58") (pin "3") (pinfunction "VSS_3") (pintype "bidirectional"))
      (node (ref "D59") (pin "3") (pinfunction "VSS_3") (pintype "bidirectional"))
      (node (ref "D6") (pin "3") (pinfunction "VSS_3") (pintype "bidirectional"))
      (node (ref "D60") (pin "3") (pinfunction "VSS_3") (pintype "bidirectional"))
      (node (ref "D61") (pin "3") (pinfunction "VSS_3") (pintype "bidirectional"))
      (node (ref "D62") (pin "3") (pinfunction "VSS_3") (pintype "bidirectional"))
      (node (ref "D63") (pin "3") (pinfunction "VSS_3") (pintype "bidirectional"))
      (node (ref "D64") (pin "3") (pinfunction "VSS_3") (pintype "bidirectional"))
      (node (ref "D65") (pin "3") (pinfunction "VSS_3") (pintype "bidirectional"))
      (node (ref "D66") (pin "3") (pinfunction "VSS_3") (pintype "bidirectional"))
      (node (ref "D67") (pin "3") (pinfunction "VSS_3") (pintype "bidirectional"))
      (node (ref "D68") (pin "3") (pinfunction "VSS_3") (pintype "bidirectional"))
      (node (ref "D69") (pin "3") (pinfunction "VSS_3") (pintype "bidirectional"))
      (node (ref "D7") (pin "3") (pinfunction "VSS_3") (pintype "bidirectional"))
      (node (ref "D70") (pin "3") (pinfunction "VSS_3") (pintype "bidirectional"))
      (node (ref "D71") (pin "3") (pinfunction "VSS_3") (pintype "bidirectional"))
      (node (ref "D72") (pin "3") (pinfunction "VSS_3") (pintype "bidirectional"))
      (node (ref "D73") (pin "3") (pinfunction "VSS_3") (pintype "bidirectional"))
      (node (ref "D74") (pin "3") (pinfunction "VSS_3") (pintype "bidirectional"))
      (node (ref "D75") (pin "3") (pinfunction "VSS_3") (pintype "bidirectional"))
      (node (ref "D76") (pin "3") (pinfunction "VSS_3") (pintype "bidirectional"))
      (node (ref "D77") (pin "3") (pinfunction "VSS_3") (pintype "bidirectional"))
      (node (ref "D78") (pin "3") (pinfunction "VSS_3") (pintype "bidirectional"))
      (node (ref "D79") (pin "3") (pinfunction "VSS_3") (pintype "bidirectional"))
      (node (ref "D8") (pin "3") (pinfunction "VSS_3") (pintype "bidirectional"))
      (node (ref "D80") (pin "3") (pinfunction "VSS_3") (pintype "bidirectional"))
      (node (ref "D81") (pin "3") (pinfunction "VSS_3") (pintype "bidirectional"))
      (node (ref "D82") (pin "3") (pinfunction "VSS_3") (pintype "bidirectional"))
      (node (ref "D83") (pin "3") (pinfunction "VSS_3") (pintype "bidirectional"))
      (node (ref "D84") (pin "3") (pinfunction "VSS_3") (pintype "bidirectional"))
      (node (ref "D85") (pin "3") (pinfunction "VSS_3") (pintype "bidirectional"))
      (node (ref "D86") (pin "3") (pinfunction "VSS_3") (pintype "bidirectional"))
      (node (ref "D87") (pin "3") (pinfunction "VSS_3") (pintype "bidirectional"))
      (node (ref "D88") (pin "3") (pinfunction "VSS_3") (pintype "bidirectional"))
      (node (ref "D89") (pin "3") (pinfunction "VSS_3") (pintype "bidirectional"))
      (node (ref "D9") (pin "3") (pinfunction "VSS_3") (pintype "bidirectional"))
      (node (ref "D90") (pin "3") (pinfunction "VSS_3") (pintype "bidirectional"))
      (node (ref "D91") (pin "3") (pinfunction "VSS_3") (pintype "bidirectional"))
      (node (ref "D92") (pin "3") (pinfunction "VSS_3") (pintype "bidirectional"))
      (node (ref "D93") (pin "3") (pinfunction "VSS_3") (pintype "bidirectional"))
      (node (ref "D94") (pin "3") (pinfunction "VSS_3") (pintype "bidirectional"))
      (node (ref "D95") (pin "3") (pinfunction "VSS_3") (pintype "bidirectional"))
      (node (ref "D96") (pin "3") (pinfunction "VSS_3") (pintype "bidirectional"))
      (node (ref "D97") (pin "3") (pinfunction "VSS_3") (pintype "bidirectional"))
      (node (ref "D98") (pin "3") (pinfunction "VSS_3") (pintype "bidirectional"))
      (node (ref "D99") (pin "3") (pinfunction "VSS_3") (pintype "bidirectional"))
      (node (ref "R49") (pin "2") (pinfunction "2_2") (pintype "passive"))
      (node (ref "R51") (pin "2") (pinfunction "2_2") (pintype "passive"))
      (node (ref "R53") (pin "2") (pinfunction "2_2") (pintype "passive"))
      (node (ref "R55") (pin "2") (pinfunction "2_2") (pintype "passive"))
      (node (ref "R56") (pin "2") (pinfunction "2_2") (pintype "passive"))
      (node (ref "U1") (pin "10") (pinfunction "SCL_10") (pintype "input"))
      (node (ref "U1") (pin "16") (pinfunction "VCC_16") (pintype "power_in"))
      (node (ref "U2") (pin "10") (pinfunction "SCL_10") (pintype "input"))
      (node (ref "U2") (pin "16") (pinfunction "VCC_16") (pintype "power_in"))
      (node (ref "U3") (pin "10") (pinfunction "SCL_10") (pintype "input"))
      (node (ref "U3") (pin "16") (pinfunction "VCC_16") (pintype "power_in"))
      (node (ref "U4") (pin "10") (pinfunction "SCL_10") (pintype "input"))
      (node (ref "U4") (pin "16") (pinfunction "VCC_16") (pintype "power_in"))
      (node (ref "U5") (pin "10") (pinfunction "SCL_10") (pintype "input"))
      (node (ref "U5") (pin "16") (pinfunction "VCC_16") (pintype "power_in"))
      (node (ref "U6") (pin "OUT") (pinfunction "OUT_OUT") (pintype "passive"))
    )
    (net (code "3") (name "DAC_IN") (class "Default")
      (node (ref "B3") (pin "IN+") (pinfunction "IN+_IN+") (pintype "bidirectional"))
      (node (ref "R56") (pin "1") (pinfunction "1_1") (pintype "passive"))
      (node (ref "T5") (pin "3") (pinfunction "D_3") (pintype "passive"))
    )
    (net (code "4") (name "DIS1_A") (class "Default")
      (node (ref "DISPLAY_1") (pin "7") (pinfunction "A_7") (pintype "bidirectional"))
      (node (ref "R8") (pin "2") (pinfunction "2_2") (pintype "passive"))
    )
    (net (code "5") (name "DIS1_B") (class "Default")
      (node (ref "DISPLAY_1") (pin "6") (pinfunction "B_6") (pintype "bidirectional"))
      (node (ref "R1") (pin "2") (pinfunction "2_2") (pintype "passive"))
    )
    (net (code "6") (name "DIS1_C") (class "Default")
      (node (ref "DISPLAY_1") (pin "9") (pinfunction "F_9") (pintype "bidirectional"))
      (node (ref "R2") (pin "2") (pinfunction "2_2") (pintype "passive"))
    )
    (net (code "7") (name "DIS1_D") (class "Default")
      (node (ref "DISPLAY_1") (pin "10") (pinfunction "G_10") (pintype "bidirectional"))
      (node (ref "R3") (pin "2") (pinfunction "2_2") (pintype "passive"))
    )
    (net (code "8") (name "DIS1_E") (class "Default")
      (node (ref "DISPLAY_1") (pin "1") (pinfunction "E_1") (pintype "bidirectional"))
      (node (ref "R4") (pin "2") (pinfunction "2_2") (pintype "passive"))
    )
    (net (code "9") (name "DIS1_F") (class "Default")
      (node (ref "DISPLAY_1") (pin "2") (pinfunction "D_2") (pintype "bidirectional"))
      (node (ref "R5") (pin "2") (pinfunction "2_2") (pintype "passive"))
    )
    (net (code "10") (name "DIS1_G") (class "Default")
      (node (ref "DISPLAY_1") (pin "4") (pinfunction "C_4") (pintype "bidirectional"))
      (node (ref "R6") (pin "2") (pinfunction "2_2") (pintype "passive"))
    )
    (net (code "11") (name "DIS1_H") (class "Default")
      (node (ref "DISPLAY_1") (pin "5") (pinfunction "DP_5") (pintype "bidirectional"))
      (node (ref "R7") (pin "2") (pinfunction "2_2") (pintype "passive"))
    )
    (net (code "12") (name "DIS2_A") (class "Default")
      (node (ref "DISPLAY_2") (pin "7") (pinfunction "A_7") (pintype "bidirectional"))
      (node (ref "R9") (pin "2") (pinfunction "2_2") (pintype "passive"))
    )
    (net (code "13") (name "DIS2_B") (class "Default")
      (node (ref "DISPLAY_2") (pin "6") (pinfunction "B_6") (pintype "bidirectional"))
      (node (ref "R10") (pin "2") (pinfunction "2_2") (pintype "passive"))
    )
    (net (code "14") (name "DIS2_C") (class "Default")
      (node (ref "DISPLAY_2") (pin "9") (pinfunction "F_9") (pintype "bidirectional"))
      (node (ref "R11") (pin "2") (pinfunction "2_2") (pintype "passive"))
    )
    (net (code "15") (name "DIS2_D") (class "Default")
      (node (ref "DISPLAY_2") (pin "10") (pinfunction "G_10") (pintype "bidirectional"))
      (node (ref "R12") (pin "2") (pinfunction "2_2") (pintype "passive"))
    )
    (net (code "16") (name "DIS2_E") (class "Default")
      (node (ref "DISPLAY_2") (pin "1") (pinfunction "E_1") (pintype "bidirectional"))
      (node (ref "R13") (pin "2") (pinfunction "2_2") (pintype "passive"))
    )
    (net (code "17") (name "DIS2_F") (class "Default")
      (node (ref "DISPLAY_2") (pin "2") (pinfunction "D_2") (pintype "bidirectional"))
      (node (ref "R14") (pin "2") (pinfunction "2_2") (pintype "passive"))
    )
    (net (code "18") (name "DIS2_G") (class "Default")
      (node (ref "DISPLAY_2") (pin "4") (pinfunction "C_4") (pintype "bidirectional"))
      (node (ref "R15") (pin "2") (pinfunction "2_2") (pintype "passive"))
    )
    (net (code "19") (name "DIS2_H") (class "Default")
      (node (ref "DISPLAY_2") (pin "5") (pinfunction "DP_5") (pintype "bidirectional"))
      (node (ref "R16") (pin "2") (pinfunction "2_2") (pintype "passive"))
    )
    (net (code "20") (name "DIS3_A") (class "Default")
      (node (ref "DISPLAY_3") (pin "7") (pinfunction "A_7") (pintype "bidirectional"))
      (node (ref "R17") (pin "2") (pinfunction "2_2") (pintype "passive"))
    )
    (net (code "21") (name "DIS3_B") (class "Default")
      (node (ref "DISPLAY_3") (pin "6") (pinfunction "B_6") (pintype "bidirectional"))
      (node (ref "R18") (pin "2") (pinfunction "2_2") (pintype "passive"))
    )
    (net (code "22") (name "DIS3_C") (class "Default")
      (node (ref "DISPLAY_3") (pin "9") (pinfunction "F_9") (pintype "bidirectional"))
      (node (ref "R19") (pin "2") (pinfunction "2_2") (pintype "passive"))
    )
    (net (code "23") (name "DIS3_D") (class "Default")
      (node (ref "DISPLAY_3") (pin "10") (pinfunction "G_10") (pintype "bidirectional"))
      (node (ref "R20") (pin "2") (pinfunction "2_2") (pintype "passive"))
    )
    (net (code "24") (name "DIS3_E") (class "Default")
      (node (ref "DISPLAY_3") (pin "1") (pinfunction "E_1") (pintype "bidirectional"))
      (node (ref "R21") (pin "2") (pinfunction "2_2") (pintype "passive"))
    )
    (net (code "25") (name "DIS3_F") (class "Default")
      (node (ref "DISPLAY_3") (pin "2") (pinfunction "D_2") (pintype "bidirectional"))
      (node (ref "R22") (pin "2") (pinfunction "2_2") (pintype "passive"))
    )
    (net (code "26") (name "DIS3_G") (class "Default")
      (node (ref "DISPLAY_3") (pin "4") (pinfunction "C_4") (pintype "bidirectional"))
      (node (ref "R23") (pin "2") (pinfunction "2_2") (pintype "passive"))
    )
    (net (code "27") (name "DIS3_H") (class "Default")
      (node (ref "DISPLAY_3") (pin "5") (pinfunction "DP_5") (pintype "bidirectional"))
      (node (ref "R24") (pin "2") (pinfunction "2_2") (pintype "passive"))
    )
    (net (code "28") (name "DIS4_A") (class "Default")
      (node (ref "DISPLAY_4") (pin "7") (pinfunction "A_7") (pintype "bidirectional"))
      (node (ref "R25") (pin "2") (pinfunction "2_2") (pintype "passive"))
    )
    (net (code "29") (name "DIS4_B") (class "Default")
      (node (ref "DISPLAY_4") (pin "6") (pinfunction "B_6") (pintype "bidirectional"))
      (node (ref "R26") (pin "2") (pinfunction "2_2") (pintype "passive"))
    )
    (net (code "30") (name "DIS4_C") (class "Default")
      (node (ref "DISPLAY_4") (pin "9") (pinfunction "F_9") (pintype "bidirectional"))
      (node (ref "R27") (pin "2") (pinfunction "2_2") (pintype "passive"))
    )
    (net (code "31") (name "DIS4_D") (class "Default")
      (node (ref "DISPLAY_4") (pin "10") (pinfunction "G_10") (pintype "bidirectional"))
      (node (ref "R28") (pin "2") (pinfunction "2_2") (pintype "passive"))
    )
    (net (code "32") (name "DIS4_E") (class "Default")
      (node (ref "DISPLAY_4") (pin "1") (pinfunction "E_1") (pintype "bidirectional"))
      (node (ref "R29") (pin "2") (pinfunction "2_2") (pintype "passive"))
    )
    (net (code "33") (name "DIS4_F") (class "Default")
      (node (ref "DISPLAY_4") (pin "2") (pinfunction "D_2") (pintype "bidirectional"))
      (node (ref "R30") (pin "2") (pinfunction "2_2") (pintype "passive"))
    )
    (net (code "34") (name "DIS4_G") (class "Default")
      (node (ref "DISPLAY_4") (pin "4") (pinfunction "C_4") (pintype "bidirectional"))
      (node (ref "R31") (pin "2") (pinfunction "2_2") (pintype "passive"))
    )
    (net (code "35") (name "DIS4_H") (class "Default")
      (node (ref "DISPLAY_4") (pin "5") (pinfunction "DP_5") (pintype "bidirectional"))
      (node (ref "R32") (pin "2") (pinfunction "2_2") (pintype "passive"))
    )
    (net (code "36") (name "DIS5_A") (class "Default")
      (node (ref "DISPLAY_5") (pin "7") (pinfunction "A_7") (pintype "bidirectional"))
      (node (ref "R33") (pin "2") (pinfunction "2_2") (pintype "passive"))
    )
    (net (code "37") (name "DIS5_B") (class "Default")
      (node (ref "DISPLAY_5") (pin "6") (pinfunction "B_6") (pintype "bidirectional"))
      (node (ref "R34") (pin "2") (pinfunction "2_2") (pintype "passive"))
    )
    (net (code "38") (name "DIS5_C") (class "Default")
      (node (ref "DISPLAY_5") (pin "9") (pinfunction "F_9") (pintype "bidirectional"))
      (node (ref "R35") (pin "2") (pinfunction "2_2") (pintype "passive"))
    )
    (net (code "39") (name "DIS5_D") (class "Default")
      (node (ref "DISPLAY_5") (pin "10") (pinfunction "G_10") (pintype "bidirectional"))
      (node (ref "R36") (pin "2") (pinfunction "2_2") (pintype "passive"))
    )
    (net (code "40") (name "DIS5_E") (class "Default")
      (node (ref "DISPLAY_5") (pin "1") (pinfunction "E_1") (pintype "bidirectional"))
      (node (ref "R37") (pin "2") (pinfunction "2_2") (pintype "passive"))
    )
    (net (code "41") (name "DIS5_F") (class "Default")
      (node (ref "DISPLAY_5") (pin "2") (pinfunction "D_2") (pintype "bidirectional"))
      (node (ref "R38") (pin "2") (pinfunction "2_2") (pintype "passive"))
    )
    (net (code "42") (name "DIS5_G") (class "Default")
      (node (ref "DISPLAY_5") (pin "4") (pinfunction "C_4") (pintype "bidirectional"))
      (node (ref "R39") (pin "2") (pinfunction "2_2") (pintype "passive"))
    )
    (net (code "43") (name "DIS5_H") (class "Default")
      (node (ref "DISPLAY_5") (pin "5") (pinfunction "DP_5") (pintype "bidirectional"))
      (node (ref "R40") (pin "2") (pinfunction "2_2") (pintype "passive"))
    )
    (net (code "44") (name "GND") (class "Default")
      (node (ref "B2") (pin "1") (pinfunction "GND_1") (pintype "bidirectional"))
      (node (ref "B2") (pin "21") (pinfunction "GND_21") (pintype "bidirectional"))
      (node (ref "B2") (pin "37") (pinfunction "GND_37") (pintype "bidirectional"))
      (node (ref "B2") (pin "4") (pinfunction "GND_4") (pintype "bidirectional"))
      (node (ref "B2") (pin "40") (pinfunction "GND_40") (pintype "bidirectional"))
      (node (ref "B3") (pin "IN-") (pinfunction "IN-_IN-") (pintype "bidirectional"))
      (node (ref "B3") (pin "PWR-") (pinfunction "GND_PWR-") (pintype "bidirectional"))
      (node (ref "BT2") (pin "GND@1") (pinfunction "-_GND@1") (pintype "power_in"))
      (node (ref "C1") (pin "2") (pinfunction "2_2") (pintype "passive"))
      (node (ref "C10") (pin "2") (pinfunction "2_2") (pintype "passive"))
      (node (ref "C100") (pin "2") (pinfunction "2_2") (pintype "passive"))
      (node (ref "C101") (pin "2") (pinfunction "2_2") (pintype "passive"))
      (node (ref "C102") (pin "2") (pinfunction "2_2") (pintype "passive"))
      (node (ref "C103") (pin "2") (pinfunction "2_2") (pintype "passive"))
      (node (ref "C104") (pin "2") (pinfunction "2_2") (pintype "passive"))
      (node (ref "C107") (pin "2") (pinfunction "2_2") (pintype "passive"))
      (node (ref "C108") (pin "2") (pinfunction "2_2") (pintype "passive"))
      (node (ref "C109") (pin "2") (pinfunction "2_2") (pintype "passive"))
      (node (ref "C11") (pin "2") (pinfunction "2_2") (pintype "passive"))
      (node (ref "C110") (pin "2") (pinfunction "2_2") (pintype "passive"))
      (node (ref "C111") (pin "2") (pinfunction "2_2") (pintype "passive"))
      (node (ref "C112") (pin "2") (pinfunction "2_2") (pintype "passive"))
      (node (ref "C113") (pin "2") (pinfunction "2_2") (pintype "passive"))
      (node (ref "C114") (pin "2") (pinfunction "2_2") (pintype "passive"))
      (node (ref "C115") (pin "2") (pinfunction "2_2") (pintype "passive"))
      (node (ref "C116") (pin "2") (pinfunction "2_2") (pintype "passive"))
      (node (ref "C117") (pin "2") (pinfunction "2_2") (pintype "passive"))
      (node (ref "C118") (pin "2") (pinfunction "2_2") (pintype "passive"))
      (node (ref "C119") (pin "2") (pinfunction "2_2") (pintype "passive"))
      (node (ref "C12") (pin "2") (pinfunction "2_2") (pintype "passive"))
      (node (ref "C120") (pin "2") (pinfunction "2_2") (pintype "passive"))
      (node (ref "C121") (pin "2") (pinfunction "2_2") (pintype "passive"))
      (node (ref "C122") (pin "2") (pinfunction "2_2") (pintype "passive"))
      (node (ref "C123") (pin "2") (pinfunction "2_2") (pintype "passive"))
      (node (ref "C124") (pin "2") (pinfunction "2_2") (pintype "passive"))
      (node (ref "C125") (pin "2") (pinfunction "2_2") (pintype "passive"))
      (node (ref "C126") (pin "2") (pinfunction "2_2") (pintype "passive"))
      (node (ref "C127") (pin "2") (pinfunction "2_2") (pintype "passive"))
      (node (ref "C128") (pin "2") (pinfunction "2_2") (pintype "passive"))
      (node (ref "C129") (pin "2") (pinfunction "2_2") (pintype "passive"))
      (node (ref "C13") (pin "2") (pinfunction "2_2") (pintype "passive"))
      (node (ref "C130") (pin "2") (pinfunction "2_2") (pintype "passive"))
      (node (ref "C131") (pin "2") (pinfunction "2_2") (pintype "passive"))
      (node (ref "C132") (pin "2") (pinfunction "2_2") (pintype "passive"))
      (node (ref "C133") (pin "2") (pinfunction "2_2") (pintype "passive"))
      (node (ref "C134") (pin "2") (pinfunction "2_2") (pintype "passive"))
      (node (ref "C137") (pin "2") (pinfunction "2_2") (pintype "passive"))
      (node (ref "C138") (pin "2") (pinfunction "2_2") (pintype "passive"))
      (node (ref "C139") (pin "2") (pinfunction "2_2") (pintype "passive"))
      (node (ref "C14") (pin "2") (pinfunction "2_2") (pintype "passive"))
      (node (ref "C140") (pin "2") (pinfunction "2_2") (pintype "passive"))
      (node (ref "C141") (pin "2") (pinfunction "2_2") (pintype "passive"))
      (node (ref "C142") (pin "2") (pinfunction "2_2") (pintype "passive"))
      (node (ref "C143") (pin "2") (pinfunction "2_2") (pintype "passive"))
      (node (ref "C144") (pin "2") (pinfunction "2_2") (pintype "passive"))
      (node (ref "C145") (pin "2") (pinfunction "2_2") (pintype "passive"))
      (node (ref "C146") (pin "2") (pinfunction "2_2") (pintype "passive"))
      (node (ref "C147") (pin "2") (pinfunction "2_2") (pintype "passive"))
      (node (ref "C148") (pin "2") (pinfunction "2_2") (pintype "passive"))
      (node (ref "C149") (pin "2") (pinfunction "2_2") (pintype "passive"))
      (node (ref "C150") (pin "2") (pinfunction "2_2") (pintype "passive"))
      (node (ref "C151") (pin "2") (pinfunction "2_2") (pintype "passive"))
      (node (ref "C152") (pin "2") (pinfunction "2_2") (pintype "passive"))
      (node (ref "C153") (pin "2") (pinfunction "2_2") (pintype "passive"))
      (node (ref "C154") (pin "2") (pinfunction "2_2") (pintype "passive"))
      (node (ref "C155") (pin "2") (pinfunction "2_2") (pintype "passive"))
      (node (ref "C156") (pin "2") (pinfunction "2_2") (pintype "passive"))
      (node (ref "C157") (pin "2") (pinfunction "2_2") (pintype "passive"))
      (node (ref "C158") (pin "2") (pinfunction "2_2") (pintype "passive"))
      (node (ref "C159") (pin "2") (pinfunction "2_2") (pintype "passive"))
      (node (ref "C160") (pin "2") (pinfunction "2_2") (pintype "passive"))
      (node (ref "C161") (pin "2") (pinfunction "2_2") (pintype "passive"))
      (node (ref "C162") (pin "2") (pinfunction "2_2") (pintype "passive"))
      (node (ref "C163") (pin "2") (pinfunction "2_2") (pintype "passive"))
      (node (ref "C164") (pin "2") (pinfunction "2_2") (pintype "passive"))
      (node (ref "C167") (pin "2") (pinfunction "2_2") (pintype "passive"))
      (node (ref "C168") (pin "2") (pinfunction "2_2") (pintype "passive"))
      (node (ref "C169") (pin "2") (pinfunction "2_2") (pintype "passive"))
      (node (ref "C17") (pin "2") (pinfunction "2_2") (pintype "passive"))
      (node (ref "C170") (pin "2") (pinfunction "2_2") (pintype "passive"))
      (node (ref "C171") (pin "2") (pinfunction "2_2") (pintype "passive"))
      (node (ref "C172") (pin "2") (pinfunction "2_2") (pintype "passive"))
      (node (ref "C173") (pin "2") (pinfunction "2_2") (pintype "passive"))
      (node (ref "C174") (pin "2") (pinfunction "2_2") (pintype "passive"))
      (node (ref "C175") (pin "2") (pinfunction "2_2") (pintype "passive"))
      (node (ref "C176") (pin "2") (pinfunction "2_2") (pintype "passive"))
      (node (ref "C177") (pin "2") (pinfunction "2_2") (pintype "passive"))
      (node (ref "C178") (pin "2") (pinfunction "2_2") (pintype "passive"))
      (node (ref "C179") (pin "2") (pinfunction "2_2") (pintype "passive"))
      (node (ref "C18") (pin "2") (pinfunction "2_2") (pintype "passive"))
      (node (ref "C180") (pin "2") (pinfunction "2_2") (pintype "passive"))
      (node (ref "C181") (pin "2") (pinfunction "2_2") (pintype "passive"))
      (node (ref "C182") (pin "2") (pinfunction "2_2") (pintype "passive"))
      (node (ref "C183") (pin "2") (pinfunction "2_2") (pintype "passive"))
      (node (ref "C184") (pin "2") (pinfunction "2_2") (pintype "passive"))
      (node (ref "C185") (pin "2") (pinfunction "2_2") (pintype "passive"))
      (node (ref "C186") (pin "2") (pinfunction "2_2") (pintype "passive"))
      (node (ref "C187") (pin "2") (pinfunction "2_2") (pintype "passive"))
      (node (ref "C188") (pin "2") (pinfunction "2_2") (pintype "passive"))
      (node (ref "C189") (pin "2") (pinfunction "2_2") (pintype "passive"))
      (node (ref "C19") (pin "2") (pinfunction "2_2") (pintype "passive"))
      (node (ref "C190") (pin "2") (pinfunction "2_2") (pintype "passive"))
      (node (ref "C191") (pin "2") (pinfunction "2_2") (pintype "passive"))
      (node (ref "C192") (pin "2") (pinfunction "2_2") (pintype "passive"))
      (node (ref "C193") (pin "2") (pinfunction "2_2") (pintype "passive"))
      (node (ref "C194") (pin "2") (pinfunction "2_2") (pintype "passive"))
      (node (ref "C197") (pin "2") (pinfunction "2_2") (pintype "passive"))
      (node (ref "C198") (pin "2") (pinfunction "2_2") (pintype "passive"))
      (node (ref "C199") (pin "2") (pinfunction "2_2") (pintype "passive"))
      (node (ref "C2") (pin "2") (pinfunction "2_2") (pintype "passive"))
      (node (ref "C20") (pin "2") (pinfunction "2_2") (pintype "passive"))
      (node (ref "C200") (pin "2") (pinfunction "2_2") (pintype "passive"))
      (node (ref "C201") (pin "2") (pinfunction "2_2") (pintype "passive"))
      (node (ref "C202") (pin "2") (pinfunction "2_2") (pintype "passive"))
      (node (ref "C203") (pin "2") (pinfunction "2_2") (pintype "passive"))
      (node (ref "C204") (pin "2") (pinfunction "2_2") (pintype "passive"))
      (node (ref "C205") (pin "2") (pinfunction "2_2") (pintype "passive"))
      (node (ref "C206") (pin "2") (pinfunction "2_2") (pintype "passive"))
      (node (ref "C207") (pin "2") (pinfunction "2_2") (pintype "passive"))
      (node (ref "C208") (pin "2") (pinfunction "2_2") (pintype "passive"))
      (node (ref "C209") (pin "2") (pinfunction "2_2") (pintype "passive"))
      (node (ref "C21") (pin "2") (pinfunction "2_2") (pintype "passive"))
      (node (ref "C210") (pin "2") (pinfunction "2_2") (pintype "passive"))
      (node (ref "C211") (pin "2") (pinfunction "2_2") (pintype "passive"))
      (node (ref "C212") (pin "2") (pinfunction "2_2") (pintype "passive"))
      (node (ref "C213") (pin "2") (pinfunction "2_2") (pintype "passive"))
      (node (ref "C214") (pin "2") (pinfunction "2_2") (pintype "passive"))
      (node (ref "C215") (pin "2") (pinfunction "2_2") (pintype "passive"))
      (node (ref "C216") (pin "2") (pinfunction "2_2") (pintype "passive"))
      (node (ref "C217") (pin "2") (pinfunction "2_2") (pintype "passive"))
      (node (ref "C218") (pin "2") (pinfunction "2_2") (pintype "passive"))
      (node (ref "C219") (pin "2") (pinfunction "2_2") (pintype "passive"))
      (node (ref "C22") (pin "2") (pinfunction "2_2") (pintype "passive"))
      (node (ref "C220") (pin "2") (pinfunction "2_2") (pintype "passive"))
      (node (ref "C221") (pin "2") (pinfunction "2_2") (pintype "passive"))
      (node (ref "C222") (pin "2") (pinfunction "2_2") (pintype "passive"))
      (node (ref "C223") (pin "2") (pinfunction "2_2") (pintype "passive"))
      (node (ref "C224") (pin "2") (pinfunction "2_2") (pintype "passive"))
      (node (ref "C226") (pin "2") (pinfunction "2_2") (pintype "passive"))
      (node (ref "C228") (pin "2") (pinfunction "2_2") (pintype "passive"))
      (node (ref "C229") (pin "2") (pinfunction "2_2") (pintype "passive"))
      (node (ref "C23") (pin "2") (pinfunction "2_2") (pintype "passive"))
      (node (ref "C24") (pin "2") (pinfunction "2_2") (pintype "passive"))
      (node (ref "C25") (pin "2") (pinfunction "2_2") (pintype "passive"))
      (node (ref "C26") (pin "2") (pinfunction "2_2") (pintype "passive"))
      (node (ref "C27") (pin "2") (pinfunction "2_2") (pintype "passive"))
      (node (ref "C28") (pin "2") (pinfunction "2_2") (pintype "passive"))
      (node (ref "C29") (pin "2") (pinfunction "2_2") (pintype "passive"))
      (node (ref "C3") (pin "2") (pinfunction "2_2") (pintype "passive"))
      (node (ref "C30") (pin "2") (pinfunction "2_2") (pintype "passive"))
      (node (ref "C31") (pin "2") (pinfunction "2_2") (pintype "passive"))
      (node (ref "C32") (pin "2") (pinfunction "2_2") (pintype "passive"))
      (node (ref "C33") (pin "2") (pinfunction "2_2") (pintype "passive"))
      (node (ref "C34") (pin "2") (pinfunction "2_2") (pintype "passive"))
      (node (ref "C35") (pin "2") (pinfunction "2_2") (pintype "passive"))
      (node (ref "C36") (pin "2") (pinfunction "2_2") (pintype "passive"))
      (node (ref "C37") (pin "2") (pinfunction "2_2") (pintype "passive"))
      (node (ref "C38") (pin "2") (pinfunction "2_2") (pintype "passive"))
      (node (ref "C39") (pin "2") (pinfunction "2_2") (pintype "passive"))
      (node (ref "C4") (pin "2") (pinfunction "2_2") (pintype "passive"))
      (node (ref "C40") (pin "2") (pinfunction "2_2") (pintype "passive"))
      (node (ref "C41") (pin "2") (pinfunction "2_2") (pintype "passive"))
      (node (ref "C42") (pin "2") (pinfunction "2_2") (pintype "passive"))
      (node (ref "C43") (pin "2") (pinfunction "2_2") (pintype "passive"))
      (node (ref "C44") (pin "2") (pinfunction "2_2") (pintype "passive"))
      (node (ref "C47") (pin "2") (pinfunction "2_2") (pintype "passive"))
      (node (ref "C48") (pin "2") (pinfunction "2_2") (pintype "passive"))
      (node (ref "C49") (pin "2") (pinfunction "2_2") (pintype "passive"))
      (node (ref "C5") (pin "2") (pinfunction "2_2") (pintype "passive"))
      (node (ref "C50") (pin "2") (pinfunction "2_2") (pintype "passive"))
      (node (ref "C51") (pin "2") (pinfunction "2_2") (pintype "passive"))
      (node (ref "C52") (pin "2") (pinfunction "2_2") (pintype "passive"))
      (node (ref "C53") (pin "2") (pinfunction "2_2") (pintype "passive"))
      (node (ref "C54") (pin "2") (pinfunction "2_2") (pintype "passive"))
      (node (ref "C55") (pin "2") (pinfunction "2_2") (pintype "passive"))
      (node (ref "C56") (pin "2") (pinfunction "2_2") (pintype "passive"))
      (node (ref "C57") (pin "2") (pinfunction "2_2") (pintype "passive"))
      (node (ref "C58") (pin "2") (pinfunction "2_2") (pintype "passive"))
      (node (ref "C59") (pin "2") (pinfunction "2_2") (pintype "passive"))
      (node (ref "C6") (pin "2") (pinfunction "2_2") (pintype "passive"))
      (node (ref "C60") (pin "2") (pinfunction "2_2") (pintype "passive"))
      (node (ref "C61") (pin "2") (pinfunction "2_2") (pintype "passive"))
      (node (ref "C62") (pin "2") (pinfunction "2_2") (pintype "passive"))
      (node (ref "C63") (pin "2") (pinfunction "2_2") (pintype "passive"))
      (node (ref "C64") (pin "2") (pinfunction "2_2") (pintype "passive"))
      (node (ref "C65") (pin "2") (pinfunction "2_2") (pintype "passive"))
      (node (ref "C66") (pin "2") (pinfunction "2_2") (pintype "passive"))
      (node (ref "C67") (pin "2") (pinfunction "2_2") (pintype "passive"))
      (node (ref "C68") (pin "2") (pinfunction "2_2") (pintype "passive"))
      (node (ref "C69") (pin "2") (pinfunction "2_2") (pintype "passive"))
      (node (ref "C7") (pin "2") (pinfunction "2_2") (pintype "passive"))
      (node (ref "C70") (pin "2") (pinfunction "2_2") (pintype "passive"))
      (node (ref "C71") (pin "2") (pinfunction "2_2") (pintype "passive"))
      (node (ref "C72") (pin "2") (pinfunction "2_2") (pintype "passive"))
      (node (ref "C73") (pin "2") (pinfunction "2_2") (pintype "passive"))
      (node (ref "C74") (pin "2") (pinfunction "2_2") (pintype "passive"))
      (node (ref "C77") (pin "2") (pinfunction "2_2") (pintype "passive"))
      (node (ref "C78") (pin "2") (pinfunction "2_2") (pintype "passive"))
      (node (ref "C79") (pin "2") (pinfunction "2_2") (pintype "passive"))
      (node (ref "C8") (pin "2") (pinfunction "2_2") (pintype "passive"))
      (node (ref "C80") (pin "2") (pinfunction "2_2") (pintype "passive"))
      (node (ref "C81") (pin "2") (pinfunction "2_2") (pintype "passive"))
      (node (ref "C82") (pin "2") (pinfunction "2_2") (pintype "passive"))
      (node (ref "C83") (pin "2") (pinfunction "2_2") (pintype "passive"))
      (node (ref "C84") (pin "2") (pinfunction "2_2") (pintype "passive"))
      (node (ref "C85") (pin "2") (pinfunction "2_2") (pintype "passive"))
      (node (ref "C86") (pin "2") (pinfunction "2_2") (pintype "passive"))
      (node (ref "C87") (pin "2") (pinfunction "2_2") (pintype "passive"))
      (node (ref "C88") (pin "2") (pinfunction "2_2") (pintype "passive"))
      (node (ref "C89") (pin "2") (pinfunction "2_2") (pintype "passive"))
      (node (ref "C9") (pin "2") (pinfunction "2_2") (pintype "passive"))
      (node (ref "C90") (pin "2") (pinfunction "2_2") (pintype "passive"))
      (node (ref "C91") (pin "2") (pinfunction "2_2") (pintype "passive"))
      (node (ref "C92") (pin "2") (pinfunction "2_2") (pintype "passive"))
      (node (ref "C93") (pin "2") (pinfunction "2_2") (pintype "passive"))
      (node (ref "C94") (pin "2") (pinfunction "2_2") (pintype "passive"))
      (node (ref "C95") (pin "2") (pinfunction "2_2") (pintype "passive"))
      (node (ref "C96") (pin "2") (pinfunction "2_2") (pintype "passive"))
      (node (ref "C97") (pin "2") (pinfunction "2_2") (pintype "passive"))
      (node (ref "C98") (pin "2") (pinfunction "2_2") (pintype "passive"))
      (node (ref "C99") (pin "2") (pinfunction "2_2") (pintype "passive"))
      (node (ref "D1") (pin "1") (pinfunction "VDD_1") (pintype "bidirectional"))
      (node (ref "D10") (pin "1") (pinfunction "VDD_1") (pintype "bidirectional"))
      (node (ref "D100") (pin "1") (pinfunction "VDD_1") (pintype "bidirectional"))
      (node (ref "D101") (pin "1") (pinfunction "VDD_1") (pintype "bidirectional"))
      (node (ref "D102") (pin "1") (pinfunction "VDD_1") (pintype "bidirectional"))
      (node (ref "D103") (pin "1") (pinfunction "VDD_1") (pintype "bidirectional"))
      (node (ref "D104") (pin "1") (pinfunction "VDD_1") (pintype "bidirectional"))
      (node (ref "D105") (pin "1") (pinfunction "VDD_1") (pintype "bidirectional"))
      (node (ref "D106") (pin "1") (pinfunction "VDD_1") (pintype "bidirectional"))
      (node (ref "D107") (pin "1") (pinfunction "VDD_1") (pintype "bidirectional"))
      (node (ref "D108") (pin "1") (pinfunction "VDD_1") (pintype "bidirectional"))
      (node (ref "D109") (pin "1") (pinfunction "VDD_1") (pintype "bidirectional"))
      (node (ref "D11") (pin "1") (pinfunction "VDD_1") (pintype "bidirectional"))
      (node (ref "D110") (pin "1") (pinfunction "VDD_1") (pintype "bidirectional"))
      (node (ref "D111") (pin "1") (pinfunction "VDD_1") (pintype "bidirectional"))
      (node (ref "D112") (pin "1") (pinfunction "VDD_1") (pintype "bidirectional"))
      (node (ref "D113") (pin "1") (pinfunction "VDD_1") (pintype "bidirectional"))
      (node (ref "D114") (pin "1") (pinfunction "VDD_1") (pintype "bidirectional"))
      (node (ref "D115") (pin "1") (pinfunction "VDD_1") (pintype "bidirectional"))
      (node (ref "D116") (pin "1") (pinfunction "VDD_1") (pintype "bidirectional"))
      (node (ref "D117") (pin "1") (pinfunction "VDD_1") (pintype "bidirectional"))
      (node (ref "D118") (pin "1") (pinfunction "VDD_1") (pintype "bidirectional"))
      (node (ref "D119") (pin "1") (pinfunction "VDD_1") (pintype "bidirectional"))
      (node (ref "D12") (pin "1") (pinfunction "VDD_1") (pintype "bidirectional"))
      (node (ref "D120") (pin "1") (pinfunction "VDD_1") (pintype "bidirectional"))
      (node (ref "D121") (pin "1") (pinfunction "VDD_1") (pintype "bidirectional"))
      (node (ref "D122") (pin "1") (pinfunction "VDD_1") (pintype "bidirectional"))
      (node (ref "D123") (pin "1") (pinfunction "VDD_1") (pintype "bidirectional"))
      (node (ref "D124") (pin "1") (pinfunction "VDD_1") (pintype "bidirectional"))
      (node (ref "D125") (pin "1") (pinfunction "VDD_1") (pintype "bidirectional"))
      (node (ref "D126") (pin "1") (pinfunction "VDD_1") (pintype "bidirectional"))
      (node (ref "D127") (pin "1") (pinfunction "VDD_1") (pintype "bidirectional"))
      (node (ref "D128") (pin "1") (pinfunction "VDD_1") (pintype "bidirectional"))
      (node (ref "D129") (pin "1") (pinfunction "VDD_1") (pintype "bidirectional"))
      (node (ref "D13") (pin "1") (pinfunction "VDD_1") (pintype "bidirectional"))
      (node (ref "D130") (pin "1") (pinfunction "VDD_1") (pintype "bidirectional"))
      (node (ref "D131") (pin "1") (pinfunction "VDD_1") (pintype "bidirectional"))
      (node (ref "D132") (pin "1") (pinfunction "VDD_1") (pintype "bidirectional"))
      (node (ref "D133") (pin "1") (pinfunction "VDD_1") (pintype "bidirectional"))
      (node (ref "D134") (pin "1") (pinfunction "VDD_1") (pintype "bidirectional"))
      (node (ref "D135") (pin "1") (pinfunction "VDD_1") (pintype "bidirectional"))
      (node (ref "D136") (pin "1") (pinfunction "VDD_1") (pintype "bidirectional"))
      (node (ref "D137") (pin "1") (pinfunction "VDD_1") (pintype "bidirectional"))
      (node (ref "D138") (pin "1") (pinfunction "VDD_1") (pintype "bidirectional"))
      (node (ref "D139") (pin "1") (pinfunction "VDD_1") (pintype "bidirectional"))
      (node (ref "D14") (pin "1") (pinfunction "VDD_1") (pintype "bidirectional"))
      (node (ref "D140") (pin "1") (pinfunction "VDD_1") (pintype "bidirectional"))
      (node (ref "D141") (pin "1") (pinfunction "VDD_1") (pintype "bidirectional"))
      (node (ref "D142") (pin "1") (pinfunction "VDD_1") (pintype "bidirectional"))
      (node (ref "D143") (pin "1") (pinfunction "VDD_1") (pintype "bidirectional"))
      (node (ref "D144") (pin "1") (pinfunction "VDD_1") (pintype "bidirectional"))
      (node (ref "D145") (pin "1") (pinfunction "VDD_1") (pintype "bidirectional"))
      (node (ref "D146") (pin "1") (pinfunction "VDD_1") (pintype "bidirectional"))
      (node (ref "D147") (pin "1") (pinfunction "VDD_1") (pintype "bidirectional"))
      (node (ref "D148") (pin "1") (pinfunction "VDD_1") (pintype "bidirectional"))
      (node (ref "D149") (pin "1") (pinfunction "VDD_1") (pintype "bidirectional"))
      (node (ref "D15") (pin "1") (pinfunction "VDD_1") (pintype "bidirectional"))
      (node (ref "D150") (pin "1") (pinfunction "VDD_1") (pintype "bidirectional"))
      (node (ref "D151") (pin "1") (pinfunction "VDD_1") (pintype "bidirectional"))
      (node (ref "D152") (pin "1") (pinfunction "VDD_1") (pintype "bidirectional"))
      (node (ref "D153") (pin "1") (pinfunction "VDD_1") (pintype "bidirectional"))
      (node (ref "D154") (pin "1") (pinfunction "VDD_1") (pintype "bidirectional"))
      (node (ref "D155") (pin "1") (pinfunction "VDD_1") (pintype "bidirectional"))
      (node (ref "D156") (pin "1") (pinfunction "VDD_1") (pintype "bidirectional"))
      (node (ref "D157") (pin "1") (pinfunction "VDD_1") (pintype "bidirectional"))
      (node (ref "D158") (pin "1") (pinfunction "VDD_1") (pintype "bidirectional"))
      (node (ref "D159") (pin "1") (pinfunction "VDD_1") (pintype "bidirectional"))
      (node (ref "D16") (pin "1") (pinfunction "VDD_1") (pintype "bidirectional"))
      (node (ref "D160") (pin "1") (pinfunction "VDD_1") (pintype "bidirectional"))
      (node (ref "D161") (pin "1") (pinfunction "VDD_1") (pintype "bidirectional"))
      (node (ref "D162") (pin "1") (pinfunction "VDD_1") (pintype "bidirectional"))
      (node (ref "D163") (pin "1") (pinfunction "VDD_1") (pintype "bidirectional"))
      (node (ref "D164") (pin "1") (pinfunction "VDD_1") (pintype "bidirectional"))
      (node (ref "D165") (pin "1") (pinfunction "VDD_1") (pintype "bidirectional"))
      (node (ref "D166") (pin "1") (pinfunction "VDD_1") (pintype "bidirectional"))
      (node (ref "D167") (pin "1") (pinfunction "VDD_1") (pintype "bidirectional"))
      (node (ref "D168") (pin "1") (pinfunction "VDD_1") (pintype "bidirectional"))
      (node (ref "D169") (pin "1") (pinfunction "VDD_1") (pintype "bidirectional"))
      (node (ref "D17") (pin "1") (pinfunction "VDD_1") (pintype "bidirectional"))
      (node (ref "D170") (pin "1") (pinfunction "VDD_1") (pintype "bidirectional"))
      (node (ref "D171") (pin "1") (pinfunction "VDD_1") (pintype "bidirectional"))
      (node (ref "D172") (pin "1") (pinfunction "VDD_1") (pintype "bidirectional"))
      (node (ref "D173") (pin "1") (pinfunction "VDD_1") (pintype "bidirectional"))
      (node (ref "D174") (pin "1") (pinfunction "VDD_1") (pintype "bidirectional"))
      (node (ref "D175") (pin "1") (pinfunction "VDD_1") (pintype "bidirectional"))
      (node (ref "D176") (pin "1") (pinfunction "VDD_1") (pintype "bidirectional"))
      (node (ref "D177") (pin "1") (pinfunction "VDD_1") (pintype "bidirectional"))
      (node (ref "D178") (pin "1") (pinfunction "VDD_1") (pintype "bidirectional"))
      (node (ref "D179") (pin "1") (pinfunction "VDD_1") (pintype "bidirectional"))
      (node (ref "D18") (pin "1") (pinfunction "VDD_1") (pintype "bidirectional"))
      (node (ref "D180") (pin "1") (pinfunction "VDD_1") (pintype "bidirectional"))
      (node (ref "D181") (pin "1") (pinfunction "VDD_1") (pintype "bidirectional"))
      (node (ref "D182") (pin "1") (pinfunction "VDD_1") (pintype "bidirectional"))
      (node (ref "D183") (pin "1") (pinfunction "VDD_1") (pintype "bidirectional"))
      (node (ref "D184") (pin "1") (pinfunction "VDD_1") (pintype "bidirectional"))
      (node (ref "D185") (pin "1") (pinfunction "VDD_1") (pintype "bidirectional"))
      (node (ref "D186") (pin "1") (pinfunction "VDD_1") (pintype "bidirectional"))
      (node (ref "D187") (pin "1") (pinfunction "VDD_1") (pintype "bidirectional"))
      (node (ref "D188") (pin "1") (pinfunction "VDD_1") (pintype "bidirectional"))
      (node (ref "D189") (pin "1") (pinfunction "VDD_1") (pintype "bidirectional"))
      (node (ref "D19") (pin "1") (pinfunction "VDD_1") (pintype "bidirectional"))
      (node (ref "D190") (pin "1") (pinfunction "VDD_1") (pintype "bidirectional"))
      (node (ref "D191") (pin "1") (pinfunction "VDD_1") (pintype "bidirectional"))
      (node (ref "D192") (pin "1") (pinfunction "VDD_1") (pintype "bidirectional"))
      (node (ref "D193") (pin "1") (pinfunction "VDD_1") (pintype "bidirectional"))
      (node (ref "D194") (pin "1") (pinfunction "VDD_1") (pintype "bidirectional"))
      (node (ref "D195") (pin "1") (pinfunction "VDD_1") (pintype "bidirectional"))
      (node (ref "D196") (pin "1") (pinfunction "VDD_1") (pintype "bidirectional"))
      (node (ref "D197") (pin "1") (pinfunction "VDD_1") (pintype "bidirectional"))
      (node (ref "D198") (pin "1") (pinfunction "VDD_1") (pintype "bidirectional"))
      (node (ref "D199") (pin "1") (pinfunction "VDD_1") (pintype "bidirectional"))
      (node (ref "D2") (pin "1") (pinfunction "VDD_1") (pintype "bidirectional"))
      (node (ref "D20") (pin "1") (pinfunction "VDD_1") (pintype "bidirectional"))
      (node (ref "D200") (pin "1") (pinfunction "VDD_1") (pintype "bidirectional"))
      (node (ref "D201") (pin "1") (pinfunction "VDD_1") (pintype "bidirectional"))
      (node (ref "D202") (pin "1") (pinfunction "VDD_1") (pintype "bidirectional"))
      (node (ref "D203") (pin "1") (pinfunction "VDD_1") (pintype "bidirectional"))
      (node (ref "D204") (pin "1") (pinfunction "VDD_1") (pintype "bidirectional"))
      (node (ref "D205") (pin "1") (pinfunction "VDD_1") (pintype "bidirectional"))
      (node (ref "D206") (pin "1") (pinfunction "VDD_1") (pintype "bidirectional"))
      (node (ref "D207") (pin "1") (pinfunction "VDD_1") (pintype "bidirectional"))
      (node (ref "D208") (pin "1") (pinfunction "VDD_1") (pintype "bidirectional"))
      (node (ref "D209") (pin "1") (pinfunction "VDD_1") (pintype "bidirectional"))
      (node (ref "D21") (pin "1") (pinfunction "VDD_1") (pintype "bidirectional"))
      (node (ref "D210") (pin "1") (pinfunction "VDD_1") (pintype "bidirectional"))
      (node (ref "D211") (pin "1") (pinfunction "VDD_1") (pintype "bidirectional"))
      (node (ref "D212") (pin "1") (pinfunction "VDD_1") (pintype "bidirectional"))
      (node (ref "D213") (pin "1") (pinfunction "VDD_1") (pintype "bidirectional"))
      (node (ref "D214") (pin "1") (pinfunction "VDD_1") (pintype "bidirectional"))
      (node (ref "D215") (pin "1") (pinfunction "VDD_1") (pintype "bidirectional"))
      (node (ref "D216") (pin "1") (pinfunction "VDD_1") (pintype "bidirectional"))
      (node (ref "D217") (pin "1") (pinfunction "VDD_1") (pintype "bidirectional"))
      (node (ref "D218") (pin "1") (pinfunction "VDD_1") (pintype "bidirectional"))
      (node (ref "D219") (pin "1") (pinfunction "VDD_1") (pintype "bidirectional"))
      (node (ref "D22") (pin "1") (pinfunction "VDD_1") (pintype "bidirectional"))
      (node (ref "D220") (pin "1") (pinfunction "VDD_1") (pintype "bidirectional"))
      (node (ref "D221") (pin "1") (pinfunction "VDD_1") (pintype "bidirectional"))
      (node (ref "D222") (pin "1") (pinfunction "VDD_1") (pintype "bidirectional"))
      (node (ref "D223") (pin "1") (pinfunction "VDD_1") (pintype "bidirectional"))
      (node (ref "D224") (pin "1") (pinfunction "VDD_1") (pintype "bidirectional"))
      (node (ref "D225") (pin "1") (pinfunction "VDD_1") (pintype "bidirectional"))
      (node (ref "D23") (pin "1") (pinfunction "VDD_1") (pintype "bidirectional"))
      (node (ref "D24") (pin "1") (pinfunction "VDD_1") (pintype "bidirectional"))
      (node (ref "D25") (pin "1") (pinfunction "VDD_1") (pintype "bidirectional"))
      (node (ref "D26") (pin "1") (pinfunction "VDD_1") (pintype "bidirectional"))
      (node (ref "D27") (pin "1") (pinfunction "VDD_1") (pintype "bidirectional"))
      (node (ref "D28") (pin "1") (pinfunction "VDD_1") (pintype "bidirectional"))
      (node (ref "D29") (pin "1") (pinfunction "VDD_1") (pintype "bidirectional"))
      (node (ref "D3") (pin "1") (pinfunction "VDD_1") (pintype "bidirectional"))
      (node (ref "D30") (pin "1") (pinfunction "VDD_1") (pintype "bidirectional"))
      (node (ref "D31") (pin "1") (pinfunction "VDD_1") (pintype "bidirectional"))
      (node (ref "D32") (pin "1") (pinfunction "VDD_1") (pintype "bidirectional"))
      (node (ref "D33") (pin "1") (pinfunction "VDD_1") (pintype "bidirectional"))
      (node (ref "D34") (pin "1") (pinfunction "VDD_1") (pintype "bidirectional"))
      (node (ref "D35") (pin "1") (pinfunction "VDD_1") (pintype "bidirectional"))
      (node (ref "D36") (pin "1") (pinfunction "VDD_1") (pintype "bidirectional"))
      (node (ref "D37") (pin "1") (pinfunction "VDD_1") (pintype "bidirectional"))
      (node (ref "D38") (pin "1") (pinfunction "VDD_1") (pintype "bidirectional"))
      (node (ref "D39") (pin "1") (pinfunction "VDD_1") (pintype "bidirectional"))
      (node (ref "D4") (pin "1") (pinfunction "VDD_1") (pintype "bidirectional"))
      (node (ref "D40") (pin "1") (pinfunction "VDD_1") (pintype "bidirectional"))
      (node (ref "D41") (pin "1") (pinfunction "VDD_1") (pintype "bidirectional"))
      (node (ref "D42") (pin "1") (pinfunction "VDD_1") (pintype "bidirectional"))
      (node (ref "D43") (pin "1") (pinfunction "VDD_1") (pintype "bidirectional"))
      (node (ref "D44") (pin "1") (pinfunction "VDD_1") (pintype "bidirectional"))
      (node (ref "D45") (pin "1") (pinfunction "VDD_1") (pintype "bidirectional"))
      (node (ref "D46") (pin "1") (pinfunction "VDD_1") (pintype "bidirectional"))
      (node (ref "D47") (pin "1") (pinfunction "VDD_1") (pintype "bidirectional"))
      (node (ref "D48") (pin "1") (pinfunction "VDD_1") (pintype "bidirectional"))
      (node (ref "D49") (pin "1") (pinfunction "VDD_1") (pintype "bidirectional"))
      (node (ref "D5") (pin "1") (pinfunction "VDD_1") (pintype "bidirectional"))
      (node (ref "D50") (pin "1") (pinfunction "VDD_1") (pintype "bidirectional"))
      (node (ref "D51") (pin "1") (pinfunction "VDD_1") (pintype "bidirectional"))
      (node (ref "D52") (pin "1") (pinfunction "VDD_1") (pintype "bidirectional"))
      (node (ref "D53") (pin "1") (pinfunction "VDD_1") (pintype "bidirectional"))
      (node (ref "D54") (pin "1") (pinfunction "VDD_1") (pintype "bidirectional"))
      (node (ref "D55") (pin "1") (pinfunction "VDD_1") (pintype "bidirectional"))
      (node (ref "D56") (pin "1") (pinfunction "VDD_1") (pintype "bidirectional"))
      (node (ref "D57") (pin "1") (pinfunction "VDD_1") (pintype "bidirectional"))
      (node (ref "D58") (pin "1") (pinfunction "VDD_1") (pintype "bidirectional"))
      (node (ref "D59") (pin "1") (pinfunction "VDD_1") (pintype "bidirectional"))
      (node (ref "D6") (pin "1") (pinfunction "VDD_1") (pintype "bidirectional"))
      (node (ref "D60") (pin "1") (pinfunction "VDD_1") (pintype "bidirectional"))
      (node (ref "D61") (pin "1") (pinfunction "VDD_1") (pintype "bidirectional"))
      (node (ref "D62") (pin "1") (pinfunction "VDD_1") (pintype "bidirectional"))
      (node (ref "D63") (pin "1") (pinfunction "VDD_1") (pintype "bidirectional"))
      (node (ref "D64") (pin "1") (pinfunction "VDD_1") (pintype "bidirectional"))
      (node (ref "D65") (pin "1") (pinfunction "VDD_1") (pintype "bidirectional"))
      (node (ref "D66") (pin "1") (pinfunction "VDD_1") (pintype "bidirectional"))
      (node (ref "D67") (pin "1") (pinfunction "VDD_1") (pintype "bidirectional"))
      (node (ref "D68") (pin "1") (pinfunction "VDD_1") (pintype "bidirectional"))
      (node (ref "D69") (pin "1") (pinfunction "VDD_1") (pintype "bidirectional"))
      (node (ref "D7") (pin "1") (pinfunction "VDD_1") (pintype "bidirectional"))
      (node (ref "D70") (pin "1") (pinfunction "VDD_1") (pintype "bidirectional"))
      (node (ref "D71") (pin "1") (pinfunction "VDD_1") (pintype "bidirectional"))
      (node (ref "D72") (pin "1") (pinfunction "VDD_1") (pintype "bidirectional"))
      (node (ref "D73") (pin "1") (pinfunction "VDD_1") (pintype "bidirectional"))
      (node (ref "D74") (pin "1") (pinfunction "VDD_1") (pintype "bidirectional"))
      (node (ref "D75") (pin "1") (pinfunction "VDD_1") (pintype "bidirectional"))
      (node (ref "D76") (pin "1") (pinfunction "VDD_1") (pintype "bidirectional"))
      (node (ref "D77") (pin "1") (pinfunction "VDD_1") (pintype "bidirectional"))
      (node (ref "D78") (pin "1") (pinfunction "VDD_1") (pintype "bidirectional"))
      (node (ref "D79") (pin "1") (pinfunction "VDD_1") (pintype "bidirectional"))
      (node (ref "D8") (pin "1") (pinfunction "VDD_1") (pintype "bidirectional"))
      (node (ref "D80") (pin "1") (pinfunction "VDD_1") (pintype "bidirectional"))
      (node (ref "D81") (pin "1") (pinfunction "VDD_1") (pintype "bidirectional"))
      (node (ref "D82") (pin "1") (pinfunction "VDD_1") (pintype "bidirectional"))
      (node (ref "D83") (pin "1") (pinfunction "VDD_1") (pintype "bidirectional"))
      (node (ref "D84") (pin "1") (pinfunction "VDD_1") (pintype "bidirectional"))
      (node (ref "D85") (pin "1") (pinfunction "VDD_1") (pintype "bidirectional"))
      (node (ref "D86") (pin "1") (pinfunction "VDD_1") (pintype "bidirectional"))
      (node (ref "D87") (pin "1") (pinfunction "VDD_1") (pintype "bidirectional"))
      (node (ref "D88") (pin "1") (pinfunction "VDD_1") (pintype "bidirectional"))
      (node (ref "D89") (pin "1") (pinfunction "VDD_1") (pintype "bidirectional"))
      (node (ref "D9") (pin "1") (pinfunction "VDD_1") (pintype "bidirectional"))
      (node (ref "D90") (pin "1") (pinfunction "VDD_1") (pintype "bidirectional"))
      (node (ref "D91") (pin "1") (pinfunction "VDD_1") (pintype "bidirectional"))
      (node (ref "D92") (pin "1") (pinfunction "VDD_1") (pintype "bidirectional"))
      (node (ref "D93") (pin "1") (pinfunction "VDD_1") (pintype "bidirectional"))
      (node (ref "D94") (pin "1") (pinfunction "VDD_1") (pintype "bidirectional"))
      (node (ref "D95") (pin "1") (pinfunction "VDD_1") (pintype "bidirectional"))
      (node (ref "D96") (pin "1") (pinfunction "VDD_1") (pintype "bidirectional"))
      (node (ref "D97") (pin "1") (pinfunction "VDD_1") (pintype "bidirectional"))
      (node (ref "D98") (pin "1") (pinfunction "VDD_1") (pintype "bidirectional"))
      (node (ref "D99") (pin "1") (pinfunction "VDD_1") (pintype "bidirectional"))
      (node (ref "DISPLAY_1") (pin "3") (pinfunction "G1_3") (pintype "bidirectional"))
      (node (ref "DISPLAY_1") (pin "8") (pinfunction "G2_8") (pintype "bidirectional"))
      (node (ref "DISPLAY_2") (pin "3") (pinfunction "G1_3") (pintype "bidirectional"))
      (node (ref "DISPLAY_2") (pin "8") (pinfunction "G2_8") (pintype "bidirectional"))
      (node (ref "DISPLAY_3") (pin "3") (pinfunction "G1_3") (pintype "bidirectional"))
      (node (ref "DISPLAY_3") (pin "8") (pinfunction "G2_8") (pintype "bidirectional"))
      (node (ref "DISPLAY_4") (pin "3") (pinfunction "G1_3") (pintype "bidirectional"))
      (node (ref "DISPLAY_4") (pin "8") (pinfunction "G2_8") (pintype "bidirectional"))
      (node (ref "DISPLAY_5") (pin "3") (pinfunction "G1_3") (pintype "bidirectional"))
      (node (ref "DISPLAY_5") (pin "8") (pinfunction "G2_8") (pintype "bidirectional"))
      (node (ref "S1") (pin "3") (pinfunction "2_3") (pintype "passive"))
      (node (ref "S1") (pin "4") (pinfunction "2_4") (pintype "passive"))
      (node (ref "S2") (pin "3") (pinfunction "2_3") (pintype "passive"))
      (node (ref "S2") (pin "4") (pinfunction "2_4") (pintype "passive"))
      (node (ref "S3") (pin "3") (pinfunction "2_3") (pintype "passive"))
      (node (ref "S3") (pin "4") (pinfunction "2_4") (pintype "passive"))
      (node (ref "S4") (pin "3") (pinfunction "2_3") (pintype "passive"))
      (node (ref "S4") (pin "4") (pinfunction "2_4") (pintype "passive"))
      (node (ref "S5") (pin "3") (pinfunction "2_3") (pintype "passive"))
      (node (ref "S5") (pin "4") (pinfunction "2_4") (pintype "passive"))
      (node (ref "U1") (pin "13") (pinfunction "G_13") (pintype "input"))
      (node (ref "U1") (pin "8") (pinfunction "GND_8") (pintype "power_in"))
      (node (ref "U2") (pin "13") (pinfunction "G_13") (pintype "input"))
      (node (ref "U2") (pin "8") (pinfunction "GND_8") (pintype "power_in"))
      (node (ref "U3") (pin "13") (pinfunction "G_13") (pintype "input"))
      (node (ref "U3") (pin "8") (pinfunction "GND_8") (pintype "power_in"))
      (node (ref "U4") (pin "13") (pinfunction "G_13") (pintype "input"))
      (node (ref "U4") (pin "8") (pinfunction "GND_8") (pintype "power_in"))
      (node (ref "U5") (pin "13") (pinfunction "G_13") (pintype "input"))
      (node (ref "U5") (pin "8") (pinfunction "GND_8") (pintype "power_in"))
      (node (ref "U6") (pin "GND") (pinfunction "GND_GND") (pintype "input"))
    )
    (net (code "45") (name "GPIO_12") (class "Default")
      (node (ref "B2") (pin "8") (pinfunction "12_8") (pintype "bidirectional"))
      (node (ref "R50") (pin "1") (pinfunction "1_1") (pintype "passive"))
      (node (ref "T2") (pin "2") (pinfunction "S_2") (pintype "passive"))
    )
    (net (code "46") (name "GPIO_14") (class "Default")
      (node (ref "B2") (pin "9") (pinfunction "14_9") (pintype "bidirectional"))
      (node (ref "R52") (pin "1") (pinfunction "1_1") (pintype "passive"))
      (node (ref "T3") (pin "2") (pinfunction "S_2") (pintype "passive"))
    )
    (net (code "47") (name "GPIO_25") (class "Default")
      (node (ref "B2") (pin "12") (pinfunction "25_12") (pintype "bidirectional"))
      (node (ref "R54") (pin "1") (pinfunction "1_1") (pintype "passive"))
      (node (ref "T4") (pin "2") (pinfunction "S_2") (pintype "passive"))
    )
    (net (code "48") (name "GPIO_26") (class "Default")
      (node (ref "B2") (pin "11") (pinfunction "26_11") (pintype "bidirectional"))
      (node (ref "R45") (pin "1") (pinfunction "1_1") (pintype "passive"))
      (node (ref "T5") (pin "2") (pinfunction "S_2") (pintype "passive"))
    )
    (net (code "49") (name "GPIO_27") (class "Default")
      (node (ref "B2") (pin "10") (pinfunction "27_10") (pintype "bidirectional"))
      (node (ref "R48") (pin "1") (pinfunction "1_1") (pintype "passive"))
      (node (ref "T1") (pin "2") (pinfunction "S_2") (pintype "passive"))
    )
    (net (code "50") (name "GPIO_32") (class "Default")
      (node (ref "B2") (pin "16") (pinfunction "32_16") (pintype "bidirectional"))
      (node (ref "R44") (pin "1") (pinfunction "1_1") (pintype "passive"))
      (node (ref "S4") (pin "1") (pinfunction "1_1") (pintype "passive"))
      (node (ref "S4") (pin "2") (pinfunction "1_2") (pintype "passive"))
    )
    (net (code "51") (name "GPIO_34") (class "Default")
      (node (ref "B2") (pin "14") (pinfunction "34_14") (pintype "bidirectional"))
      (node (ref "R42") (pin "1") (pinfunction "1_1") (pintype "passive"))
      (node (ref "S2") (pin "1") (pinfunction "1_1") (pintype "passive"))
      (node (ref "S2") (pin "2") (pinfunction "1_2") (pintype "passive"))
    )
    (net (code "52") (name "GPIO_35") (class "Default")
      (node (ref "B2") (pin "13") (pinfunction "35_13") (pintype "bidirectional"))
      (node (ref "B3") (pin "S") (pinfunction "*SHTDWN_S") (pintype "bidirectional"))
    )
    (net (code "53") (name "GPIO_36") (class "Default")
      (node (ref "B2") (pin "20") (pinfunction "36_20") (pintype "bidirectional"))
      (node (ref "R43") (pin "1") (pinfunction "1_1") (pintype "passive"))
      (node (ref "S3") (pin "1") (pinfunction "1_1") (pintype "passive"))
      (node (ref "S3") (pin "2") (pinfunction "1_2") (pintype "passive"))
    )
    (net (code "54") (name "GPIO_37") (class "Default")
      (node (ref "B2") (pin "19") (pinfunction "37_19") (pintype "bidirectional"))
      (node (ref "R46") (pin "1") (pinfunction "1_1") (pintype "passive"))
      (node (ref "S5") (pin "1") (pinfunction "1_1") (pintype "passive"))
      (node (ref "S5") (pin "2") (pinfunction "1_2") (pintype "passive"))
    )
    (net (code "55") (name "GPIO_39") (class "Default")
      (node (ref "B2") (pin "17") (pinfunction "39_17") (pintype "bidirectional"))
      (node (ref "R41") (pin "2") (pinfunction "2_2") (pintype "passive"))
      (node (ref "S1") (pin "1") (pinfunction "1_1") (pintype "passive"))
      (node (ref "S1") (pin "2") (pinfunction "1_2") (pintype "passive"))
    )
    (net (code "56") (name "L_DI_0") (class "Default")
      (node (ref "D1") (pin "4") (pinfunction "DI_4") (pintype "bidirectional"))
      (node (ref "R55") (pin "1") (pinfunction "1_1") (pintype "passive"))
      (node (ref "T4") (pin "3") (pinfunction "D_3") (pintype "passive"))
    )
    (net (code "57") (name "Net-(B3-PadOUT+)") (class "Default")
      (node (ref "B3") (pin "OUT+") (pinfunction "OUT+_OUT+") (pintype "bidirectional"))
      (node (ref "LS2") (pin "+") (pinfunction "+_+") (pintype "bidirectional"))
    )
    (net (code "58") (name "Net-(B3-PadOUT-)") (class "Default")
      (node (ref "B3") (pin "OUT-") (pinfunction "OUT-_OUT-") (pintype "bidirectional"))
      (node (ref "LS2") (pin "-") (pinfunction "-_-") (pintype "bidirectional"))
    )
    (net (code "59") (name "Net-(D1-DO)") (class "Default")
      (node (ref "D1") (pin "2") (pinfunction "DO_2") (pintype "bidirectional"))
      (node (ref "D2") (pin "4") (pinfunction "DI_4") (pintype "bidirectional"))
    )
    (net (code "60") (name "Net-(D2-DO)") (class "Default")
      (node (ref "D2") (pin "2") (pinfunction "DO_2") (pintype "bidirectional"))
      (node (ref "D3") (pin "4") (pinfunction "DI_4") (pintype "bidirectional"))
    )
    (net (code "61") (name "Net-(D3-DO)") (class "Default")
      (node (ref "D3") (pin "2") (pinfunction "DO_2") (pintype "bidirectional"))
      (node (ref "D4") (pin "4") (pinfunction "DI_4") (pintype "bidirectional"))
    )
    (net (code "62") (name "Net-(D4-DO)") (class "Default")
      (node (ref "D4") (pin "2") (pinfunction "DO_2") (pintype "bidirectional"))
      (node (ref "D5") (pin "4") (pinfunction "DI_4") (pintype "bidirectional"))
    )
    (net (code "63") (name "Net-(D5-DO)") (class "Default")
      (node (ref "D5") (pin "2") (pinfunction "DO_2") (pintype "bidirectional"))
      (node (ref "D6") (pin "4") (pinfunction "DI_4") (pintype "bidirectional"))
    )
    (net (code "64") (name "Net-(D6-DO)") (class "Default")
      (node (ref "D6") (pin "2") (pinfunction "DO_2") (pintype "bidirectional"))
      (node (ref "D7") (pin "4") (pinfunction "DI_4") (pintype "bidirectional"))
    )
    (net (code "65") (name "Net-(D7-DO)") (class "Default")
      (node (ref "D7") (pin "2") (pinfunction "DO_2") (pintype "bidirectional"))
      (node (ref "D8") (pin "4") (pinfunction "DI_4") (pintype "bidirectional"))
    )
    (net (code "66") (name "Net-(D8-DO)") (class "Default")
      (node (ref "D8") (pin "2") (pinfunction "DO_2") (pintype "bidirectional"))
      (node (ref "D9") (pin "4") (pinfunction "DI_4") (pintype "bidirectional"))
    )
    (net (code "67") (name "Net-(D10-DI)") (class "Default")
      (node (ref "D10") (pin "4") (pinfunction "DI_4") (pintype "bidirectional"))
      (node (ref "D9") (pin "2") (pinfunction "DO_2") (pintype "bidirectional"))
    )
    (net (code "68") (name "Net-(D10-DO)") (class "Default")
      (node (ref "D10") (pin "2") (pinfunction "DO_2") (pintype "bidirectional"))
      (node (ref "D11") (pin "4") (pinfunction "DI_4") (pintype "bidirectional"))
    )
    (net (code "69") (name "Net-(D11-DO)") (class "Default")
      (node (ref "D11") (pin "2") (pinfunction "DO_2") (pintype "bidirectional"))
      (node (ref "D12") (pin "4") (pinfunction "DI_4") (pintype "bidirectional"))
    )
    (net (code "70") (name "Net-(D12-DO)") (class "Default")
      (node (ref "D12") (pin "2") (pinfunction "DO_2") (pintype "bidirectional"))
      (node (ref "D13") (pin "4") (pinfunction "DI_4") (pintype "bidirectional"))
    )
    (net (code "71") (name "Net-(D13-DO)") (class "Default")
      (node (ref "D13") (pin "2") (pinfunction "DO_2") (pintype "bidirectional"))
      (node (ref "D14") (pin "4") (pinfunction "DI_4") (pintype "bidirectional"))
    )
    (net (code "72") (name "Net-(D14-DO)") (class "Default")
      (node (ref "D14") (pin "2") (pinfunction "DO_2") (pintype "bidirectional"))
      (node (ref "D15") (pin "4") (pinfunction "DI_4") (pintype "bidirectional"))
    )
    (net (code "73") (name "Net-(D15-DO)") (class "Default")
      (node (ref "D15") (pin "2") (pinfunction "DO_2") (pintype "bidirectional"))
      (node (ref "D16") (pin "4") (pinfunction "DI_4") (pintype "bidirectional"))
    )
    (net (code "74") (name "Net-(D16-DO)") (class "Default")
      (node (ref "D16") (pin "2") (pinfunction "DO_2") (pintype "bidirectional"))
      (node (ref "D17") (pin "4") (pinfunction "DI_4") (pintype "bidirectional"))
    )
    (net (code "75") (name "Net-(D17-DO)") (class "Default")
      (node (ref "D17") (pin "2") (pinfunction "DO_2") (pintype "bidirectional"))
      (node (ref "D18") (pin "4") (pinfunction "DI_4") (pintype "bidirectional"))
    )
    (net (code "76") (name "Net-(D18-DO)") (class "Default")
      (node (ref "D18") (pin "2") (pinfunction "DO_2") (pintype "bidirectional"))
      (node (ref "D19") (pin "4") (pinfunction "DI_4") (pintype "bidirectional"))
    )
    (net (code "77") (name "Net-(D19-DO)") (class "Default")
      (node (ref "D19") (pin "2") (pinfunction "DO_2") (pintype "bidirectional"))
      (node (ref "D20") (pin "4") (pinfunction "DI_4") (pintype "bidirectional"))
    )
    (net (code "78") (name "Net-(D20-DO)") (class "Default")
      (node (ref "D20") (pin "2") (pinfunction "DO_2") (pintype "bidirectional"))
      (node (ref "D21") (pin "4") (pinfunction "DI_4") (pintype "bidirectional"))
    )
    (net (code "79") (name "Net-(D21-DO)") (class "Default")
      (node (ref "D21") (pin "2") (pinfunction "DO_2") (pintype "bidirectional"))
      (node (ref "D22") (pin "4") (pinfunction "DI_4") (pintype "bidirectional"))
    )
    (net (code "80") (name "Net-(D22-DO)") (class "Default")
      (node (ref "D22") (pin "2") (pinfunction "DO_2") (pintype "bidirectional"))
      (node (ref "D23") (pin "4") (pinfunction "DI_4") (pintype "bidirectional"))
    )
    (net (code "81") (name "Net-(D23-DO)") (class "Default")
      (node (ref "D23") (pin "2") (pinfunction "DO_2") (pintype "bidirectional"))
      (node (ref "D24") (pin "4") (pinfunction "DI_4") (pintype "bidirectional"))
    )
    (net (code "82") (name "Net-(D24-DO)") (class "Default")
      (node (ref "D24") (pin "2") (pinfunction "DO_2") (pintype "bidirectional"))
      (node (ref "D25") (pin "4") (pinfunction "DI_4") (pintype "bidirectional"))
    )
    (net (code "83") (name "Net-(D25-DO)") (class "Default")
      (node (ref "D25") (pin "2") (pinfunction "DO_2") (pintype "bidirectional"))
      (node (ref "D26") (pin "4") (pinfunction "DI_4") (pintype "bidirectional"))
    )
    (net (code "84") (name "Net-(D26-DO)") (class "Default")
      (node (ref "D26") (pin "2") (pinfunction "DO_2") (pintype "bidirectional"))
      (node (ref "D27") (pin "4") (pinfunction "DI_4") (pintype "bidirectional"))
    )
    (net (code "85") (name "Net-(D27-DO)") (class "Default")
      (node (ref "D27") (pin "2") (pinfunction "DO_2") (pintype "bidirectional"))
      (node (ref "D28") (pin "4") (pinfunction "DI_4") (pintype "bidirectional"))
    )
    (net (code "86") (name "Net-(D28-DO)") (class "Default")
      (node (ref "D28") (pin "2") (pinfunction "DO_2") (pintype "bidirectional"))
      (node (ref "D29") (pin "4") (pinfunction "DI_4") (pintype "bidirectional"))
    )
    (net (code "87") (name "Net-(D29-DO)") (class "Default")
      (node (ref "D29") (pin "2") (pinfunction "DO_2") (pintype "bidirectional"))
      (node (ref "D30") (pin "4") (pinfunction "DI_4") (pintype "bidirectional"))
    )
    (net (code "88") (name "Net-(D30-DO)") (class "Default")
      (node (ref "D30") (pin "2") (pinfunction "DO_2") (pintype "bidirectional"))
      (node (ref "D31") (pin "4") (pinfunction "DI_4") (pintype "bidirectional"))
    )
    (net (code "89") (name "Net-(D31-DO)") (class "Default")
      (node (ref "D31") (pin "2") (pinfunction "DO_2") (pintype "bidirectional"))
      (node (ref "D32") (pin "4") (pinfunction "DI_4") (pintype "bidirectional"))
    )
    (net (code "90") (name "Net-(D32-DO)") (class "Default")
      (node (ref "D32") (pin "2") (pinfunction "DO_2") (pintype "bidirectional"))
      (node (ref "D33") (pin "4") (pinfunction "DI_4") (pintype "bidirectional"))
    )
    (net (code "91") (name "Net-(D33-DO)") (class "Default")
      (node (ref "D33") (pin "2") (pinfunction "DO_2") (pintype "bidirectional"))
      (node (ref "D34") (pin "4") (pinfunction "DI_4") (pintype "bidirectional"))
    )
    (net (code "92") (name "Net-(D34-DO)") (class "Default")
      (node (ref "D34") (pin "2") (pinfunction "DO_2") (pintype "bidirectional"))
      (node (ref "D35") (pin "4") (pinfunction "DI_4") (pintype "bidirectional"))
    )
    (net (code "93") (name "Net-(D35-DO)") (class "Default")
      (node (ref "D35") (pin "2") (pinfunction "DO_2") (pintype "bidirectional"))
      (node (ref "D36") (pin "4") (pinfunction "DI_4") (pintype "bidirectional"))
    )
    (net (code "94") (name "Net-(D36-DO)") (class "Default")
      (node (ref "D36") (pin "2") (pinfunction "DO_2") (pintype "bidirectional"))
      (node (ref "D37") (pin "4") (pinfunction "DI_4") (pintype "bidirectional"))
    )
    (net (code "95") (name "Net-(D37-DO)") (class "Default")
      (node (ref "D37") (pin "2") (pinfunction "DO_2") (pintype "bidirectional"))
      (node (ref "D38") (pin "4") (pinfunction "DI_4") (pintype "bidirectional"))
    )
    (net (code "96") (name "Net-(D38-DO)") (class "Default")
      (node (ref "D38") (pin "2") (pinfunction "DO_2") (pintype "bidirectional"))
      (node (ref "D39") (pin "4") (pinfunction "DI_4") (pintype "bidirectional"))
    )
    (net (code "97") (name "Net-(D39-DO)") (class "Default")
      (node (ref "D39") (pin "2") (pinfunction "DO_2") (pintype "bidirectional"))
      (node (ref "D40") (pin "4") (pinfunction "DI_4") (pintype "bidirectional"))
    )
    (net (code "98") (name "Net-(D40-DO)") (class "Default")
      (node (ref "D40") (pin "2") (pinfunction "DO_2") (pintype "bidirectional"))
      (node (ref "D41") (pin "4") (pinfunction "DI_4") (pintype "bidirectional"))
    )
    (net (code "99") (name "Net-(D41-DO)") (class "Default")
      (node (ref "D41") (pin "2") (pinfunction "DO_2") (pintype "bidirectional"))
      (node (ref "D42") (pin "4") (pinfunction "DI_4") (pintype "bidirectional"))
    )
    (net (code "100") (name "Net-(D42-DO)") (class "Default")
      (node (ref "D42") (pin "2") (pinfunction "DO_2") (pintype "bidirectional"))
      (node (ref "D43") (pin "4") (pinfunction "DI_4") (pintype "bidirectional"))
    )
    (net (code "101") (name "Net-(D43-DO)") (class "Default")
      (node (ref "D43") (pin "2") (pinfunction "DO_2") (pintype "bidirectional"))
      (node (ref "D44") (pin "4") (pinfunction "DI_4") (pintype "bidirectional"))
    )
    (net (code "102") (name "Net-(D44-DO)") (class "Default")
      (node (ref "D44") (pin "2") (pinfunction "DO_2") (pintype "bidirectional"))
      (node (ref "D45") (pin "4") (pinfunction "DI_4") (pintype "bidirectional"))
    )
    (net (code "103") (name "Net-(D45-DO)") (class "Default")
      (node (ref "D45") (pin "2") (pinfunction "DO_2") (pintype "bidirectional"))
      (node (ref "D46") (pin "4") (pinfunction "DI_4") (pintype "bidirectional"))
    )
    (net (code "104") (name "Net-(D46-DO)") (class "Default")
      (node (ref "D46") (pin "2") (pinfunction "DO_2") (pintype "bidirectional"))
      (node (ref "D47") (pin "4") (pinfunction "DI_4") (pintype "bidirectional"))
    )
    (net (code "105") (name "Net-(D47-DO)") (class "Default")
      (node (ref "D47") (pin "2") (pinfunction "DO_2") (pintype "bidirectional"))
      (node (ref "D48") (pin "4") (pinfunction "DI_4") (pintype "bidirectional"))
    )
    (net (code "106") (name "Net-(D48-DO)") (class "Default")
      (node (ref "D48") (pin "2") (pinfunction "DO_2") (pintype "bidirectional"))
      (node (ref "D49") (pin "4") (pinfunction "DI_4") (pintype "bidirectional"))
    )
    (net (code "107") (name "Net-(D49-DO)") (class "Default")
      (node (ref "D49") (pin "2") (pinfunction "DO_2") (pintype "bidirectional"))
      (node (ref "D50") (pin "4") (pinfunction "DI_4") (pintype "bidirectional"))
    )
    (net (code "108") (name "Net-(D50-DO)") (class "Default")
      (node (ref "D50") (pin "2") (pinfunction "DO_2") (pintype "bidirectional"))
      (node (ref "D51") (pin "4") (pinfunction "DI_4") (pintype "bidirectional"))
    )
    (net (code "109") (name "Net-(D51-DO)") (class "Default")
      (node (ref "D51") (pin "2") (pinfunction "DO_2") (pintype "bidirectional"))
      (node (ref "D52") (pin "4") (pinfunction "DI_4") (pintype "bidirectional"))
    )
    (net (code "110") (name "Net-(D52-DO)") (class "Default")
      (node (ref "D52") (pin "2") (pinfunction "DO_2") (pintype "bidirectional"))
      (node (ref "D53") (pin "4") (pinfunction "DI_4") (pintype "bidirectional"))
    )
    (net (code "111") (name "Net-(D53-DO)") (class "Default")
      (node (ref "D53") (pin "2") (pinfunction "DO_2") (pintype "bidirectional"))
      (node (ref "D54") (pin "4") (pinfunction "DI_4") (pintype "bidirectional"))
    )
    (net (code "112") (name "Net-(D54-DO)") (class "Default")
      (node (ref "D54") (pin "2") (pinfunction "DO_2") (pintype "bidirectional"))
      (node (ref "D55") (pin "4") (pinfunction "DI_4") (pintype "bidirectional"))
    )
    (net (code "113") (name "Net-(D55-DO)") (class "Default")
      (node (ref "D55") (pin "2") (pinfunction "DO_2") (pintype "bidirectional"))
      (node (ref "D56") (pin "4") (pinfunction "DI_4") (pintype "bidirectional"))
    )
    (net (code "114") (name "Net-(D56-DO)") (class "Default")
      (node (ref "D56") (pin "2") (pinfunction "DO_2") (pintype "bidirectional"))
      (node (ref "D57") (pin "4") (pinfunction "DI_4") (pintype "bidirectional"))
    )
    (net (code "115") (name "Net-(D57-DO)") (class "Default")
      (node (ref "D57") (pin "2") (pinfunction "DO_2") (pintype "bidirectional"))
      (node (ref "D58") (pin "4") (pinfunction "DI_4") (pintype "bidirectional"))
    )
    (net (code "116") (name "Net-(D58-DO)") (class "Default")
      (node (ref "D58") (pin "2") (pinfunction "DO_2") (pintype "bidirectional"))
      (node (ref "D59") (pin "4") (pinfunction "DI_4") (pintype "bidirectional"))
    )
    (net (code "117") (name "Net-(D59-DO)") (class "Default")
      (node (ref "D59") (pin "2") (pinfunction "DO_2") (pintype "bidirectional"))
      (node (ref "D60") (pin "4") (pinfunction "DI_4") (pintype "bidirectional"))
    )
    (net (code "118") (name "Net-(D60-DO)") (class "Default")
      (node (ref "D60") (pin "2") (pinfunction "DO_2") (pintype "bidirectional"))
      (node (ref "D61") (pin "4") (pinfunction "DI_4") (pintype "bidirectional"))
    )
    (net (code "119") (name "Net-(D61-DO)") (class "Default")
      (node (ref "D61") (pin "2") (pinfunction "DO_2") (pintype "bidirectional"))
      (node (ref "D62") (pin "4") (pinfunction "DI_4") (pintype "bidirectional"))
    )
    (net (code "120") (name "Net-(D62-DO)") (class "Default")
      (node (ref "D62") (pin "2") (pinfunction "DO_2") (pintype "bidirectional"))
      (node (ref "D63") (pin "4") (pinfunction "DI_4") (pintype "bidirectional"))
    )
    (net (code "121") (name "Net-(D63-DO)") (class "Default")
      (node (ref "D63") (pin "2") (pinfunction "DO_2") (pintype "bidirectional"))
      (node (ref "D64") (pin "4") (pinfunction "DI_4") (pintype "bidirectional"))
    )
    (net (code "122") (name "Net-(D64-DO)") (class "Default")
      (node (ref "D64") (pin "2") (pinfunction "DO_2") (pintype "bidirectional"))
      (node (ref "D65") (pin "4") (pinfunction "DI_4") (pintype "bidirectional"))
    )
    (net (code "123") (name "Net-(D65-DO)") (class "Default")
      (node (ref "D65") (pin "2") (pinfunction "DO_2") (pintype "bidirectional"))
      (node (ref "D66") (pin "4") (pinfunction "DI_4") (pintype "bidirectional"))
    )
    (net (code "124") (name "Net-(D66-DO)") (class "Default")
      (node (ref "D66") (pin "2") (pinfunction "DO_2") (pintype "bidirectional"))
      (node (ref "D67") (pin "4") (pinfunction "DI_4") (pintype "bidirectional"))
    )
    (net (code "125") (name "Net-(D67-DO)") (class "Default")
      (node (ref "D67") (pin "2") (pinfunction "DO_2") (pintype "bidirectional"))
      (node (ref "D68") (pin "4") (pinfunction "DI_4") (pintype "bidirectional"))
    )
    (net (code "126") (name "Net-(D68-DO)") (class "Default")
      (node (ref "D68") (pin "2") (pinfunction "DO_2") (pintype "bidirectional"))
      (node (ref "D69") (pin "4") (pinfunction "DI_4") (pintype "bidirectional"))
    )
    (net (code "127") (name "Net-(D69-DO)") (class "Default")
      (node (ref "D69") (pin "2") (pinfunction "DO_2") (pintype "bidirectional"))
      (node (ref "D70") (pin "4") (pinfunction "DI_4") (pintype "bidirectional"))
    )
    (net (code "128") (name "Net-(D70-DO)") (class "Default")
      (node (ref "D70") (pin "2") (pinfunction "DO_2") (pintype "bidirectional"))
      (node (ref "D71") (pin "4") (pinfunction "DI_4") (pintype "bidirectional"))
    )
    (net (code "129") (name "Net-(D71-DO)") (class "Default")
      (node (ref "D71") (pin "2") (pinfunction "DO_2") (pintype "bidirectional"))
      (node (ref "D72") (pin "4") (pinfunction "DI_4") (pintype "bidirectional"))
    )
    (net (code "130") (name "Net-(D72-DO)") (class "Default")
      (node (ref "D72") (pin "2") (pinfunction "DO_2") (pintype "bidirectional"))
      (node (ref "D73") (pin "4") (pinfunction "DI_4") (pintype "bidirectional"))
    )
    (net (code "131") (name "Net-(D73-DO)") (class "Default")
      (node (ref "D73") (pin "2") (pinfunction "DO_2") (pintype "bidirectional"))
      (node (ref "D74") (pin "4") (pinfunction "DI_4") (pintype "bidirectional"))
    )
    (net (code "132") (name "Net-(D74-DO)") (class "Default")
      (node (ref "D74") (pin "2") (pinfunction "DO_2") (pintype "bidirectional"))
      (node (ref "D75") (pin "4") (pinfunction "DI_4") (pintype "bidirectional"))
    )
    (net (code "133") (name "Net-(D75-DO)") (class "Default")
      (node (ref "D75") (pin "2") (pinfunction "DO_2") (pintype "bidirectional"))
      (node (ref "D76") (pin "4") (pinfunction "DI_4") (pintype "bidirectional"))
    )
    (net (code "134") (name "Net-(D76-DO)") (class "Default")
      (node (ref "D76") (pin "2") (pinfunction "DO_2") (pintype "bidirectional"))
      (node (ref "D77") (pin "4") (pinfunction "DI_4") (pintype "bidirectional"))
    )
    (net (code "135") (name "Net-(D77-DO)") (class "Default")
      (node (ref "D77") (pin "2") (pinfunction "DO_2") (pintype "bidirectional"))
      (node (ref "D78") (pin "4") (pinfunction "DI_4") (pintype "bidirectional"))
    )
    (net (code "136") (name "Net-(D78-DO)") (class "Default")
      (node (ref "D78") (pin "2") (pinfunction "DO_2") (pintype "bidirectional"))
      (node (ref "D79") (pin "4") (pinfunction "DI_4") (pintype "bidirectional"))
    )
    (net (code "137") (name "Net-(D79-DO)") (class "Default")
      (node (ref "D79") (pin "2") (pinfunction "DO_2") (pintype "bidirectional"))
      (node (ref "D80") (pin "4") (pinfunction "DI_4") (pintype "bidirectional"))
    )
    (net (code "138") (name "Net-(D80-DO)") (class "Default")
      (node (ref "D80") (pin "2") (pinfunction "DO_2") (pintype "bidirectional"))
      (node (ref "D81") (pin "4") (pinfunction "DI_4") (pintype "bidirectional"))
    )
    (net (code "139") (name "Net-(D81-DO)") (class "Default")
      (node (ref "D81") (pin "2") (pinfunction "DO_2") (pintype "bidirectional"))
      (node (ref "D82") (pin "4") (pinfunction "DI_4") (pintype "bidirectional"))
    )
    (net (code "140") (name "Net-(D82-DO)") (class "Default")
      (node (ref "D82") (pin "2") (pinfunction "DO_2") (pintype "bidirectional"))
      (node (ref "D83") (pin "4") (pinfunction "DI_4") (pintype "bidirectional"))
    )
    (net (code "141") (name "Net-(D83-DO)") (class "Default")
      (node (ref "D83") (pin "2") (pinfunction "DO_2") (pintype "bidirectional"))
      (node (ref "D84") (pin "4") (pinfunction "DI_4") (pintype "bidirectional"))
    )
    (net (code "142") (name "Net-(D84-DO)") (class "Default")
      (node (ref "D84") (pin "2") (pinfunction "DO_2") (pintype "bidirectional"))
      (node (ref "D85") (pin "4") (pinfunction "DI_4") (pintype "bidirectional"))
    )
    (net (code "143") (name "Net-(D85-DO)") (class "Default")
      (node (ref "D85") (pin "2") (pinfunction "DO_2") (pintype "bidirectional"))
      (node (ref "D86") (pin "4") (pinfunction "DI_4") (pintype "bidirectional"))
    )
    (net (code "144") (name "Net-(D86-DO)") (class "Default")
      (node (ref "D86") (pin "2") (pinfunction "DO_2") (pintype "bidirectional"))
      (node (ref "D87") (pin "4") (pinfunction "DI_4") (pintype "bidirectional"))
    )
    (net (code "145") (name "Net-(D87-DO)") (class "Default")
      (node (ref "D87") (pin "2") (pinfunction "DO_2") (pintype "bidirectional"))
      (node (ref "D88") (pin "4") (pinfunction "DI_4") (pintype "bidirectional"))
    )
    (net (code "146") (name "Net-(D88-DO)") (class "Default")
      (node (ref "D88") (pin "2") (pinfunction "DO_2") (pintype "bidirectional"))
      (node (ref "D89") (pin "4") (pinfunction "DI_4") (pintype "bidirectional"))
    )
    (net (code "147") (name "Net-(D89-DO)") (class "Default")
      (node (ref "D89") (pin "2") (pinfunction "DO_2") (pintype "bidirectional"))
      (node (ref "D90") (pin "4") (pinfunction "DI_4") (pintype "bidirectional"))
    )
    (net (code "148") (name "Net-(D90-DO)") (class "Default")
      (node (ref "D90") (pin "2") (pinfunction "DO_2") (pintype "bidirectional"))
      (node (ref "D91") (pin "4") (pinfunction "DI_4") (pintype "bidirectional"))
    )
    (net (code "149") (name "Net-(D91-DO)") (class "Default")
      (node (ref "D91") (pin "2") (pinfunction "DO_2") (pintype "bidirectional"))
      (node (ref "D92") (pin "4") (pinfunction "DI_4") (pintype "bidirectional"))
    )
    (net (code "150") (name "Net-(D92-DO)") (class "Default")
      (node (ref "D92") (pin "2") (pinfunction "DO_2") (pintype "bidirectional"))
      (node (ref "D93") (pin "4") (pinfunction "DI_4") (pintype "bidirectional"))
    )
    (net (code "151") (name "Net-(D93-DO)") (class "Default")
      (node (ref "D93") (pin "2") (pinfunction "DO_2") (pintype "bidirectional"))
      (node (ref "D94") (pin "4") (pinfunction "DI_4") (pintype "bidirectional"))
    )
    (net (code "152") (name "Net-(D94-DO)") (class "Default")
      (node (ref "D94") (pin "2") (pinfunction "DO_2") (pintype "bidirectional"))
      (node (ref "D95") (pin "4") (pinfunction "DI_4") (pintype "bidirectional"))
    )
    (net (code "153") (name "Net-(D95-DO)") (class "Default")
      (node (ref "D95") (pin "2") (pinfunction "DO_2") (pintype "bidirectional"))
      (node (ref "D96") (pin "4") (pinfunction "DI_4") (pintype "bidirectional"))
    )
    (net (code "154") (name "Net-(D96-DO)") (class "Default")
      (node (ref "D96") (pin "2") (pinfunction "DO_2") (pintype "bidirectional"))
      (node (ref "D97") (pin "4") (pinfunction "DI_4") (pintype "bidirectional"))
    )
    (net (code "155") (name "Net-(D97-DO)") (class "Default")
      (node (ref "D97") (pin "2") (pinfunction "DO_2") (pintype "bidirectional"))
      (node (ref "D98") (pin "4") (pinfunction "DI_4") (pintype "bidirectional"))
    )
    (net (code "156") (name "Net-(D98-DO)") (class "Default")
      (node (ref "D98") (pin "2") (pinfunction "DO_2") (pintype "bidirectional"))
      (node (ref "D99") (pin "4") (pinfunction "DI_4") (pintype "bidirectional"))
    )
    (net (code "157") (name "Net-(D100-DI)") (class "Default")
      (node (ref "D100") (pin "4") (pinfunction "DI_4") (pintype "bidirectional"))
      (node (ref "D99") (pin "2") (pinfunction "DO_2") (pintype "bidirectional"))
    )
    (net (code "158") (name "Net-(D100-DO)") (class "Default")
      (node (ref "D100") (pin "2") (pinfunction "DO_2") (pintype "bidirectional"))
      (node (ref "D101") (pin "4") (pinfunction "DI_4") (pintype "bidirectional"))
    )
    (net (code "159") (name "Net-(D101-DO)") (class "Default")
      (node (ref "D101") (pin "2") (pinfunction "DO_2") (pintype "bidirectional"))
      (node (ref "D102") (pin "4") (pinfunction "DI_4") (pintype "bidirectional"))
    )
    (net (code "160") (name "Net-(D102-DO)") (class "Default")
      (node (ref "D102") (pin "2") (pinfunction "DO_2") (pintype "bidirectional"))
      (node (ref "D103") (pin "4") (pinfunction "DI_4") (pintype "bidirectional"))
    )
    (net (code "161") (name "Net-(D103-DO)") (class "Default")
      (node (ref "D103") (pin "2") (pinfunction "DO_2") (pintype "bidirectional"))
      (node (ref "D104") (pin "4") (pinfunction "DI_4") (pintype "bidirectional"))
    )
    (net (code "162") (name "Net-(D104-DO)") (class "Default")
      (node (ref "D104") (pin "2") (pinfunction "DO_2") (pintype "bidirectional"))
      (node (ref "D105") (pin "4") (pinfunction "DI_4") (pintype "bidirectional"))
    )
    (net (code "163") (name "Net-(D105-DO)") (class "Default")
      (node (ref "D105") (pin "2") (pinfunction "DO_2") (pintype "bidirectional"))
      (node (ref "D106") (pin "4") (pinfunction "DI_4") (pintype "bidirectional"))
    )
    (net (code "164") (name "Net-(D106-DO)") (class "Default")
      (node (ref "D106") (pin "2") (pinfunction "DO_2") (pintype "bidirectional"))
      (node (ref "D107") (pin "4") (pinfunction "DI_4") (pintype "bidirectional"))
    )
    (net (code "165") (name "Net-(D107-DO)") (class "Default")
      (node (ref "D107") (pin "2") (pinfunction "DO_2") (pintype "bidirectional"))
      (node (ref "D108") (pin "4") (pinfunction "DI_4") (pintype "bidirectional"))
    )
    (net (code "166") (name "Net-(D108-DO)") (class "Default")
      (node (ref "D108") (pin "2") (pinfunction "DO_2") (pintype "bidirectional"))
      (node (ref "D109") (pin "4") (pinfunction "DI_4") (pintype "bidirectional"))
    )
    (net (code "167") (name "Net-(D109-DO)") (class "Default")
      (node (ref "D109") (pin "2") (pinfunction "DO_2") (pintype "bidirectional"))
      (node (ref "D110") (pin "4") (pinfunction "DI_4") (pintype "bidirectional"))
    )
    (net (code "168") (name "Net-(D110-DO)") (class "Default")
      (node (ref "D110") (pin "2") (pinfunction "DO_2") (pintype "bidirectional"))
      (node (ref "D111") (pin "4") (pinfunction "DI_4") (pintype "bidirectional"))
    )
    (net (code "169") (name "Net-(D111-DO)") (class "Default")
      (node (ref "D111") (pin "2") (pinfunction "DO_2") (pintype "bidirectional"))
      (node (ref "D112") (pin "4") (pinfunction "DI_4") (pintype "bidirectional"))
    )
    (net (code "170") (name "Net-(D112-DO)") (class "Default")
      (node (ref "D112") (pin "2") (pinfunction "DO_2") (pintype "bidirectional"))
      (node (ref "D113") (pin "4") (pinfunction "DI_4") (pintype "bidirectional"))
    )
    (net (code "171") (name "Net-(D113-DO)") (class "Default")
      (node (ref "D113") (pin "2") (pinfunction "DO_2") (pintype "bidirectional"))
      (node (ref "D114") (pin "4") (pinfunction "DI_4") (pintype "bidirectional"))
    )
    (net (code "172") (name "Net-(D114-DO)") (class "Default")
      (node (ref "D114") (pin "2") (pinfunction "DO_2") (pintype "bidirectional"))
      (node (ref "D115") (pin "4") (pinfunction "DI_4") (pintype "bidirectional"))
    )
    (net (code "173") (name "Net-(D115-DO)") (class "Default")
      (node (ref "D115") (pin "2") (pinfunction "DO_2") (pintype "bidirectional"))
      (node (ref "D116") (pin "4") (pinfunction "DI_4") (pintype "bidirectional"))
    )
    (net (code "174") (name "Net-(D116-DO)") (class "Default")
      (node (ref "D116") (pin "2") (pinfunction "DO_2") (pintype "bidirectional"))
      (node (ref "D117") (pin "4") (pinfunction "DI_4") (pintype "bidirectional"))
    )
    (net (code "175") (name "Net-(D117-DO)") (class "Default")
      (node (ref "D117") (pin "2") (pinfunction "DO_2") (pintype "bidirectional"))
      (node (ref "D118") (pin "4") (pinfunction "DI_4") (pintype "bidirectional"))
    )
    (net (code "176") (name "Net-(D118-DO)") (class "Default")
      (node (ref "D118") (pin "2") (pinfunction "DO_2") (pintype "bidirectional"))
      (node (ref "D119") (pin "4") (pinfunction "DI_4") (pintype "bidirectional"))
    )
    (net (code "177") (name "Net-(D119-DO)") (class "Default")
      (node (ref "D119") (pin "2") (pinfunction "DO_2") (pintype "bidirectional"))
      (node (ref "D120") (pin "4") (pinfunction "DI_4") (pintype "bidirectional"))
    )
    (net (code "178") (name "Net-(D120-DO)") (class "Default")
      (node (ref "D120") (pin "2") (pinfunction "DO_2") (pintype "bidirectional"))
      (node (ref "D121") (pin "4") (pinfunction "DI_4") (pintype "bidirectional"))
    )
    (net (code "179") (name "Net-(D121-DO)") (class "Default")
      (node (ref "D121") (pin "2") (pinfunction "DO_2") (pintype "bidirectional"))
      (node (ref "D122") (pin "4") (pinfunction "DI_4") (pintype "bidirectional"))
    )
    (net (code "180") (name "Net-(D122-DO)") (class "Default")
      (node (ref "D122") (pin "2") (pinfunction "DO_2") (pintype "bidirectional"))
      (node (ref "D123") (pin "4") (pinfunction "DI_4") (pintype "bidirectional"))
    )
    (net (code "181") (name "Net-(D123-DO)") (class "Default")
      (node (ref "D123") (pin "2") (pinfunction "DO_2") (pintype "bidirectional"))
      (node (ref "D124") (pin "4") (pinfunction "DI_4") (pintype "bidirectional"))
    )
    (net (code "182") (name "Net-(D124-DO)") (class "Default")
      (node (ref "D124") (pin "2") (pinfunction "DO_2") (pintype "bidirectional"))
      (node (ref "D125") (pin "4") (pinfunction "DI_4") (pintype "bidirectional"))
    )
    (net (code "183") (name "Net-(D125-DO)") (class "Default")
      (node (ref "D125") (pin "2") (pinfunction "DO_2") (pintype "bidirectional"))
      (node (ref "D126") (pin "4") (pinfunction "DI_4") (pintype "bidirectional"))
    )
    (net (code "184") (name "Net-(D126-DO)") (class "Default")
      (node (ref "D126") (pin "2") (pinfunction "DO_2") (pintype "bidirectional"))
      (node (ref "D127") (pin "4") (pinfunction "DI_4") (pintype "bidirectional"))
    )
    (net (code "185") (name "Net-(D127-DO)") (class "Default")
      (node (ref "D127") (pin "2") (pinfunction "DO_2") (pintype "bidirectional"))
      (node (ref "D128") (pin "4") (pinfunction "DI_4") (pintype "bidirectional"))
    )
    (net (code "186") (name "Net-(D128-DO)") (class "Default")
      (node (ref "D128") (pin "2") (pinfunction "DO_2") (pintype "bidirectional"))
      (node (ref "D129") (pin "4") (pinfunction "DI_4") (pintype "bidirectional"))
    )
    (net (code "187") (name "Net-(D129-DO)") (class "Default")
      (node (ref "D129") (pin "2") (pinfunction "DO_2") (pintype "bidirectional"))
      (node (ref "D130") (pin "4") (pinfunction "DI_4") (pintype "bidirectional"))
    )
    (net (code "188") (name "Net-(D130-DO)") (class "Default")
      (node (ref "D130") (pin "2") (pinfunction "DO_2") (pintype "bidirectional"))
      (node (ref "D131") (pin "4") (pinfunction "DI_4") (pintype "bidirectional"))
    )
    (net (code "189") (name "Net-(D131-DO)") (class "Default")
      (node (ref "D131") (pin "2") (pinfunction "DO_2") (pintype "bidirectional"))
      (node (ref "D132") (pin "4") (pinfunction "DI_4") (pintype "bidirectional"))
    )
    (net (code "190") (name "Net-(D132-DO)") (class "Default")
      (node (ref "D132") (pin "2") (pinfunction "DO_2") (pintype "bidirectional"))
      (node (ref "D133") (pin "4") (pinfunction "DI_4") (pintype "bidirectional"))
    )
    (net (code "191") (name "Net-(D133-DO)") (class "Default")
      (node (ref "D133") (pin "2") (pinfunction "DO_2") (pintype "bidirectional"))
      (node (ref "D134") (pin "4") (pinfunction "DI_4") (pintype "bidirectional"))
    )
    (net (code "192") (name "Net-(D134-DO)") (class "Default")
      (node (ref "D134") (pin "2") (pinfunction "DO_2") (pintype "bidirectional"))
      (node (ref "D135") (pin "4") (pinfunction "DI_4") (pintype "bidirectional"))
    )
    (net (code "193") (name "Net-(D135-DO)") (class "Default")
      (node (ref "D135") (pin "2") (pinfunction "DO_2") (pintype "bidirectional"))
      (node (ref "D136") (pin "4") (pinfunction "DI_4") (pintype "bidirectional"))
    )
    (net (code "194") (name "Net-(D136-DO)") (class "Default")
      (node (ref "D136") (pin "2") (pinfunction "DO_2") (pintype "bidirectional"))
      (node (ref "D137") (pin "4") (pinfunction "DI_4") (pintype "bidirectional"))
    )
    (net (code "195") (name "Net-(D137-DO)") (class "Default")
      (node (ref "D137") (pin "2") (pinfunction "DO_2") (pintype "bidirectional"))
      (node (ref "D138") (pin "4") (pinfunction "DI_4") (pintype "bidirectional"))
    )
    (net (code "196") (name "Net-(D138-DO)") (class "Default")
      (node (ref "D138") (pin "2") (pinfunction "DO_2") (pintype "bidirectional"))
      (node (ref "D139") (pin "4") (pinfunction "DI_4") (pintype "bidirectional"))
    )
    (net (code "197") (name "Net-(D139-DO)") (class "Default")
      (node (ref "D139") (pin "2") (pinfunction "DO_2") (pintype "bidirectional"))
      (node (ref "D140") (pin "4") (pinfunction "DI_4") (pintype "bidirectional"))
    )
    (net (code "198") (name "Net-(D140-DO)") (class "Default")
      (node (ref "D140") (pin "2") (pinfunction "DO_2") (pintype "bidirectional"))
      (node (ref "D141") (pin "4") (pinfunction "DI_4") (pintype "bidirectional"))
    )
    (net (code "199") (name "Net-(D141-DO)") (class "Default")
      (node (ref "D141") (pin "2") (pinfunction "DO_2") (pintype "bidirectional"))
      (node (ref "D142") (pin "4") (pinfunction "DI_4") (pintype "bidirectional"))
    )
    (net (code "200") (name "Net-(D142-DO)") (class "Default")
      (node (ref "D142") (pin "2") (pinfunction "DO_2") (pintype "bidirectional"))
      (node (ref "D143") (pin "4") (pinfunction "DI_4") (pintype "bidirectional"))
    )
    (net (code "201") (name "Net-(D143-DO)") (class "Default")
      (node (ref "D143") (pin "2") (pinfunction "DO_2") (pintype "bidirectional"))
      (node (ref "D144") (pin "4") (pinfunction "DI_4") (pintype "bidirectional"))
    )
    (net (code "202") (name "Net-(D144-DO)") (class "Default")
      (node (ref "D144") (pin "2") (pinfunction "DO_2") (pintype "bidirectional"))
      (node (ref "D145") (pin "4") (pinfunction "DI_4") (pintype "bidirectional"))
    )
    (net (code "203") (name "Net-(D145-DO)") (class "Default")
      (node (ref "D145") (pin "2") (pinfunction "DO_2") (pintype "bidirectional"))
      (node (ref "D146") (pin "4") (pinfunction "DI_4") (pintype "bidirectional"))
    )
    (net (code "204") (name "Net-(D146-DO)") (class "Default")
      (node (ref "D146") (pin "2") (pinfunction "DO_2") (pintype "bidirectional"))
      (node (ref "D147") (pin "4") (pinfunction "DI_4") (pintype "bidirectional"))
    )
    (net (code "205") (name "Net-(D147-DO)") (class "Default")
      (node (ref "D147") (pin "2") (pinfunction "DO_2") (pintype "bidirectional"))
      (node (ref "D148") (pin "4") (pinfunction "DI_4") (pintype "bidirectional"))
    )
    (net (code "206") (name "Net-(D148-DO)") (class "Default")
      (node (ref "D148") (pin "2") (pinfunction "DO_2") (pintype "bidirectional"))
      (node (ref "D149") (pin "4") (pinfunction "DI_4") (pintype "bidirectional"))
    )
    (net (code "207") (name "Net-(D149-DO)") (class "Default")
      (node (ref "D149") (pin "2") (pinfunction "DO_2") (pintype "bidirectional"))
      (node (ref "D150") (pin "4") (pinfunction "DI_4") (pintype "bidirectional"))
    )
    (net (code "208") (name "Net-(D150-DO)") (class "Default")
      (node (ref "D150") (pin "2") (pinfunction "DO_2") (pintype "bidirectional"))
      (node (ref "D151") (pin "4") (pinfunction "DI_4") (pintype "bidirectional"))
    )
    (net (code "209") (name "Net-(D151-DO)") (class "Default")
      (node (ref "D151") (pin "2") (pinfunction "DO_2") (pintype "bidirectional"))
      (node (ref "D152") (pin "4") (pinfunction "DI_4") (pintype "bidirectional"))
    )
    (net (code "210") (name "Net-(D152-DO)") (class "Default")
      (node (ref "D152") (pin "2") (pinfunction "DO_2") (pintype "bidirectional"))
      (node (ref "D153") (pin "4") (pinfunction "DI_4") (pintype "bidirectional"))
    )
    (net (code "211") (name "Net-(D153-DO)") (class "Default")
      (node (ref "D153") (pin "2") (pinfunction "DO_2") (pintype "bidirectional"))
      (node (ref "D154") (pin "4") (pinfunction "DI_4") (pintype "bidirectional"))
    )
    (net (code "212") (name "Net-(D154-DO)") (class "Default")
      (node (ref "D154") (pin "2") (pinfunction "DO_2") (pintype "bidirectional"))
      (node (ref "D155") (pin "4") (pinfunction "DI_4") (pintype "bidirectional"))
    )
    (net (code "213") (name "Net-(D155-DO)") (class "Default")
      (node (ref "D155") (pin "2") (pinfunction "DO_2") (pintype "bidirectional"))
      (node (ref "D156") (pin "4") (pinfunction "DI_4") (pintype "bidirectional"))
    )
    (net (code "214") (name "Net-(D156-DO)") (class "Default")
      (node (ref "D156") (pin "2") (pinfunction "DO_2") (pintype "bidirectional"))
      (node (ref "D157") (pin "4") (pinfunction "DI_4") (pintype "bidirectional"))
    )
    (net (code "215") (name "Net-(D157-DO)") (class "Default")
      (node (ref "D157") (pin "2") (pinfunction "DO_2") (pintype "bidirectional"))
      (node (ref "D158") (pin "4") (pinfunction "DI_4") (pintype "bidirectional"))
    )
    (net (code "216") (name "Net-(D158-DO)") (class "Default")
      (node (ref "D158") (pin "2") (pinfunction "DO_2") (pintype "bidirectional"))
      (node (ref "D159") (pin "4") (pinfunction "DI_4") (pintype "bidirectional"))
    )
    (net (code "217") (name "Net-(D159-DO)") (class "Default")
      (node (ref "D159") (pin "2") (pinfunction "DO_2") (pintype "bidirectional"))
      (node (ref "D160") (pin "4") (pinfunction "DI_4") (pintype "bidirectional"))
    )
    (net (code "218") (name "Net-(D160-DO)") (class "Default")
      (node (ref "D160") (pin "2") (pinfunction "DO_2") (pintype "bidirectional"))
      (node (ref "D161") (pin "4") (pinfunction "DI_4") (pintype "bidirectional"))
    )
    (net (code "219") (name "Net-(D161-DO)") (class "Default")
      (node (ref "D161") (pin "2") (pinfunction "DO_2") (pintype "bidirectional"))
      (node (ref "D162") (pin "4") (pinfunction "DI_4") (pintype "bidirectional"))
    )
    (net (code "220") (name "Net-(D162-DO)") (class "Default")
      (node (ref "D162") (pin "2") (pinfunction "DO_2") (pintype "bidirectional"))
      (node (ref "D163") (pin "4") (pinfunction "DI_4") (pintype "bidirectional"))
    )
    (net (code "221") (name "Net-(D163-DO)") (class "Default")
      (node (ref "D163") (pin "2") (pinfunction "DO_2") (pintype "bidirectional"))
      (node (ref "D164") (pin "4") (pinfunction "DI_4") (pintype "bidirectional"))
    )
    (net (code "222") (name "Net-(D164-DO)") (class "Default")
      (node (ref "D164") (pin "2") (pinfunction "DO_2") (pintype "bidirectional"))
      (node (ref "D165") (pin "4") (pinfunction "DI_4") (pintype "bidirectional"))
    )
    (net (code "223") (name "Net-(D165-DO)") (class "Default")
      (node (ref "D165") (pin "2") (pinfunction "DO_2") (pintype "bidirectional"))
      (node (ref "D166") (pin "4") (pinfunction "DI_4") (pintype "bidirectional"))
    )
    (net (code "224") (name "Net-(D166-DO)") (class "Default")
      (node (ref "D166") (pin "2") (pinfunction "DO_2") (pintype "bidirectional"))
      (node (ref "D167") (pin "4") (pinfunction "DI_4") (pintype "bidirectional"))
    )
    (net (code "225") (name "Net-(D167-DO)") (class "Default")
      (node (ref "D167") (pin "2") (pinfunction "DO_2") (pintype "bidirectional"))
      (node (ref "D168") (pin "4") (pinfunction "DI_4") (pintype "bidirectional"))
    )
    (net (code "226") (name "Net-(D168-DO)") (class "Default")
      (node (ref "D168") (pin "2") (pinfunction "DO_2") (pintype "bidirectional"))
      (node (ref "D169") (pin "4") (pinfunction "DI_4") (pintype "bidirectional"))
    )
    (net (code "227") (name "Net-(D169-DO)") (class "Default")
      (node (ref "D169") (pin "2") (pinfunction "DO_2") (pintype "bidirectional"))
      (node (ref "D170") (pin "4") (pinfunction "DI_4") (pintype "bidirectional"))
    )
    (net (code "228") (name "Net-(D170-DO)") (class "Default")
      (node (ref "D170") (pin "2") (pinfunction "DO_2") (pintype "bidirectional"))
      (node (ref "D171") (pin "4") (pinfunction "DI_4") (pintype "bidirectional"))
    )
    (net (code "229") (name "Net-(D171-DO)") (class "Default")
      (node (ref "D171") (pin "2") (pinfunction "DO_2") (pintype "bidirectional"))
      (node (ref "D172") (pin "4") (pinfunction "DI_4") (pintype "bidirectional"))
    )
    (net (code "230") (name "Net-(D172-DO)") (class "Default")
      (node (ref "D172") (pin "2") (pinfunction "DO_2") (pintype "bidirectional"))
      (node (ref "D173") (pin "4") (pinfunction "DI_4") (pintype "bidirectional"))
    )
    (net (code "231") (name "Net-(D173-DO)") (class "Default")
      (node (ref "D173") (pin "2") (pinfunction "DO_2") (pintype "bidirectional"))
      (node (ref "D174") (pin "4") (pinfunction "DI_4") (pintype "bidirectional"))
    )
    (net (code "232") (name "Net-(D174-DO)") (class "Default")
      (node (ref "D174") (pin "2") (pinfunction "DO_2") (pintype "bidirectional"))
      (node (ref "D175") (pin "4") (pinfunction "DI_4") (pintype "bidirectional"))
    )
    (net (code "233") (name "Net-(D175-DO)") (class "Default")
      (node (ref "D175") (pin "2") (pinfunction "DO_2") (pintype "bidirectional"))
      (node (ref "D176") (pin "4") (pinfunction "DI_4") (pintype "bidirectional"))
    )
    (net (code "234") (name "Net-(D176-DO)") (class "Default")
      (node (ref "D176") (pin "2") (pinfunction "DO_2") (pintype "bidirectional"))
      (node (ref "D177") (pin "4") (pinfunction "DI_4") (pintype "bidirectional"))
    )
    (net (code "235") (name "Net-(D177-DO)") (class "Default")
      (node (ref "D177") (pin "2") (pinfunction "DO_2") (pintype "bidirectional"))
      (node (ref "D178") (pin "4") (pinfunction "DI_4") (pintype "bidirectional"))
    )
    (net (code "236") (name "Net-(D178-DO)") (class "Default")
      (node (ref "D178") (pin "2") (pinfunction "DO_2") (pintype "bidirectional"))
      (node (ref "D179") (pin "4") (pinfunction "DI_4") (pintype "bidirectional"))
    )
    (net (code "237") (name "Net-(D179-DO)") (class "Default")
      (node (ref "D179") (pin "2") (pinfunction "DO_2") (pintype "bidirectional"))
      (node (ref "D180") (pin "4") (pinfunction "DI_4") (pintype "bidirectional"))
    )
    (net (code "238") (name "Net-(D180-DO)") (class "Default")
      (node (ref "D180") (pin "2") (pinfunction "DO_2") (pintype "bidirectional"))
      (node (ref "D181") (pin "4") (pinfunction "DI_4") (pintype "bidirectional"))
    )
    (net (code "239") (name "Net-(D181-DO)") (class "Default")
      (node (ref "D181") (pin "2") (pinfunction "DO_2") (pintype "bidirectional"))
      (node (ref "D182") (pin "4") (pinfunction "DI_4") (pintype "bidirectional"))
    )
    (net (code "240") (name "Net-(D182-DO)") (class "Default")
      (node (ref "D182") (pin "2") (pinfunction "DO_2") (pintype "bidirectional"))
      (node (ref "D183") (pin "4") (pinfunction "DI_4") (pintype "bidirectional"))
    )
    (net (code "241") (name "Net-(D183-DO)") (class "Default")
      (node (ref "D183") (pin "2") (pinfunction "DO_2") (pintype "bidirectional"))
      (node (ref "D184") (pin "4") (pinfunction "DI_4") (pintype "bidirectional"))
    )
    (net (code "242") (name "Net-(D184-DO)") (class "Default")
      (node (ref "D184") (pin "2") (pinfunction "DO_2") (pintype "bidirectional"))
      (node (ref "D185") (pin "4") (pinfunction "DI_4") (pintype "bidirectional"))
    )
    (net (code "243") (name "Net-(D185-DO)") (class "Default")
      (node (ref "D185") (pin "2") (pinfunction "DO_2") (pintype "bidirectional"))
      (node (ref "D186") (pin "4") (pinfunction "DI_4") (pintype "bidirectional"))
    )
    (net (code "244") (name "Net-(D186-DO)") (class "Default")
      (node (ref "D186") (pin "2") (pinfunction "DO_2") (pintype "bidirectional"))
      (node (ref "D187") (pin "4") (pinfunction "DI_4") (pintype "bidirectional"))
    )
    (net (code "245") (name "Net-(D187-DO)") (class "Default")
      (node (ref "D187") (pin "2") (pinfunction "DO_2") (pintype "bidirectional"))
      (node (ref "D188") (pin "4") (pinfunction "DI_4") (pintype "bidirectional"))
    )
    (net (code "246") (name "Net-(D188-DO)") (class "Default")
      (node (ref "D188") (pin "2") (pinfunction "DO_2") (pintype "bidirectional"))
      (node (ref "D189") (pin "4") (pinfunction "DI_4") (pintype "bidirectional"))
    )
    (net (code "247") (name "Net-(D189-DO)") (class "Default")
      (node (ref "D189") (pin "2") (pinfunction "DO_2") (pintype "bidirectional"))
      (node (ref "D190") (pin "4") (pinfunction "DI_4") (pintype "bidirectional"))
    )
    (net (code "248") (name "Net-(D190-DO)") (class "Default")
      (node (ref "D190") (pin "2") (pinfunction "DO_2") (pintype "bidirectional"))
      (node (ref "D191") (pin "4") (pinfunction "DI_4") (pintype "bidirectional"))
    )
    (net (code "249") (name "Net-(D191-DO)") (class "Default")
      (node (ref "D191") (pin "2") (pinfunction "DO_2") (pintype "bidirectional"))
      (node (ref "D192") (pin "4") (pinfunction "DI_4") (pintype "bidirectional"))
    )
    (net (code "250") (name "Net-(D192-DO)") (class "Default")
      (node (ref "D192") (pin "2") (pinfunction "DO_2") (pintype "bidirectional"))
      (node (ref "D193") (pin "4") (pinfunction "DI_4") (pintype "bidirectional"))
    )
    (net (code "251") (name "Net-(D193-DO)") (class "Default")
      (node (ref "D193") (pin "2") (pinfunction "DO_2") (pintype "bidirectional"))
      (node (ref "D194") (pin "4") (pinfunction "DI_4") (pintype "bidirectional"))
    )
    (net (code "252") (name "Net-(D194-DO)") (class "Default")
      (node (ref "D194") (pin "2") (pinfunction "DO_2") (pintype "bidirectional"))
      (node (ref "D195") (pin "4") (pinfunction "DI_4") (pintype "bidirectional"))
    )
    (net (code "253") (name "Net-(D195-DO)") (class "Default")
      (node (ref "D195") (pin "2") (pinfunction "DO_2") (pintype "bidirectional"))
      (node (ref "D196") (pin "4") (pinfunction "DI_4") (pintype "bidirectional"))
    )
    (net (code "254") (name "Net-(D196-DO)") (class "Default")
      (node (ref "D196") (pin "2") (pinfunction "DO_2") (pintype "bidirectional"))
      (node (ref "D197") (pin "4") (pinfunction "DI_4") (pintype "bidirectional"))
    )
    (net (code "255") (name "Net-(D197-DO)") (class "Default")
      (node (ref "D197") (pin "2") (pinfunction "DO_2") (pintype "bidirectional"))
      (node (ref "D198") (pin "4") (pinfunction "DI_4") (pintype "bidirectional"))
    )
    (net (code "256") (name "Net-(D198-DO)") (class "Default")
      (node (ref "D198") (pin "2") (pinfunction "DO_2") (pintype "bidirectional"))
      (node (ref "D199") (pin "4") (pinfunction "DI_4") (pintype "bidirectional"))
    )
    (net (code "257") (name "Net-(D199-DO)") (class "Default")
      (node (ref "D199") (pin "2") (pinfunction "DO_2") (pintype "bidirectional"))
      (node (ref "D200") (pin "4") (pinfunction "DI_4") (pintype "bidirectional"))
    )
    (net (code "258") (name "Net-(D200-DO)") (class "Default")
      (node (ref "D200") (pin "2") (pinfunction "DO_2") (pintype "bidirectional"))
      (node (ref "D201") (pin "4") (pinfunction "DI_4") (pintype "bidirectional"))
    )
    (net (code "259") (name "Net-(D201-DO)") (class "Default")
      (node (ref "D201") (pin "2") (pinfunction "DO_2") (pintype "bidirectional"))
      (node (ref "D202") (pin "4") (pinfunction "DI_4") (pintype "bidirectional"))
    )
    (net (code "260") (name "Net-(D202-DO)") (class "Default")
      (node (ref "D202") (pin "2") (pinfunction "DO_2") (pintype "bidirectional"))
      (node (ref "D203") (pin "4") (pinfunction "DI_4") (pintype "bidirectional"))
    )
    (net (code "261") (name "Net-(D203-DO)") (class "Default")
      (node (ref "D203") (pin "2") (pinfunction "DO_2") (pintype "bidirectional"))
      (node (ref "D204") (pin "4") (pinfunction "DI_4") (pintype "bidirectional"))
    )
    (net (code "262") (name "Net-(D204-DO)") (class "Default")
      (node (ref "D204") (pin "2") (pinfunction "DO_2") (pintype "bidirectional"))
      (node (ref "D205") (pin "4") (pinfunction "DI_4") (pintype "bidirectional"))
    )
    (net (code "263") (name "Net-(D205-DO)") (class "Default")
      (node (ref "D205") (pin "2") (pinfunction "DO_2") (pintype "bidirectional"))
      (node (ref "D206") (pin "4") (pinfunction "DI_4") (pintype "bidirectional"))
    )
    (net (code "264") (name "Net-(D206-DO)") (class "Default")
      (node (ref "D206") (pin "2") (pinfunction "DO_2") (pintype "bidirectional"))
      (node (ref "D207") (pin "4") (pinfunction "DI_4") (pintype "bidirectional"))
    )
    (net (code "265") (name "Net-(D207-DO)") (class "Default")
      (node (ref "D207") (pin "2") (pinfunction "DO_2") (pintype "bidirectional"))
      (node (ref "D208") (pin "4") (pinfunction "DI_4") (pintype "bidirectional"))
    )
    (net (code "266") (name "Net-(D208-DO)") (class "Default")
      (node (ref "D208") (pin "2") (pinfunction "DO_2") (pintype "bidirectional"))
      (node (ref "D209") (pin "4") (pinfunction "DI_4") (pintype "bidirectional"))
    )
    (net (code "267") (name "Net-(D209-DO)") (class "Default")
      (node (ref "D209") (pin "2") (pinfunction "DO_2") (pintype "bidirectional"))
      (node (ref "D210") (pin "4") (pinfunction "DI_4") (pintype "bidirectional"))
    )
    (net (code "268") (name "Net-(D210-DO)") (class "Default")
      (node (ref "D210") (pin "2") (pinfunction "DO_2") (pintype "bidirectional"))
      (node (ref "D211") (pin "4") (pinfunction "DI_4") (pintype "bidirectional"))
    )
    (net (code "269") (name "Net-(D211-DO)") (class "Default")
      (node (ref "D211") (pin "2") (pinfunction "DO_2") (pintype "bidirectional"))
      (node (ref "D212") (pin "4") (pinfunction "DI_4") (pintype "bidirectional"))
    )
    (net (code "270") (name "Net-(D212-DO)") (class "Default")
      (node (ref "D212") (pin "2") (pinfunction "DO_2") (pintype "bidirectional"))
      (node (ref "D213") (pin "4") (pinfunction "DI_4") (pintype "bidirectional"))
    )
    (net (code "271") (name "Net-(D213-DO)") (class "Default")
      (node (ref "D213") (pin "2") (pinfunction "DO_2") (pintype "bidirectional"))
      (node (ref "D214") (pin "4") (pinfunction "DI_4") (pintype "bidirectional"))
    )
    (net (code "272") (name "Net-(D214-DO)") (class "Default")
      (node (ref "D214") (pin "2") (pinfunction "DO_2") (pintype "bidirectional"))
      (node (ref "D215") (pin "4") (pinfunction "DI_4") (pintype "bidirectional"))
    )
    (net (code "273") (name "Net-(D215-DO)") (class "Default")
      (node (ref "D215") (pin "2") (pinfunction "DO_2") (pintype "bidirectional"))
      (node (ref "D216") (pin "4") (pinfunction "DI_4") (pintype "bidirectional"))
    )
    (net (code "274") (name "Net-(D216-DO)") (class "Default")
      (node (ref "D216") (pin "2") (pinfunction "DO_2") (pintype "bidirectional"))
      (node (ref "D217") (pin "4") (pinfunction "DI_4") (pintype "bidirectional"))
    )
    (net (code "275") (name "Net-(D217-DO)") (class "Default")
      (node (ref "D217") (pin "2") (pinfunction "DO_2") (pintype "bidirectional"))
      (node (ref "D218") (pin "4") (pinfunction "DI_4") (pintype "bidirectional"))
    )
    (net (code "276") (name "Net-(D218-DO)") (class "Default")
      (node (ref "D218") (pin "2") (pinfunction "DO_2") (pintype "bidirectional"))
      (node (ref "D219") (pin "4") (pinfunction "DI_4") (pintype "bidirectional"))
    )
    (net (code "277") (name "Net-(D219-DO)") (class "Default")
      (node (ref "D219") (pin "2") (pinfunction "DO_2") (pintype "bidirectional"))
      (node (ref "D220") (pin "4") (pinfunction "DI_4") (pintype "bidirectional"))
    )
    (net (code "278") (name "Net-(D220-DO)") (class "Default")
      (node (ref "D220") (pin "2") (pinfunction "DO_2") (pintype "bidirectional"))
      (node (ref "D221") (pin "4") (pinfunction "DI_4") (pintype "bidirectional"))
    )
    (net (code "279") (name "Net-(D221-DO)") (class "Default")
      (node (ref "D221") (pin "2") (pinfunction "DO_2") (pintype "bidirectional"))
      (node (ref "D222") (pin "4") (pinfunction "DI_4") (pintype "bidirectional"))
    )
    (net (code "280") (name "Net-(D222-DO)") (class "Default")
      (node (ref "D222") (pin "2") (pinfunction "DO_2") (pintype "bidirectional"))
      (node (ref "D223") (pin "4") (pinfunction "DI_4") (pintype "bidirectional"))
    )
    (net (code "281") (name "Net-(D223-DO)") (class "Default")
      (node (ref "D223") (pin "2") (pinfunction "DO_2") (pintype "bidirectional"))
      (node (ref "D224") (pin "4") (pinfunction "DI_4") (pintype "bidirectional"))
    )
    (net (code "282") (name "Net-(D224-DO)") (class "Default")
      (node (ref "D224") (pin "2") (pinfunction "DO_2") (pintype "bidirectional"))
      (node (ref "D225") (pin "4") (pinfunction "DI_4") (pintype "bidirectional"))
    )
    (net (code "283") (name "Net-(S7-P)") (class "Default")
      (node (ref "D226") (pin "C") (pinfunction "C_C") (pintype "passive"))
      (node (ref "S7") (pin "2") (pinfunction "P_2") (pintype "passive"))
    )
    (net (code "284") (name "Net-(S7-S)") (class "Default")
      (node (ref "C228") (pin "1") (pinfunction "1_1") (pintype "passive"))
      (node (ref "S7") (pin "3") (pinfunction "S_3") (pintype "passive"))
      (node (ref "U6") (pin "IN") (pinfunction "IN_IN") (pintype "input"))
    )
    (net (code "285") (name "Net-(U1-QA)") (class "Default")
      (node (ref "R8") (pin "1") (pinfunction "1_1") (pintype "passive"))
      (node (ref "U1") (pin "15") (pinfunction "QA_15") (pintype "tri_state"))
    )
    (net (code "286") (name "Net-(U1-QB)") (class "Default")
      (node (ref "R1") (pin "1") (pinfunction "1_1") (pintype "passive"))
      (node (ref "U1") (pin "1") (pinfunction "QB_1") (pintype "tri_state"))
    )
    (net (code "287") (name "Net-(U1-QC)") (class "Default")
      (node (ref "R2") (pin "1") (pinfunction "1_1") (pintype "passive"))
      (node (ref "U1") (pin "2") (pinfunction "QC_2") (pintype "tri_state"))
    )
    (net (code "288") (name "Net-(U1-QD)") (class "Default")
      (node (ref "R3") (pin "1") (pinfunction "1_1") (pintype "passive"))
      (node (ref "U1") (pin "3") (pinfunction "QD_3") (pintype "tri_state"))
    )
    (net (code "289") (name "Net-(U1-QE)") (class "Default")
      (node (ref "R4") (pin "1") (pinfunction "1_1") (pintype "passive"))
      (node (ref "U1") (pin "4") (pinfunction "QE_4") (pintype "tri_state"))
    )
    (net (code "290") (name "Net-(U1-QF)") (class "Default")
      (node (ref "R5") (pin "1") (pinfunction "1_1") (pintype "passive"))
      (node (ref "U1") (pin "5") (pinfunction "QF_5") (pintype "tri_state"))
    )
    (net (code "291") (name "Net-(U1-QG)") (class "Default")
      (node (ref "R6") (pin "1") (pinfunction "1_1") (pintype "passive"))
      (node (ref "U1") (pin "6") (pinfunction "QG_6") (pintype "tri_state"))
    )
    (net (code "292") (name "Net-(U1-QH)") (class "Default")
      (node (ref "R7") (pin "1") (pinfunction "1_1") (pintype "passive"))
      (node (ref "U1") (pin "7") (pinfunction "QH_7") (pintype "tri_state"))
    )
    (net (code "293") (name "Net-(U1-QH*)") (class "Default")
      (node (ref "U1") (pin "9") (pinfunction "QH*_9") (pintype "tri_state"))
      (node (ref "U2") (pin "14") (pinfunction "SER_14") (pintype "input"))
    )
    (net (code "294") (name "Net-(U2-QA)") (class "Default")
      (node (ref "R9") (pin "1") (pinfunction "1_1") (pintype "passive"))
      (node (ref "U2") (pin "15") (pinfunction "QA_15") (pintype "tri_state"))
    )
    (net (code "295") (name "Net-(U2-QB)") (class "Default")
      (node (ref "R10") (pin "1") (pinfunction "1_1") (pintype "passive"))
      (node (ref "U2") (pin "1") (pinfunction "QB_1") (pintype "tri_state"))
    )
    (net (code "296") (name "Net-(U2-QC)") (class "Default")
      (node (ref "R11") (pin "1") (pinfunction "1_1") (pintype "passive"))
      (node (ref "U2") (pin "2") (pinfunction "QC_2") (pintype "tri_state"))
    )
    (net (code "297") (name "Net-(U2-QD)") (class "Default")
      (node (ref "R12") (pin "1") (pinfunction "1_1") (pintype "passive"))
      (node (ref "U2") (pin "3") (pinfunction "QD_3") (pintype "tri_state"))
    )
    (net (code "298") (name "Net-(U2-QE)") (class "Default")
      (node (ref "R13") (pin "1") (pinfunction "1_1") (pintype "passive"))
      (node (ref "U2") (pin "4") (pinfunction "QE_4") (pintype "tri_state"))
    )
    (net (code "299") (name "Net-(U2-QF)") (class "Default")
      (node (ref "R14") (pin "1") (pinfunction "1_1") (pintype "passive"))
      (node (ref "U2") (pin "5") (pinfunction "QF_5") (pintype "tri_state"))
    )
    (net (code "300") (name "Net-(U2-QG)") (class "Default")
      (node (ref "R15") (pin "1") (pinfunction "1_1") (pintype "passive"))
      (node (ref "U2") (pin "6") (pinfunction "QG_6") (pintype "tri_state"))
    )
    (net (code "301") (name "Net-(U2-QH)") (class "Default")
      (node (ref "R16") (pin "1") (pinfunction "1_1") (pintype "passive"))
      (node (ref "U2") (pin "7") (pinfunction "QH_7") (pintype "tri_state"))
    )
    (net (code "302") (name "Net-(U2-QH*)") (class "Default")
      (node (ref "U2") (pin "9") (pinfunction "QH*_9") (pintype "tri_state"))
      (node (ref "U3") (pin "14") (pinfunction "SER_14") (pintype "input"))
    )
    (net (code "303") (name "Net-(U3-QA)") (class "Default")
      (node (ref "R17") (pin "1") (pinfunction "1_1") (pintype "passive"))
      (node (ref "U3") (pin "15") (pinfunction "QA_15") (pintype "tri_state"))
    )
    (net (code "304") (name "Net-(U3-QB)") (class "Default")
      (node (ref "R18") (pin "1") (pinfunction "1_1") (pintype "passive"))
      (node (ref "U3") (pin "1") (pinfunction "QB_1") (pintype "tri_state"))
    )
    (net (code "305") (name "Net-(U3-QC)") (class "Default")
      (node (ref "R19") (pin "1") (pinfunction "1_1") (pintype "passive"))
      (node (ref "U3") (pin "2") (pinfunction "QC_2") (pintype "tri_state"))
    )
    (net (code "306") (name "Net-(U3-QD)") (class "Default")
      (node (ref "R20") (pin "1") (pinfunction "1_1") (pintype "passive"))
      (node (ref "U3") (pin "3") (pinfunction "QD_3") (pintype "tri_state"))
    )
    (net (code "307") (name "Net-(U3-QE)") (class "Default")
      (node (ref "R21") (pin "1") (pinfunction "1_1") (pintype "passive"))
      (node (ref "U3") (pin "4") (pinfunction "QE_4") (pintype "tri_state"))
    )
    (net (code "308") (name "Net-(U3-QF)") (class "Default")
      (node (ref "R22") (pin "1") (pinfunction "1_1") (pintype "passive"))
      (node (ref "U3") (pin "5") (pinfunction "QF_5") (pintype "tri_state"))
    )
    (net (code "309") (name "Net-(U3-QG)") (class "Default")
      (node (ref "R23") (pin "1") (pinfunction "1_1") (pintype "passive"))
      (node (ref "U3") (pin "6") (pinfunction "QG_6") (pintype "tri_state"))
    )
    (net (code "310") (name "Net-(U3-QH)") (class "Default")
      (node (ref "R24") (pin "1") (pinfunction "1_1") (pintype "passive"))
      (node (ref "U3") (pin "7") (pinfunction "QH_7") (pintype "tri_state"))
    )
    (net (code "311") (name "Net-(U3-QH*)") (class "Default")
      (node (ref "U3") (pin "9") (pinfunction "QH*_9") (pintype "tri_state"))
      (node (ref "U4") (pin "14") (pinfunction "SER_14") (pintype "input"))
    )
    (net (code "312") (name "Net-(U4-QA)") (class "Default")
      (node (ref "R25") (pin "1") (pinfunction "1_1") (pintype "passive"))
      (node (ref "U4") (pin "15") (pinfunction "QA_15") (pintype "tri_state"))
    )
    (net (code "313") (name "Net-(U4-QB)") (class "Default")
      (node (ref "R26") (pin "1") (pinfunction "1_1") (pintype "passive"))
      (node (ref "U4") (pin "1") (pinfunction "QB_1") (pintype "tri_state"))
    )
    (net (code "314") (name "Net-(U4-QC)") (class "Default")
      (node (ref "R27") (pin "1") (pinfunction "1_1") (pintype "passive"))
      (node (ref "U4") (pin "2") (pinfunction "QC_2") (pintype "tri_state"))
    )
    (net (code "315") (name "Net-(U4-QD)") (class "Default")
      (node (ref "R28") (pin "1") (pinfunction "1_1") (pintype "passive"))
      (node (ref "U4") (pin "3") (pinfunction "QD_3") (pintype "tri_state"))
    )
    (net (code "316") (name "Net-(U4-QE)") (class "Default")
      (node (ref "R29") (pin "1") (pinfunction "1_1") (pintype "passive"))
      (node (ref "U4") (pin "4") (pinfunction "QE_4") (pintype "tri_state"))
    )
    (net (code "317") (name "Net-(U4-QF)") (class "Default")
      (node (ref "R30") (pin "1") (pinfunction "1_1") (pintype "passive"))
      (node (ref "U4") (pin "5") (pinfunction "QF_5") (pintype "tri_state"))
    )
    (net (code "318") (name "Net-(U4-QG)") (class "Default")
      (node (ref "R31") (pin "1") (pinfunction "1_1") (pintype "passive"))
      (node (ref "U4") (pin "6") (pinfunction "QG_6") (pintype "tri_state"))
    )
    (net (code "319") (name "Net-(U4-QH)") (class "Default")
      (node (ref "R32") (pin "1") (pinfunction "1_1") (pintype "passive"))
      (node (ref "U4") (pin "7") (pinfunction "QH_7") (pintype "tri_state"))
    )
    (net (code "320") (name "Net-(U4-QH*)") (class "Default")
      (node (ref "U4") (pin "9") (pinfunction "QH*_9") (pintype "tri_state"))
      (node (ref "U5") (pin "14") (pinfunction "SER_14") (pintype "input"))
    )
    (net (code "321") (name "Net-(U5-QA)") (class "Default")
      (node (ref "R33") (pin "1") (pinfunction "1_1") (pintype "passive"))
      (node (ref "U5") (pin "15") (pinfunction "QA_15") (pintype "tri_state"))
    )
    (net (code "322") (name "Net-(U5-QB)") (class "Default")
      (node (ref "R34") (pin "1") (pinfunction "1_1") (pintype "passive"))
      (node (ref "U5") (pin "1") (pinfunction "QB_1") (pintype "tri_state"))
    )
    (net (code "323") (name "Net-(U5-QC)") (class "Default")
      (node (ref "R35") (pin "1") (pinfunction "1_1") (pintype "passive"))
      (node (ref "U5") (pin "2") (pinfunction "QC_2") (pintype "tri_state"))
    )
    (net (code "324") (name "Net-(U5-QD)") (class "Default")
      (node (ref "R36") (pin "1") (pinfunction "1_1") (pintype "passive"))
      (node (ref "U5") (pin "3") (pinfunction "QD_3") (pintype "tri_state"))
    )
    (net (code "325") (name "Net-(U5-QE)") (class "Default")
      (node (ref "R37") (pin "1") (pinfunction "1_1") (pintype "passive"))
      (node (ref "U5") (pin "4") (pinfunction "QE_4") (pintype "tri_state"))
    )
    (net (code "326") (name "Net-(U5-QF)") (class "Default")
      (node (ref "R38") (pin "1") (pinfunction "1_1") (pintype "passive"))
      (node (ref "U5") (pin "5") (pinfunction "QF_5") (pintype "tri_state"))
    )
    (net (code "327") (name "Net-(U5-QG)") (class "Default")
      (node (ref "R39") (pin "1") (pinfunction "1_1") (pintype "passive"))
      (node (ref "U5") (pin "6") (pinfunction "QG_6") (pintype "tri_state"))
    )
    (net (code "328") (name "Net-(U5-QH)") (class "Default")
      (node (ref "R40") (pin "1") (pinfunction "1_1") (pintype "passive"))
      (node (ref "U5") (pin "7") (pinfunction "QH_7") (pintype "tri_state"))
    )
    (net (code "329") (name "Net-(VR2-CCW)") (class "Default")
      (node (ref "B3") (pin "VOL+") (pinfunction "VCC_VOL+") (pintype "bidirectional"))
      (node (ref "VR2") (pin "1") (pinfunction "CCW_1") (pintype "passive"))
    )
    (net (code "330") (name "Net-(VR2-CW)") (class "Default")
      (node (ref "B3") (pin "VOL-") (pinfunction "GND_VOL-") (pintype "bidirectional"))
      (node (ref "VR2") (pin "3") (pinfunction "CW_3") (pintype "passive"))
    )
    (net (code "331") (name "Net-(VR2-WIPER)") (class "Default")
      (node (ref "B3") (pin "VOL") (pinfunction "VOL_VOL") (pintype "bidirectional"))
      (node (ref "VR2") (pin "2") (pinfunction "WIPER_2") (pintype "passive"))
    )
    (net (code "332") (name "P_RCK") (class "Default")
      (node (ref "R53") (pin "1") (pinfunction "1_1") (pintype "passive"))
      (node (ref "T3") (pin "3") (pinfunction "D_3") (pintype "passive"))
      (node (ref "U1") (pin "12") (pinfunction "RCK_12") (pintype "input"))
      (node (ref "U2") (pin "12") (pinfunction "RCK_12") (pintype "input"))
      (node (ref "U3") (pin "12") (pinfunction "RCK_12") (pintype "input"))
      (node (ref "U4") (pin "12") (pinfunction "RCK_12") (pintype "input"))
      (node (ref "U5") (pin "12") (pinfunction "RCK_12") (pintype "input"))
    )
    (net (code "333") (name "P_SCK") (class "Default")
      (node (ref "R49") (pin "1") (pinfunction "1_1") (pintype "passive"))
      (node (ref "T1") (pin "3") (pinfunction "D_3") (pintype "passive"))
      (node (ref "U1") (pin "11") (pinfunction "SCK_11") (pintype "input"))
      (node (ref "U2") (pin "11") (pinfunction "SCK_11") (pintype "input"))
      (node (ref "U3") (pin "11") (pinfunction "SCK_11") (pintype "input"))
      (node (ref "U4") (pin "11") (pinfunction "SCK_11") (pintype "input"))
      (node (ref "U5") (pin "11") (pinfunction "SCK_11") (pintype "input"))
    )
    (net (code "334") (name "P_SER") (class "Default")
      (node (ref "R51") (pin "1") (pinfunction "1_1") (pintype "passive"))
      (node (ref "T2") (pin "3") (pinfunction "D_3") (pintype "passive"))
      (node (ref "U1") (pin "14") (pinfunction "SER_14") (pintype "input"))
    )
    (net (code "335") (name "UNION") (class "Default")
      (node (ref "BT1") (pin "GND@1") (pinfunction "-_GND@1") (pintype "power_in"))
      (node (ref "BT2") (pin "PWR@1") (pinfunction "+_PWR@1") (pintype "power_in"))
    )
    (net (code "336") (name "V_BATT") (class "Default")
      (node (ref "BT1") (pin "PWR@1") (pinfunction "+_PWR@1") (pintype "power_in"))
      (node (ref "D226") (pin "A") (pinfunction "A_A") (pintype "passive"))
    )
    (net (code "337") (name "unconnected-(B2-0-Pad32)") (class "Default")
      (node (ref "B2") (pin "32") (pinfunction "0_32") (pintype "bidirectional"))
    )
    (net (code "338") (name "unconnected-(B2-2-Pad31)") (class "Default")
      (node (ref "B2") (pin "31") (pinfunction "2_31") (pintype "bidirectional"))
    )
    (net (code "339") (name "unconnected-(B2-4-Pad33)") (class "Default")
      (node (ref "B2") (pin "33") (pinfunction "4_33") (pintype "bidirectional"))
    )
    (net (code "340") (name "unconnected-(B2-5-Pad29)") (class "Default")
      (node (ref "B2") (pin "29") (pinfunction "5_29") (pintype "bidirectional"))
    )
    (net (code "341") (name "unconnected-(B2-13-Pad7)") (class "Default")
      (node (ref "B2") (pin "7") (pinfunction "13_7") (pintype "bidirectional"))
    )
    (net (code "342") (name "unconnected-(B2-15-Pad30)") (class "Default")
      (node (ref "B2") (pin "30") (pinfunction "15_30") (pintype "bidirectional"))
    )
    (net (code "343") (name "unconnected-(B2-16-Pad35)") (class "Default")
      (node (ref "B2") (pin "35") (pinfunction "16_35") (pintype "bidirectional"))
    )
    (net (code "344") (name "unconnected-(B2-17-Pad34)") (class "Default")
      (node (ref "B2") (pin "34") (pinfunction "17_34") (pintype "bidirectional"))
    )
    (net (code "345") (name "unconnected-(B2-18-Pad28)") (class "Default")
      (node (ref "B2") (pin "28") (pinfunction "18_28") (pintype "bidirectional"))
    )
    (net (code "346") (name "unconnected-(B2-19-Pad26)") (class "Default")
      (node (ref "B2") (pin "26") (pinfunction "19_26") (pintype "bidirectional"))
    )
    (net (code "347") (name "unconnected-(B2-21-Pad22)") (class "Default")
      (node (ref "B2") (pin "22") (pinfunction "21_22") (pintype "bidirectional"))
    )
    (net (code "348") (name "unconnected-(B2-22-Pad25)") (class "Default")
      (node (ref "B2") (pin "25") (pinfunction "22_25") (pintype "bidirectional"))
    )
    (net (code "349") (name "unconnected-(B2-23-Pad27)") (class "Default")
      (node (ref "B2") (pin "27") (pinfunction "23_27") (pintype "bidirectional"))
    )
    (net (code "350") (name "unconnected-(B2-33-Pad15)") (class "Default")
      (node (ref "B2") (pin "15") (pinfunction "33_15") (pintype "bidirectional"))
    )
    (net (code "351") (name "unconnected-(B2-38-Pad18)") (class "Default")
      (node (ref "B2") (pin "18") (pinfunction "38_18") (pintype "bidirectional"))
    )
    (net (code "352") (name "unconnected-(B2-RX-Pad24)") (class "Default")
      (node (ref "B2") (pin "24") (pinfunction "RX_24") (pintype "bidirectional"))
    )
    (net (code "353") (name "unconnected-(B2-TX-Pad23)") (class "Default")
      (node (ref "B2") (pin "23") (pinfunction "TX_23") (pintype "bidirectional"))
    )
    (net (code "354") (name "unconnected-(B2-VUSB-Pad2)") (class "Default")
      (node (ref "B2") (pin "2") (pinfunction "VUSB_2") (pintype "bidirectional"))
    )
    (net (code "355") (name "unconnected-(B2-VUSB-Pad39)") (class "Default")
      (node (ref "B2") (pin "39") (pinfunction "VUSB_39") (pintype "bidirectional"))
    )
    (net (code "356") (name "unconnected-(B2-~{RST}-Pad6)") (class "Default")
      (node (ref "B2") (pin "6") (pinfunction "~{RST}_6") (pintype "bidirectional"))
    )
    (net (code "357") (name "unconnected-(D225-DO-Pad2)") (class "Default")
      (node (ref "D225") (pin "2") (pinfunction "DO_2") (pintype "bidirectional"))
    )
    (net (code "358") (name "unconnected-(S7-O-Pad1)") (class "Default")
      (node (ref "S7") (pin "1") (pinfunction "O_1") (pintype "passive"))
    )
    (net (code "359") (name "unconnected-(U5-QH*-Pad9)") (class "Default")
      (node (ref "U5") (pin "9") (pinfunction "QH*_9") (pintype "tri_state"))
    )
  )
)
